# RUMBA32.net
KiCad netlist of a schematic drawn in Altium Designer
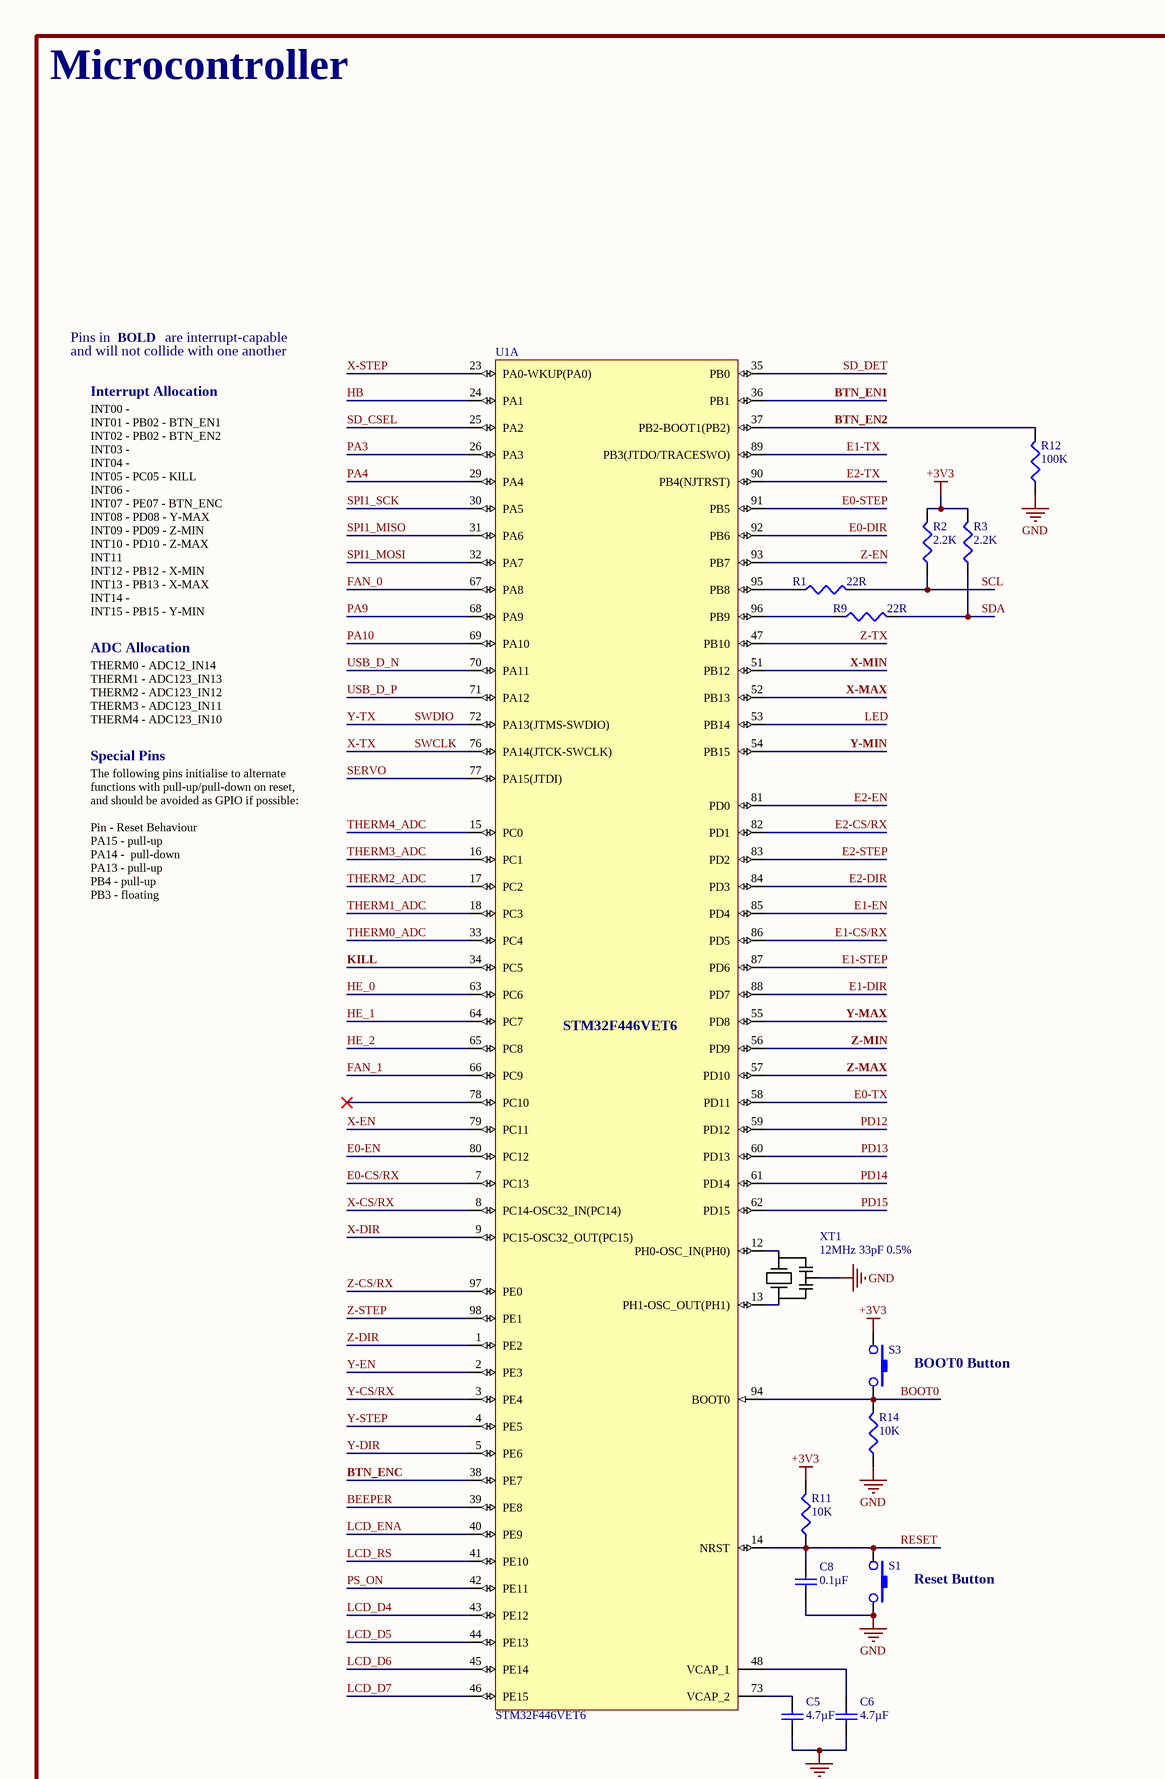
[diagram p0: RUMBA32.SchDoc, top left]
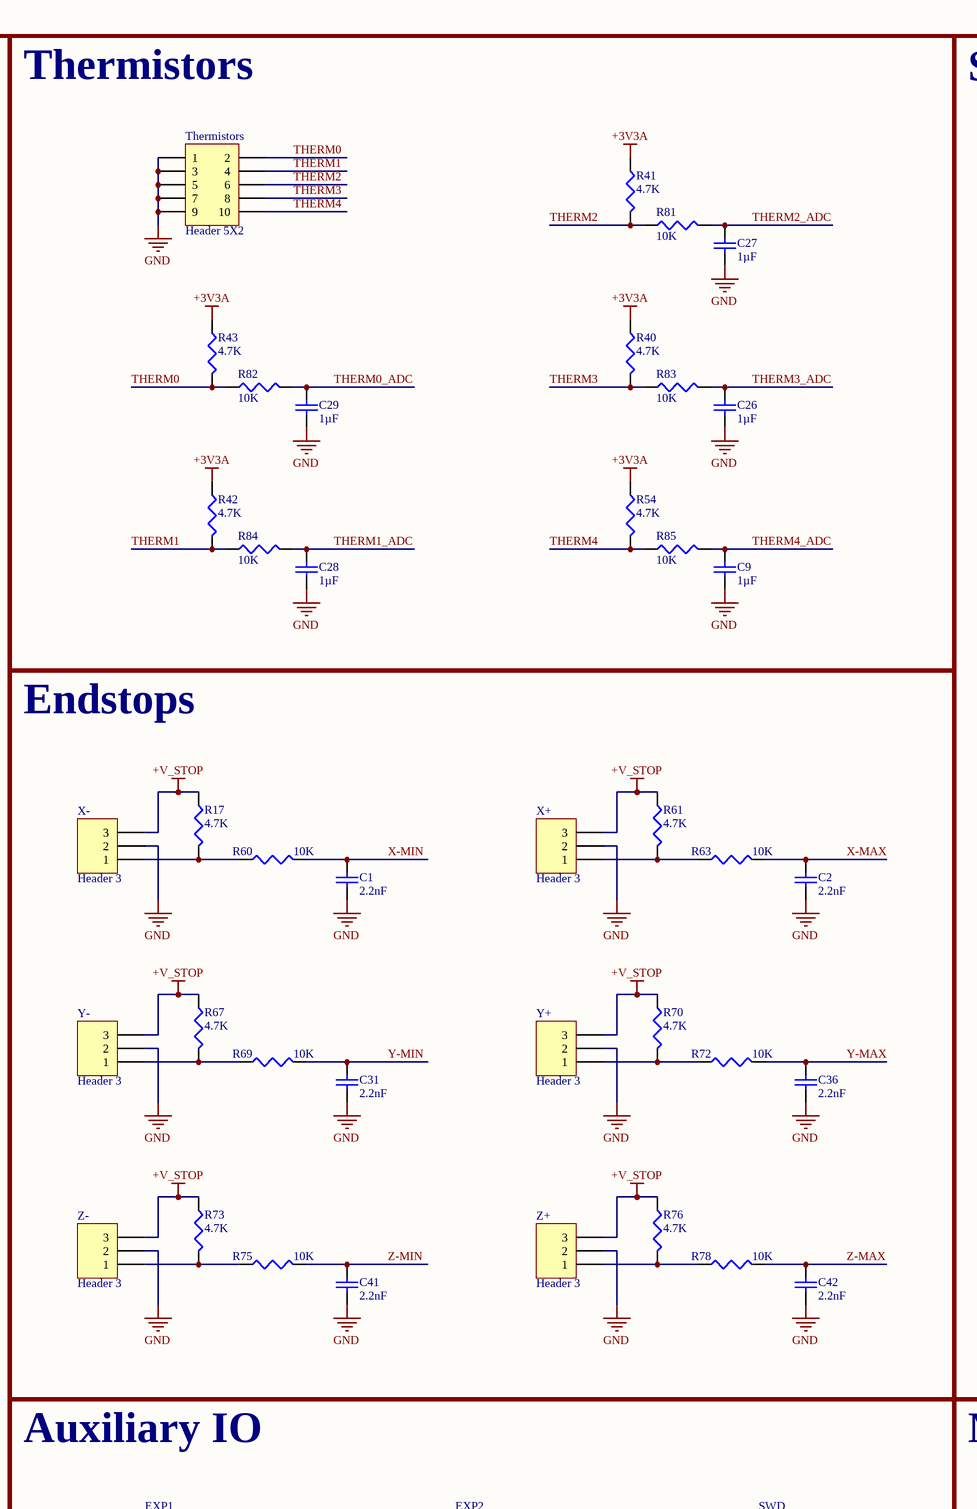
[diagram p1: RUMBA32.SchDoc, top middle]
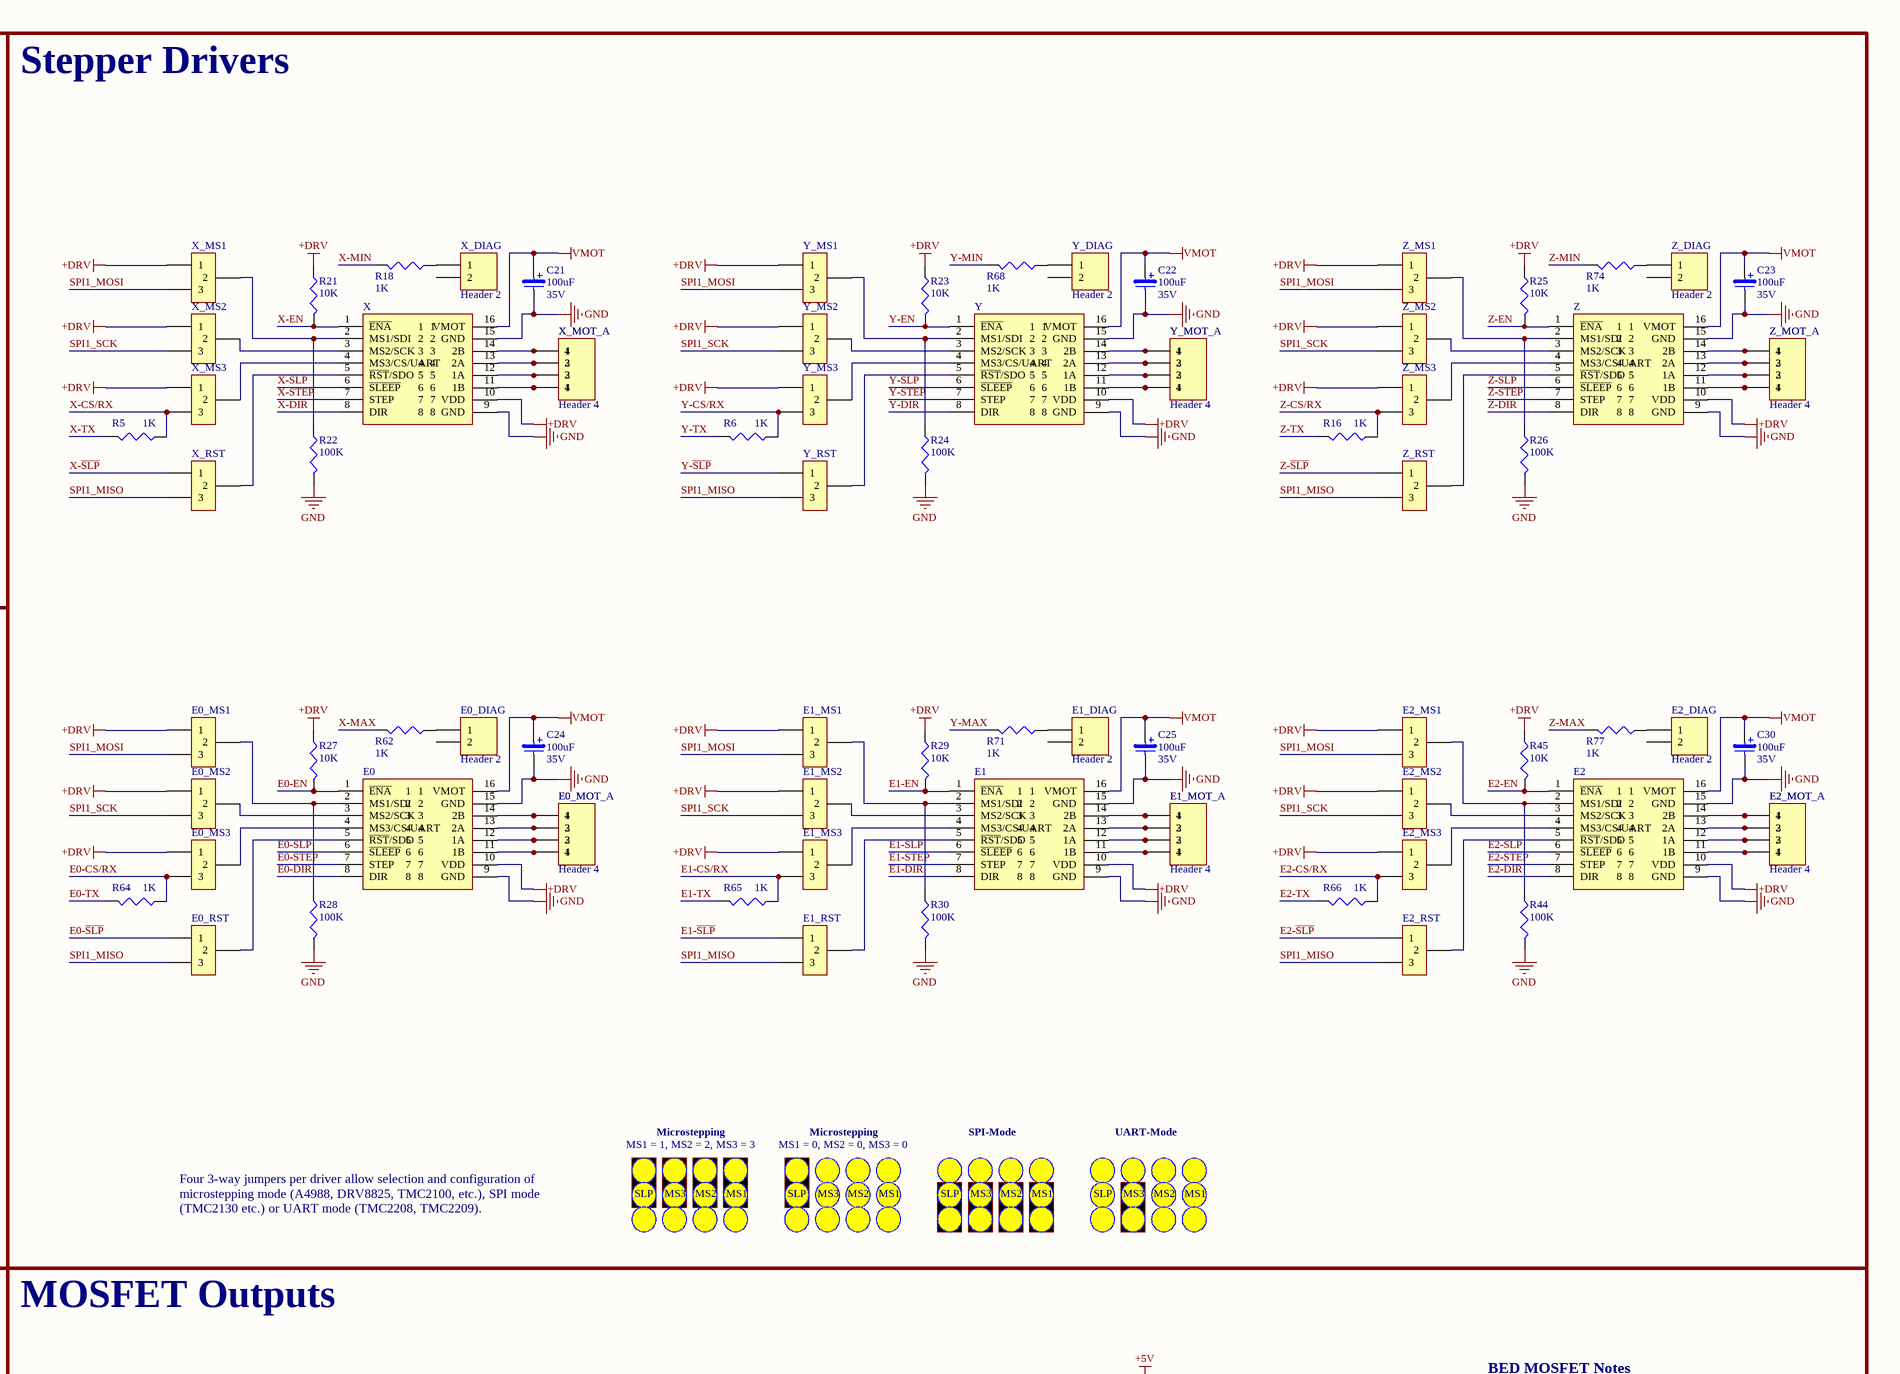
[diagram p2: RUMBA32.SchDoc, top right]
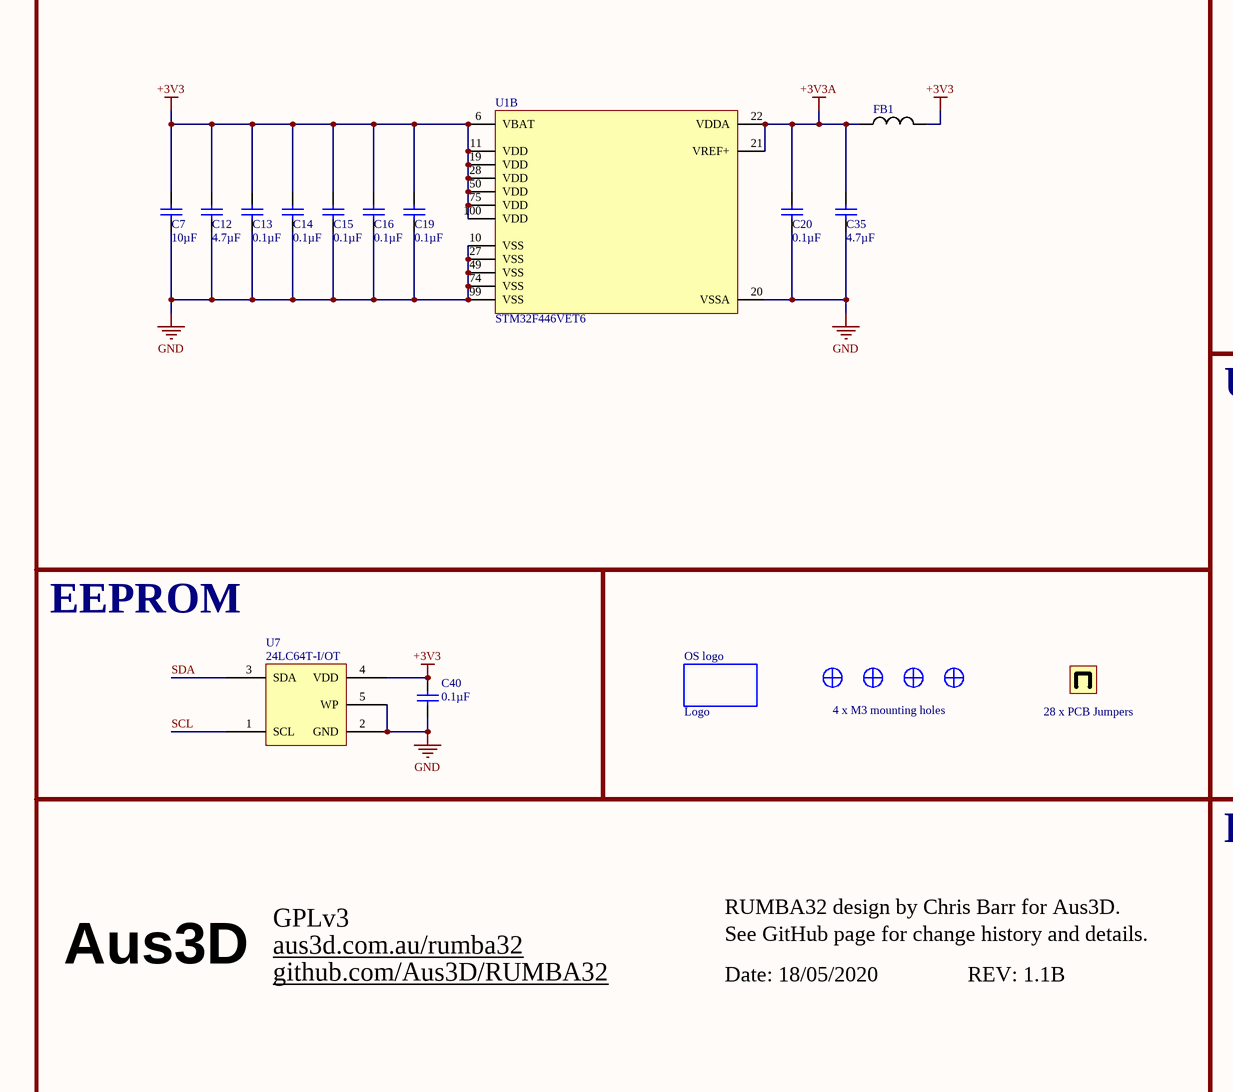
[diagram p3: RUMBA32.SchDoc, bottom left]
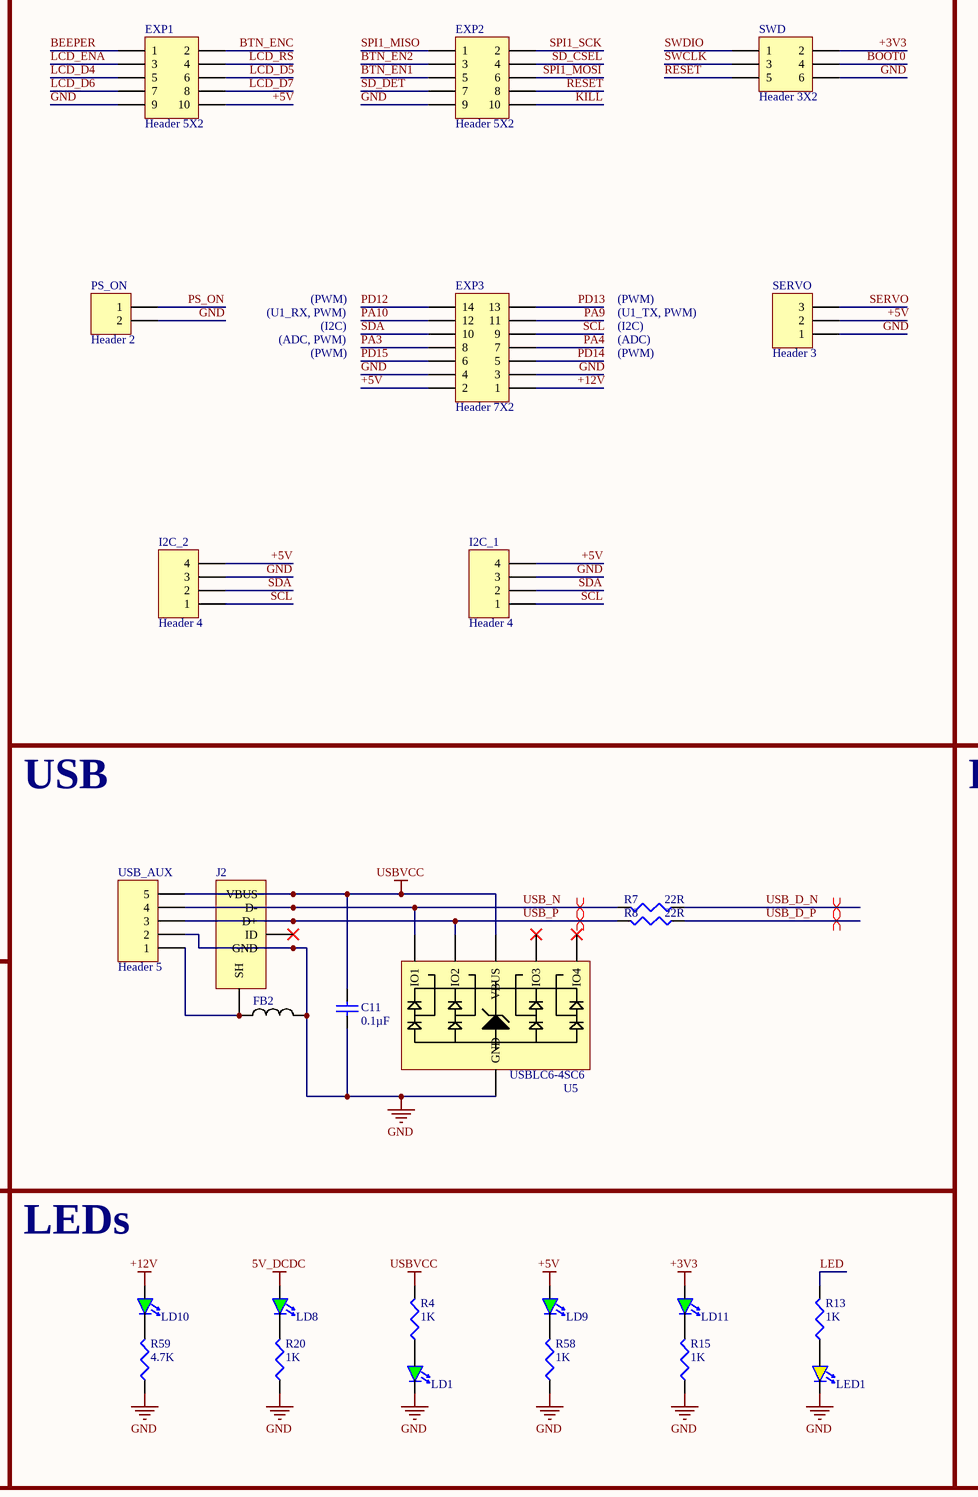
[diagram p4: RUMBA32.SchDoc, bottom middle]
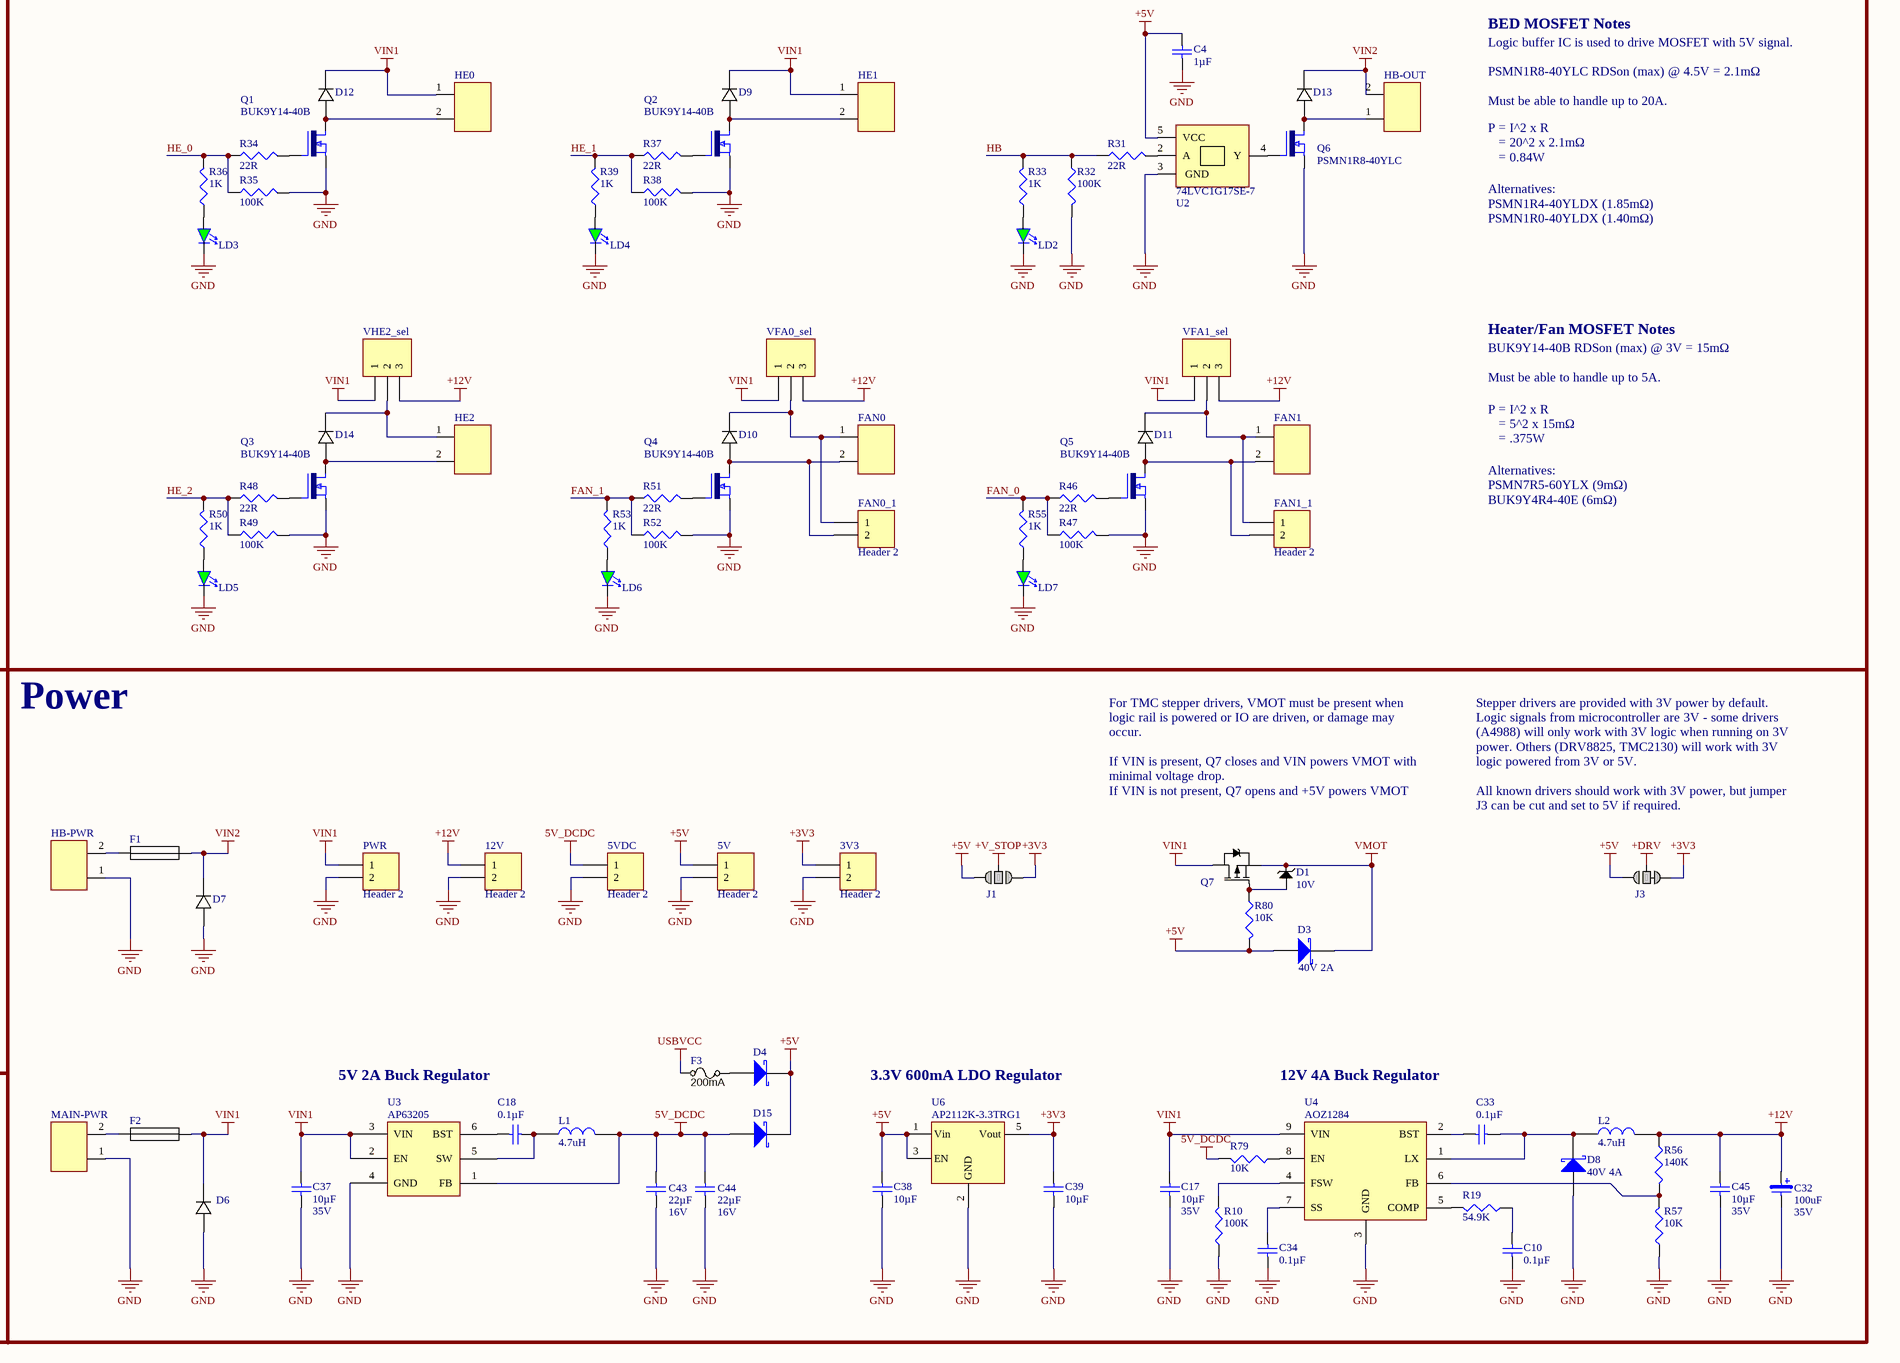
[diagram p5: RUMBA32.SchDoc, bottom right]

(export (version "E")
  (design (tool "Eeschema 10.0.6"))
  (components
    (comp (ref "3V3")
      (value "Header 2")
      (footprint "HDR1X2-HEADER")
      (description "Header, 2-Pin")
      (fields (field (name "PUBLISHER") "Altium Limited"))
      (libsource (lib "RUMBA_v2") (part "Header 2"))
    )
    (comp (ref "5V")
      (value "Header 2")
      (footprint "HDR1X2-HEADER")
      (description "Header, 2-Pin")
      (fields (field (name "PUBLISHER") "Altium Limited"))
      (libsource (lib "RUMBA_v2") (part "Header 2"))
    )
    (comp (ref "5VDC")
      (value "Header 2")
      (footprint "HDR1X2-HEADER")
      (description "Header, 2-Pin")
      (fields (field (name "PUBLISHER") "Altium Limited"))
      (libsource (lib "RUMBA_v2") (part "Header 2"))
    )
    (comp (ref "12V")
      (value "Header 2")
      (footprint "HDR1X2-HEADER")
      (description "Header, 2-Pin")
      (fields (field (name "PUBLISHER") "Altium Limited"))
      (libsource (lib "RUMBA_v2") (part "Header 2"))
    )
    (comp (ref "C1")
      (value "2.2nF")
      (footprint "CAPC1005X55N")
      (description "CAP CER 2.2NF 50V X7R 0402")
      (fields (field (name "VOLTAGE") "50V") (field (name "TOLERANCE") "±10%"))
      (libsource (lib "Ceramic Cap DBLIB") (part "Capacitor"))
    )
    (comp (ref "C2")
      (value "2.2nF")
      (footprint "CAPC1005X55N")
      (description "CAP CER 2.2NF 50V X7R 0402")
      (fields (field (name "VOLTAGE") "50V") (field (name "TOLERANCE") "±10%"))
      (libsource (lib "Ceramic Cap DBLIB") (part "Capacitor"))
    )
    (comp (ref "C4")
      (value "1µF")
      (footprint "CAP 1005-0402")
      (description "CAP CER 1UF 16V X5R 0402")
      (fields (field (name "TOLERANCE") "±10%") (field (name "VOLTAGE") "16V"))
      (libsource (lib "Ceramic Cap DBLIB") (part "Capacitor"))
    )
    (comp (ref "C5")
      (value "4.7µF")
      (footprint "CAP 1005-0402")
      (description "CAP CER 4.7UF 10V X5R 0402")
      (fields (field (name "TOLERANCE") "±20%") (field (name "VOLTAGE") "10V"))
      (libsource (lib "Ceramic Cap DBLIB") (part "Capacitor"))
    )
    (comp (ref "C6")
      (value "4.7µF")
      (footprint "CAP 1005-0402")
      (description "CAP CER 4.7UF 10V X5R 0402")
      (fields (field (name "TOLERANCE") "±20%") (field (name "VOLTAGE") "10V"))
      (libsource (lib "Ceramic Cap DBLIB") (part "Capacitor"))
    )
    (comp (ref "C7")
      (value "10µF")
      (footprint "CAPC1608X90N")
      (description "CAP CER 10UF 10V X5R 0603")
      (fields (field (name "VOLTAGE") "10V") (field (name "TOLERANCE") "±10%"))
      (libsource (lib "Ceramic Cap DBLIB") (part "Capacitor"))
    )
    (comp (ref "C8")
      (value "0.1µF")
      (footprint "CAP 1005-0402")
      (description "CAP CER 0.1UF 50V X7R 0402")
      (fields (field (name "VOLTAGE") "50V") (field (name "TOLERANCE") "±10%"))
      (libsource (lib "Ceramic Cap DBLIB") (part "Capacitor"))
    )
    (comp (ref "C9")
      (value "1µF")
      (footprint "CAPC1005X55N")
      (description "CAP CER 1UF 16V X5R 0402")
      (fields (field (name "TOLERANCE") "±10%") (field (name "VOLTAGE") "16V"))
      (libsource (lib "Ceramic Cap DBLIB") (part "Capacitor"))
    )
    (comp (ref "C10")
      (value "0.1µF")
      (footprint "CAP 1005-0402")
      (description "CAP CER 0.1UF 50V X7R 0402")
      (fields (field (name "VOLTAGE") "50V") (field (name "TOLERANCE") "±10%"))
      (libsource (lib "Ceramic Cap DBLIB") (part "Capacitor"))
    )
    (comp (ref "C11")
      (value "0.1µF")
      (footprint "CAP 1005-0402")
      (description "CAP CER 0.1UF 50V X7R 0402")
      (fields (field (name "VOLTAGE") "50V") (field (name "TOLERANCE") "±10%"))
      (libsource (lib "Ceramic Cap DBLIB") (part "Capacitor"))
    )
    (comp (ref "C12")
      (value "4.7µF")
      (footprint "CAPC1005X55N")
      (description "CAP CER 4.7UF 10V X5R 0402")
      (fields (field (name "TOLERANCE") "±20%") (field (name "VOLTAGE") "10V"))
      (libsource (lib "Ceramic Cap DBLIB") (part "Capacitor"))
    )
    (comp (ref "C13")
      (value "0.1µF")
      (footprint "CAP 1005-0402")
      (description "CAP CER 0.1UF 50V X7R 0402")
      (fields (field (name "VOLTAGE") "50V") (field (name "TOLERANCE") "±10%"))
      (libsource (lib "Ceramic Cap DBLIB") (part "Capacitor"))
    )
    (comp (ref "C14")
      (value "0.1µF")
      (footprint "CAP 1005-0402")
      (description "CAP CER 0.1UF 50V X7R 0402")
      (fields (field (name "VOLTAGE") "50V") (field (name "TOLERANCE") "±10%"))
      (libsource (lib "Ceramic Cap DBLIB") (part "Capacitor"))
    )
    (comp (ref "C15")
      (value "0.1µF")
      (footprint "CAP 1005-0402")
      (description "CAP CER 0.1UF 50V X7R 0402")
      (fields (field (name "VOLTAGE") "50V") (field (name "TOLERANCE") "±10%"))
      (libsource (lib "Ceramic Cap DBLIB") (part "Capacitor"))
    )
    (comp (ref "C16")
      (value "0.1µF")
      (footprint "CAP 1005-0402")
      (description "CAP CER 0.1UF 50V X7R 0402")
      (fields (field (name "VOLTAGE") "50V") (field (name "TOLERANCE") "±10%"))
      (libsource (lib "Ceramic Cap DBLIB") (part "Capacitor"))
    )
    (comp (ref "C17")
      (value "10µF")
      (footprint "CAPC3225X220N")
      (description "CAP CER 10UF 35V X7R 1210")
      (fields
        (field (name "TOLERANCE") "±10%")
        (field (name "VOLTAGE") "35V")
        (field (name "Comment") "Capacitor")
      )
      (libsource (lib "Ceramic Cap DBLIB") (part "Capacitor"))
    )
    (comp (ref "C18")
      (value "0.1µF")
      (footprint "CAP 1005-0402")
      (description "CAP CER 0.1UF 50V X7R 0402")
      (fields (field (name "VOLTAGE") "50V") (field (name "TOLERANCE") "±10%"))
      (libsource (lib "Ceramic Cap DBLIB") (part "Capacitor"))
    )
    (comp (ref "C19")
      (value "0.1µF")
      (footprint "CAP 1005-0402")
      (description "CAP CER 0.1UF 50V X7R 0402")
      (fields (field (name "VOLTAGE") "50V") (field (name "TOLERANCE") "±10%"))
      (libsource (lib "Ceramic Cap DBLIB") (part "Capacitor"))
    )
    (comp (ref "C20")
      (value "0.1µF")
      (footprint "CAP 1005-0402")
      (description "CAP CER 0.1UF 50V X7R 0402")
      (fields (field (name "VOLTAGE") "50V") (field (name "TOLERANCE") "±10%"))
      (libsource (lib "Ceramic Cap DBLIB") (part "Capacitor"))
    )
    (comp (ref "C21")
      (value "100uF")
      (footprint "CAP EL PANASONIC")
      (description "CAP ALUM 100UF 20% 35V SMD")
      (fields (field (name "VOLTAGE") "35V") (field (name "PUBLISHER") "Altium Limited"))
      (libsource (lib "RUMBA_v2") (part "CapE-6.3-100uF-35V"))
    )
    (comp (ref "C22")
      (value "100uF")
      (footprint "CAP EL PANASONIC")
      (description "CAP ALUM 100UF 20% 35V SMD")
      (fields (field (name "VOLTAGE") "35V") (field (name "PUBLISHER") "Altium Limited"))
      (libsource (lib "RUMBA_v2") (part "CapE-6.3-100uF-35V"))
    )
    (comp (ref "C23")
      (value "100uF")
      (footprint "CAP EL PANASONIC")
      (description "CAP ALUM 100UF 20% 35V SMD")
      (fields (field (name "VOLTAGE") "35V") (field (name "PUBLISHER") "Altium Limited"))
      (libsource (lib "RUMBA_v2") (part "CapE-6.3-100uF-35V"))
    )
    (comp (ref "C24")
      (value "100uF")
      (footprint "CAP EL PANASONIC")
      (description "CAP ALUM 100UF 20% 35V SMD")
      (fields (field (name "VOLTAGE") "35V") (field (name "PUBLISHER") "Altium Limited"))
      (libsource (lib "RUMBA_v2") (part "CapE-6.3-100uF-35V"))
    )
    (comp (ref "C25")
      (value "100uF")
      (footprint "CAP EL PANASONIC")
      (description "CAP ALUM 100UF 20% 35V SMD")
      (fields (field (name "VOLTAGE") "35V") (field (name "PUBLISHER") "Altium Limited"))
      (libsource (lib "RUMBA_v2") (part "CapE-6.3-100uF-35V"))
    )
    (comp (ref "C26")
      (value "1µF")
      (footprint "CAPC1005X55N")
      (description "CAP CER 1UF 16V X5R 0402")
      (fields (field (name "TOLERANCE") "±10%") (field (name "VOLTAGE") "16V"))
      (libsource (lib "Ceramic Cap DBLIB") (part "Capacitor"))
    )
    (comp (ref "C27")
      (value "1µF")
      (footprint "CAPC1005X55N")
      (description "CAP CER 1UF 16V X5R 0402")
      (fields (field (name "TOLERANCE") "±10%") (field (name "VOLTAGE") "16V"))
      (libsource (lib "Ceramic Cap DBLIB") (part "Capacitor"))
    )
    (comp (ref "C28")
      (value "1µF")
      (footprint "CAPC1005X55N")
      (description "CAP CER 1UF 16V X5R 0402")
      (fields (field (name "TOLERANCE") "±10%") (field (name "VOLTAGE") "16V"))
      (libsource (lib "Ceramic Cap DBLIB") (part "Capacitor"))
    )
    (comp (ref "C29")
      (value "1µF")
      (footprint "CAPC1005X55N")
      (description "CAP CER 1UF 16V X5R 0402")
      (fields (field (name "TOLERANCE") "±10%") (field (name "VOLTAGE") "16V"))
      (libsource (lib "Ceramic Cap DBLIB") (part "Capacitor"))
    )
    (comp (ref "C30")
      (value "100uF")
      (footprint "CAP EL PANASONIC")
      (description "CAP ALUM 100UF 20% 35V SMD")
      (fields (field (name "VOLTAGE") "35V") (field (name "PUBLISHER") "Altium Limited"))
      (libsource (lib "RUMBA_v2") (part "CapE-6.3-100uF-35V"))
    )
    (comp (ref "C31")
      (value "2.2nF")
      (footprint "CAPC1005X55N")
      (description "CAP CER 2.2NF 50V X7R 0402")
      (fields (field (name "VOLTAGE") "50V") (field (name "TOLERANCE") "±10%"))
      (libsource (lib "Ceramic Cap DBLIB") (part "Capacitor"))
    )
    (comp (ref "C32")
      (value "100uF")
      (footprint "CAP EL PANASONIC")
      (description "CAP ALUM 100UF 20% 35V SMD")
      (fields (field (name "VOLTAGE") "35V") (field (name "PUBLISHER") "Altium Limited"))
      (libsource (lib "RUMBA_v2") (part "CapE-6.3-100uF-35V"))
    )
    (comp (ref "C33")
      (value "0.1µF")
      (footprint "CAP 1005-0402")
      (description "CAP CER 0.1UF 50V X7R 0402")
      (fields (field (name "VOLTAGE") "50V") (field (name "TOLERANCE") "±10%"))
      (libsource (lib "Ceramic Cap DBLIB") (part "Capacitor"))
    )
    (comp (ref "C34")
      (value "0.1µF")
      (footprint "CAP 1005-0402")
      (description "CAP CER 0.1UF 50V X7R 0402")
      (fields (field (name "VOLTAGE") "50V") (field (name "TOLERANCE") "±10%"))
      (libsource (lib "Ceramic Cap DBLIB") (part "Capacitor"))
    )
    (comp (ref "C35")
      (value "4.7µF")
      (footprint "CAP 1005-0402")
      (description "CAP CER 4.7UF 10V X5R 0402")
      (fields (field (name "TOLERANCE") "±20%") (field (name "VOLTAGE") "10V"))
      (libsource (lib "Ceramic Cap DBLIB") (part "Capacitor"))
    )
    (comp (ref "C36")
      (value "2.2nF")
      (footprint "CAPC1005X55N")
      (description "CAP CER 2.2NF 50V X7R 0402")
      (fields (field (name "VOLTAGE") "50V") (field (name "TOLERANCE") "±10%"))
      (libsource (lib "Ceramic Cap DBLIB") (part "Capacitor"))
    )
    (comp (ref "C37")
      (value "10µF")
      (footprint "CAPC3225X220N")
      (description "CAP CER 10UF 35V X7R 1210")
      (fields
        (field (name "TOLERANCE") "±10%")
        (field (name "VOLTAGE") "35V")
        (field (name "Comment") "Capacitor")
      )
      (libsource (lib "Ceramic Cap DBLIB") (part "Capacitor"))
    )
    (comp (ref "C38")
      (value "10µF")
      (footprint "CAPC1608X90N")
      (description "CAP CER 10UF 10V X5R 0603")
      (fields (field (name "VOLTAGE") "10V") (field (name "TOLERANCE") "±10%"))
      (libsource (lib "Ceramic Cap DBLIB") (part "Capacitor"))
    )
    (comp (ref "C39")
      (value "10µF")
      (footprint "CAPC1608X90N")
      (description "CAP CER 10UF 10V X5R 0603")
      (fields (field (name "VOLTAGE") "10V") (field (name "TOLERANCE") "±10%"))
      (libsource (lib "Ceramic Cap DBLIB") (part "Capacitor"))
    )
    (comp (ref "C40")
      (value "0.1µF")
      (footprint "CAP 1005-0402")
      (description "CAP CER 0.1UF 50V X7R 0402")
      (fields (field (name "VOLTAGE") "50V") (field (name "TOLERANCE") "±10%"))
      (libsource (lib "Ceramic Cap DBLIB") (part "Capacitor"))
    )
    (comp (ref "C41")
      (value "2.2nF")
      (footprint "CAPC1005X55N")
      (description "CAP CER 2.2NF 50V X7R 0402")
      (fields (field (name "VOLTAGE") "50V") (field (name "TOLERANCE") "±10%"))
      (libsource (lib "Ceramic Cap DBLIB") (part "Capacitor"))
    )
    (comp (ref "C42")
      (value "2.2nF")
      (footprint "CAPC1005X55N")
      (description "CAP CER 2.2NF 50V X7R 0402")
      (fields (field (name "VOLTAGE") "50V") (field (name "TOLERANCE") "±10%"))
      (libsource (lib "Ceramic Cap DBLIB") (part "Capacitor"))
    )
    (comp (ref "C43")
      (value "22µF")
      (footprint "CAPC3225X220N")
      (description "CAP CER 22UF 16V X7R 1210")
      (fields
        (field (name "TOLERANCE") "±10%")
        (field (name "VOLTAGE") "16V")
        (field (name "Comment") "Capacitor")
      )
      (libsource (lib "Ceramic Cap DBLIB") (part "Capacitor"))
    )
    (comp (ref "C44")
      (value "22µF")
      (footprint "CAPC3225X220N")
      (description "CAP CER 22UF 16V X7R 1210")
      (fields
        (field (name "TOLERANCE") "±10%")
        (field (name "VOLTAGE") "16V")
        (field (name "Comment") "Capacitor")
      )
      (libsource (lib "Ceramic Cap DBLIB") (part "Capacitor"))
    )
    (comp (ref "C45")
      (value "10µF")
      (footprint "CAPC3225X220N")
      (description "CAP CER 10UF 35V X7R 1210")
      (fields
        (field (name "TOLERANCE") "±10%")
        (field (name "VOLTAGE") "35V")
        (field (name "Comment") "Capacitor")
      )
      (libsource (lib "Ceramic Cap DBLIB") (part "Capacitor"))
    )
    (comp (ref "D1")
      (value "Zener 10V 150mW SOD523")
      (footprint "SOD523")
      (description "DIODE ZENER 10V 500mW SOD523")
      (fields (field (name "VOLTAGE") "10V") (field (name "PUBLISHER") "Altium Limited"))
      (libsource (lib "picoprint_library") (part "Diode Zener 10V"))
    )
    (comp (ref "D3")
      (value "40V 2A")
      (footprint "DIOM2616X08N")
      (description "DIODE SCHOTTKY 40V 2A SOD123F")
      (fields (field (name "PUBLISHER") "Altium Limited"))
      (libsource (lib "picoprint_library") (part "Diode Schottky 2A 40V (SS24FL)"))
    )
    (comp (ref "D4")
      (value "~")
      (footprint "DIOM2616X08N")
      (description "DIODE SCHOTTKY 40V 2A SOD123F")
      (fields (field (name "PUBLISHER") "Altium Limited"))
      (libsource (lib "picoprint_library") (part "Diode Schottky 2A 40V (SS24FL)"))
    )
    (comp (ref "D6")
      (value "~")
      (footprint "DO-214AC")
      (description "DIODE GEN PURP 100V 1.5A SMA")
      (libsource (lib "PBL - Diodes") (part "DIODE_100V_1.5A_SMA"))
    )
    (comp (ref "D7")
      (value "~")
      (footprint "DO-214AC")
      (description "DIODE GEN PURP 100V 1.5A SMA")
      (libsource (lib "PBL - Diodes") (part "DIODE_100V_1.5A_SMA"))
    )
    (comp (ref "D8")
      (value "40V 4A")
      (footprint "DO-214AA")
      (description "DIODE SCHOTTKY 40V 4A DO214AA")
      (fields (field (name "PUBLISHER") "Altium Limited"))
      (libsource (lib "RUMBA_library") (part "Diode Schottky - 40V 4A - SSB44-E3"))
    )
    (comp (ref "D9")
      (value "~")
      (footprint "DO-214AC")
      (description "DIODE GEN PURP 100V 1.5A SMA")
      (libsource (lib "PBL - Diodes") (part "DIODE_100V_1.5A_SMA"))
    )
    (comp (ref "D10")
      (value "~")
      (footprint "DO-214AC")
      (description "DIODE GEN PURP 100V 1.5A SMA")
      (libsource (lib "PBL - Diodes") (part "DIODE_100V_1.5A_SMA"))
    )
    (comp (ref "D11")
      (value "~")
      (footprint "DO-214AC")
      (description "DIODE GEN PURP 100V 1.5A SMA")
      (libsource (lib "PBL - Diodes") (part "DIODE_100V_1.5A_SMA"))
    )
    (comp (ref "D12")
      (value "~")
      (footprint "DO-214AC")
      (description "DIODE GEN PURP 100V 1.5A SMA")
      (libsource (lib "PBL - Diodes") (part "DIODE_100V_1.5A_SMA"))
    )
    (comp (ref "D13")
      (value "~")
      (footprint "DO-214AC")
      (description "DIODE GEN PURP 100V 1.5A SMA")
      (libsource (lib "PBL - Diodes") (part "DIODE_100V_1.5A_SMA"))
    )
    (comp (ref "D14")
      (value "~")
      (footprint "DO-214AC")
      (description "DIODE GEN PURP 100V 1.5A SMA")
      (libsource (lib "PBL - Diodes") (part "DIODE_100V_1.5A_SMA"))
    )
    (comp (ref "D15")
      (value "~")
      (footprint "DIOM2616X08N")
      (description "DIODE SCHOTTKY 40V 2A SOD123F")
      (fields (field (name "PUBLISHER") "Altium Limited"))
      (libsource (lib "picoprint_library") (part "Diode Schottky 2A 40V (SS24FL)"))
    )
    (comp (ref "E0")
      (value "Header 8")
      (footprint "A4988BREAKOUT_2")
      (description "Header, 8-Pin, Female")
      (libsource (lib "main_library") (part "STEPSTICK_BREAKOUT"))
    )
    (comp (ref "E0_0")
      (value "Header 8")
      (footprint "HDR1X8-HEADER")
      (description "Header, 8-Pin, Female")
      (fields (field (name "PUBLISHER") "Altium Limited"))
      (libsource (lib "picoprint_library") (part "Header 8x1"))
    )
    (comp (ref "E0_1")
      (value "Header 8")
      (footprint "HDR1X8-HEADER")
      (description "Header, 8-Pin, Female")
      (fields (field (name "PUBLISHER") "Altium Limited"))
      (libsource (lib "picoprint_library") (part "Header 8x1"))
    )
    (comp (ref "E0_DIAG")
      (value "Header 2")
      (footprint "HDR1X2-HEADER Female")
      (description "Header, 2-Pin, Female")
      (libsource (lib "main_library") (part "Header 1X2 Female"))
    )
    (comp (ref "E0_MOT")
      (value "~")
      (footprint "TERM4 3.5mm")
      (description "TERM BLK 4POS SIDE ENT 3.5MM PCB")
      (fields (field (name "PUBLISHER") "Altium Limited"))
      (libsource (lib "RUMBA_v2") (part "ScrewTerminal-3.5mm-4Way"))
    )
    (comp (ref "E0_MOT_A")
      (value "Header 4")
      (footprint "HDR1X4")
      (description "Header, 4-Pin")
      (fields (field (name "PUBLISHER") "Altium Limited"))
      (libsource (lib "RUMBA_v2") (part "Header 4_1"))
    )
    (comp (ref "E0_MS1")
      (value "Header 3")
      (footprint "HDR1X3-HEADER")
      (description "Header, 3-Pin")
      (fields (field (name "PUBLISHER") "Altium Limited"))
      (libsource (lib "RUMBA_library") (part "Header 3"))
    )
    (comp (ref "E0_MS2")
      (value "Header 3")
      (footprint "HDR1X3-HEADER")
      (description "Header, 3-Pin")
      (fields (field (name "PUBLISHER") "Altium Limited"))
      (libsource (lib "RUMBA_library") (part "Header 3"))
    )
    (comp (ref "E0_MS3")
      (value "Header 3")
      (footprint "HDR1X3-HEADER")
      (description "Header, 3-Pin")
      (fields (field (name "PUBLISHER") "Altium Limited"))
      (libsource (lib "RUMBA_library") (part "Header 3"))
    )
    (comp (ref "E0_RST")
      (value "Header 3")
      (footprint "HDR1X3-HEADER")
      (description "Header, 3-Pin")
      (fields (field (name "PUBLISHER") "Altium Limited"))
      (libsource (lib "RUMBA_library") (part "Header 3"))
    )
    (comp (ref "E1")
      (value "Header 8")
      (footprint "A4988BREAKOUT_2")
      (description "Header, 8-Pin, Female")
      (libsource (lib "main_library") (part "STEPSTICK_BREAKOUT"))
    )
    (comp (ref "E1_0")
      (value "Header 8")
      (footprint "HDR1X8-HEADER")
      (description "Header, 8-Pin, Female")
      (fields (field (name "PUBLISHER") "Altium Limited"))
      (libsource (lib "picoprint_library") (part "Header 8x1"))
    )
    (comp (ref "E1_1")
      (value "Header 8")
      (footprint "HDR1X8-HEADER")
      (description "Header, 8-Pin, Female")
      (fields (field (name "PUBLISHER") "Altium Limited"))
      (libsource (lib "picoprint_library") (part "Header 8x1"))
    )
    (comp (ref "E1_DIAG")
      (value "Header 2")
      (footprint "HDR1X2-HEADER Female")
      (description "Header, 2-Pin, Female")
      (libsource (lib "main_library") (part "Header 1X2 Female"))
    )
    (comp (ref "E1_MOT")
      (value "~")
      (footprint "TERM4 3.5mm")
      (description "TERM BLK 4POS SIDE ENT 3.5MM PCB")
      (fields (field (name "PUBLISHER") "Altium Limited"))
      (libsource (lib "RUMBA_v2") (part "ScrewTerminal-3.5mm-4Way"))
    )
    (comp (ref "E1_MOT_A")
      (value "Header 4")
      (footprint "HDR1X4")
      (description "Header, 4-Pin")
      (fields (field (name "PUBLISHER") "Altium Limited"))
      (libsource (lib "RUMBA_v2") (part "Header 4_1"))
    )
    (comp (ref "E1_MS1")
      (value "Header 3")
      (footprint "HDR1X3-HEADER")
      (description "Header, 3-Pin")
      (fields (field (name "PUBLISHER") "Altium Limited"))
      (libsource (lib "RUMBA_library") (part "Header 3"))
    )
    (comp (ref "E1_MS2")
      (value "Header 3")
      (footprint "HDR1X3-HEADER")
      (description "Header, 3-Pin")
      (fields (field (name "PUBLISHER") "Altium Limited"))
      (libsource (lib "RUMBA_library") (part "Header 3"))
    )
    (comp (ref "E1_MS3")
      (value "Header 3")
      (footprint "HDR1X3-HEADER")
      (description "Header, 3-Pin")
      (fields (field (name "PUBLISHER") "Altium Limited"))
      (libsource (lib "RUMBA_library") (part "Header 3"))
    )
    (comp (ref "E1_RST")
      (value "Header 3")
      (footprint "HDR1X3-HEADER")
      (description "Header, 3-Pin")
      (fields (field (name "PUBLISHER") "Altium Limited"))
      (libsource (lib "RUMBA_library") (part "Header 3"))
    )
    (comp (ref "E2")
      (value "Header 8")
      (footprint "A4988BREAKOUT_2")
      (description "Header, 8-Pin, Female")
      (libsource (lib "main_library") (part "STEPSTICK_BREAKOUT"))
    )
    (comp (ref "E2_0")
      (value "Header 8")
      (footprint "HDR1X8-HEADER")
      (description "Header, 8-Pin, Female")
      (fields (field (name "PUBLISHER") "Altium Limited"))
      (libsource (lib "picoprint_library") (part "Header 8x1"))
    )
    (comp (ref "E2_1")
      (value "Header 8")
      (footprint "HDR1X8-HEADER")
      (description "Header, 8-Pin, Female")
      (fields (field (name "PUBLISHER") "Altium Limited"))
      (libsource (lib "picoprint_library") (part "Header 8x1"))
    )
    (comp (ref "E2_DIAG")
      (value "Header 2")
      (footprint "HDR1X2-HEADER Female")
      (description "Header, 2-Pin, Female")
      (libsource (lib "main_library") (part "Header 1X2 Female"))
    )
    (comp (ref "E2_MOT")
      (value "~")
      (footprint "TERM4 3.5mm")
      (description "TERM BLK 4POS SIDE ENT 3.5MM PCB")
      (fields (field (name "PUBLISHER") "Altium Limited"))
      (libsource (lib "RUMBA_v2") (part "ScrewTerminal-3.5mm-4Way"))
    )
    (comp (ref "E2_MOT_A")
      (value "Header 4")
      (footprint "HDR1X4")
      (description "Header, 4-Pin")
      (fields (field (name "PUBLISHER") "Altium Limited"))
      (libsource (lib "RUMBA_v2") (part "Header 4_1"))
    )
    (comp (ref "E2_MS1")
      (value "Header 3")
      (footprint "HDR1X3-HEADER")
      (description "Header, 3-Pin")
      (fields (field (name "PUBLISHER") "Altium Limited"))
      (libsource (lib "RUMBA_library") (part "Header 3"))
    )
    (comp (ref "E2_MS2")
      (value "Header 3")
      (footprint "HDR1X3-HEADER")
      (description "Header, 3-Pin")
      (fields (field (name "PUBLISHER") "Altium Limited"))
      (libsource (lib "RUMBA_library") (part "Header 3"))
    )
    (comp (ref "E2_MS3")
      (value "Header 3")
      (footprint "HDR1X3-HEADER")
      (description "Header, 3-Pin")
      (fields (field (name "PUBLISHER") "Altium Limited"))
      (libsource (lib "RUMBA_library") (part "Header 3"))
    )
    (comp (ref "E2_RST")
      (value "Header 3")
      (footprint "HDR1X3-HEADER")
      (description "Header, 3-Pin")
      (fields (field (name "PUBLISHER") "Altium Limited"))
      (libsource (lib "RUMBA_library") (part "Header 3"))
    )
    (comp (ref "EXP1")
      (value "Header 5X2")
      (footprint "HDR2X5_exp Iner only\\")
      (description "Header, 5-Pin, Dual row")
      (fields (field (name "PUBLISHER") "Altium Limited"))
      (libsource (lib "RUMBA_v2") (part "Header 5X2"))
    )
    (comp (ref "EXP2")
      (value "Header 5X2")
      (footprint "HDR2X5_exp Iner only\\")
      (description "Header, 5-Pin, Dual row")
      (fields (field (name "PUBLISHER") "Altium Limited"))
      (libsource (lib "RUMBA_v2") (part "Header 5X2"))
    )
    (comp (ref "EXP3")
      (value "Header 7X2")
      (footprint "HDR2X7")
      (description "Header, 7-Pin, Dual row")
      (fields (field (name "PUBLISHER") "Altium Limited"))
      (libsource (lib "RUMBA_v2") (part "Header 7X2"))
    )
    (comp (ref "F1")
      (value "~")
      (footprint "Fuseholder - BK-6013 - Mini ATC ATO Blade 15A")
      (description "FUSE HOLDER BLADE PCB")
      (libsource (lib "") (part "Fuseholder - Mini ATC ATO 15A_1"))
    )
    (comp (ref "F2")
      (value "~")
      (footprint "Fuseholder - BK-6013 - Mini ATC ATO Blade 15A")
      (description "FUSE HOLDER BLADE PCB")
      (libsource (lib "Schlib1") (part "Fuseholder - Mini ATC ATO 15A"))
    )
    (comp (ref "F3")
      (value "200mA")
      (footprint "FUSE 1608-0603")
      (description "PTC RESET FUSE 9V 200MA 0603")
      (libsource (lib "Schlib1") (part "Fuse - 15V 200mA Trip PTC SMD 0603"))
    )
    (comp (ref "FAN0")
      (value "~")
      (footprint "TERM2 3.5mm")
      (description "TERM BLK 2POS SIDE ENT 3.5MM PCB")
      (libsource (lib "RUMBA_v2") (part "ScrewTerminal-3.5mm-2Way"))
    )
    (comp (ref "FAN0_1")
      (value "Header 2")
      (footprint "HDR1X2")
      (description "Header, 2-Pin")
      (fields (field (name "PUBLISHER") "Altium Limited"))
      (libsource (lib "RUMBA_v2") (part "Header 2"))
    )
    (comp (ref "FAN1")
      (value "~")
      (footprint "TERM2 3.5mm")
      (description "TERM BLK 2POS SIDE ENT 3.5MM PCB")
      (libsource (lib "RUMBA_v2") (part "ScrewTerminal-3.5mm-2Way"))
    )
    (comp (ref "FAN1_1")
      (value "Header 2")
      (footprint "HDR1X2")
      (description "Header, 2-Pin")
      (fields (field (name "PUBLISHER") "Altium Limited"))
      (libsource (lib "RUMBA_v2") (part "Header 2"))
    )
    (comp (ref "FB1")
      (value "Ferrite Bead SMD 0402")
      (footprint "RESC1005X40N")
      (description "FERRITE BEAD 120R 300MA 0402")
      (fields (field (name "PUBLISHER") "Altium Limited"))
      (libsource (lib "main_library") (part "Ferrite Bead SMD 0402 - 120R"))
    )
    (comp (ref "FB2")
      (value "Ferrite Bead SMD 0402")
      (footprint "RESC1005X40N")
      (description "FERRITE BEAD 120R 300MA 0402")
      (fields (field (name "PUBLISHER") "Altium Limited"))
      (libsource (lib "main_library") (part "Ferrite Bead SMD 0402 - 120R"))
    )
    (comp (ref "HB-OUT")
      (value "~")
      (footprint "TERM2 5MM")
      (description "TERM BLK 2POS SIDE ENTRY 5MM PCB")
      (libsource (lib "RUMBA_v2") (part "ScrewTerminal-5mm-2Way"))
    )
    (comp (ref "HB-PWR")
      (value "~")
      (footprint "TERM2 5MM")
      (description "TERM BLK 2POS SIDE ENTRY 5MM PCB")
      (libsource (lib "") (part "ScrewTerminal-5mm-2Way_1"))
    )
    (comp (ref "HE0")
      (value "~")
      (footprint "TERM2 3.5mm")
      (description "TERM BLK 2POS SIDE ENT 3.5MM PCB")
      (libsource (lib "RUMBA_v2") (part "ScrewTerminal-3.5mm-2Way"))
    )
    (comp (ref "HE1")
      (value "~")
      (footprint "TERM2 3.5mm")
      (description "TERM BLK 2POS SIDE ENT 3.5MM PCB")
      (libsource (lib "RUMBA_v2") (part "ScrewTerminal-3.5mm-2Way"))
    )
    (comp (ref "HE2")
      (value "~")
      (footprint "TERM2 3.5mm")
      (description "TERM BLK 2POS SIDE ENT 3.5MM PCB")
      (libsource (lib "RUMBA_v2") (part "ScrewTerminal-3.5mm-2Way"))
    )
    (comp (ref "I2C_1")
      (value "Header 4")
      (footprint "HDR1X4-HEADER")
      (description "Header, 4-Pin")
      (fields (field (name "PUBLISHER") "Altium Limited"))
      (libsource (lib "Miscellaneous Connectors") (part "Header 4"))
    )
    (comp (ref "I2C_2")
      (value "Header 4")
      (footprint "HDR1X4-HEADER")
      (description "Header, 4-Pin")
      (fields (field (name "PUBLISHER") "Altium Limited"))
      (libsource (lib "Miscellaneous Connectors") (part "Header 4"))
    )
    (comp (ref "J1")
      (value "Jumper")
      (footprint "Jump_3Way - SMALL")
      (description "SMD jumper")
      (libsource (lib "PBL - Pads and Jumpers") (part "JUMP_3WAY"))
    )
    (comp (ref "J2")
      (value "~")
      (footprint "Micro-USB B Molex 105017-0001")
      (description "CONN RCPT USB2.0 MICRO B SMD R/A")
      (libsource (lib "picoprint_library") (part "Micro-USB B Socket"))
    )
    (comp (ref "J3")
      (value "Jumper")
      (footprint "Jump_3Way - SMALL")
      (description "SMD jumper")
      (libsource (lib "PBL - Pads and Jumpers") (part "JUMP_3WAY"))
    )
    (comp (ref "JMP1")
      (value "Green")
      (description "2.54mm .1\" PCB Jumper, Green")
      (libsource (lib "Schlib1") (part "PCB Jumper"))
    )
    (comp (ref "L1")
      (value "4.7uH")
      (footprint "SRN6045TA SMD Inductor")
      (description "FIXED IND 4.7UH 4.5A 26 MOHM SMD")
      (fields (field (name "PUBLISHER") "Altium Limited"))
      (libsource (lib "RUMBA_v2") (part "Inductor SMD 33uH 2.5A"))
    )
    (comp (ref "L2")
      (value "4.7uH")
      (footprint "SRN6045TA SMD Inductor")
      (description "FIXED IND 4.7UH 4.5A 26 MOHM SMD")
      (fields (field (name "PUBLISHER") "Altium Limited"))
      (libsource (lib "RUMBA_v2") (part "Inductor SMD 33uH 2.5A"))
    )
    (comp (ref "LD1")
      (value "~")
      (footprint "LED 1608-0603")
      (description "LED GREEN CLEAR CHIP SMD 0603")
      (libsource (lib "picoprint_library") (part "LEDG  0603"))
    )
    (comp (ref "LD2")
      (value "~")
      (footprint "LED 1608-0603")
      (description "LED GREEN CLEAR CHIP SMD 0603")
      (libsource (lib "picoprint_library") (part "LEDG  0603"))
    )
    (comp (ref "LD3")
      (value "~")
      (footprint "LED 1608-0603")
      (description "LED GREEN CLEAR CHIP SMD 0603")
      (libsource (lib "picoprint_library") (part "LEDG  0603"))
    )
    (comp (ref "LD4")
      (value "~")
      (footprint "LED 1608-0603")
      (description "LED GREEN CLEAR CHIP SMD 0603")
      (libsource (lib "picoprint_library") (part "LEDG  0603"))
    )
    (comp (ref "LD5")
      (value "~")
      (footprint "LED 1608-0603")
      (description "LED GREEN CLEAR CHIP SMD 0603")
      (libsource (lib "picoprint_library") (part "LEDG  0603"))
    )
    (comp (ref "LD6")
      (value "~")
      (footprint "LED 1608-0603")
      (description "LED GREEN CLEAR CHIP SMD 0603")
      (libsource (lib "picoprint_library") (part "LEDG  0603"))
    )
    (comp (ref "LD7")
      (value "~")
      (footprint "LED 1608-0603")
      (description "LED GREEN CLEAR CHIP SMD 0603")
      (libsource (lib "picoprint_library") (part "LEDG  0603"))
    )
    (comp (ref "LD8")
      (value "~")
      (footprint "LED 1608-0603")
      (description "LED GREEN CLEAR CHIP SMD 0603")
      (libsource (lib "picoprint_library") (part "LEDG  0603"))
    )
    (comp (ref "LD9")
      (value "~")
      (footprint "LED 1608-0603")
      (description "LED GREEN CLEAR CHIP SMD 0603")
      (libsource (lib "picoprint_library") (part "LEDG  0603"))
    )
    (comp (ref "LD10")
      (value "~")
      (footprint "LED 1608-0603")
      (description "LED GREEN CLEAR CHIP SMD 0603")
      (libsource (lib "picoprint_library") (part "LEDG  0603"))
    )
    (comp (ref "LD11")
      (value "~")
      (footprint "LED 1608-0603")
      (description "LED GREEN CLEAR CHIP SMD 0603")
      (libsource (lib "picoprint_library") (part "LEDG  0603"))
    )
    (comp (ref "LED1")
      (value "~")
      (footprint "LED 1608-0603")
      (description "LED YELLOW CLEAR CHIP SMD 0603")
      (libsource (lib "picoprint_library") (part "LEDY  0603"))
    )
    (comp (ref "MAIN-PWR")
      (value "~")
      (footprint "TERM2 5MM")
      (description "TERM BLK 2POS SIDE ENTRY 5MM PCB")
      (libsource (lib "") (part "ScrewTerminal-5mm-2Way_1"))
    )
    (comp (ref "OS logo") (value "Logo") (footprint "OS LOGO TOP") (libsource (lib "gc") (part "Logo")))
    (comp (ref "PS_ON")
      (value "Header 2")
      (footprint "HDR1X2-HEADER")
      (description "Header, 2-Pin")
      (fields (field (name "PUBLISHER") "Altium Limited"))
      (libsource (lib "") (part "Header 2_1"))
    )
    (comp (ref "PWR")
      (value "Header 2")
      (footprint "HDR1X2-HEADER")
      (description "Header, 2-Pin")
      (fields (field (name "PUBLISHER") "Altium Limited"))
      (libsource (lib "RUMBA_v2") (part "Header 2"))
    )
    (comp (ref "Q1")
      (value "BUK9Y14-40B")
      (footprint "LFPACK")
      (description "MOSFET N-CH 40V 56A LFPAK")
      (libsource (lib "RUMBA_library") (part "MOSFET - BUK9Y21-40E"))
    )
    (comp (ref "Q2")
      (value "BUK9Y14-40B")
      (footprint "LFPACK")
      (description "MOSFET N-CH 40V 56A LFPAK")
      (libsource (lib "RUMBA_library") (part "MOSFET - BUK9Y21-40E"))
    )
    (comp (ref "Q3")
      (value "BUK9Y14-40B")
      (footprint "LFPACK")
      (description "MOSFET N-CH 40V 56A LFPAK")
      (libsource (lib "RUMBA_library") (part "MOSFET - BUK9Y21-40E"))
    )
    (comp (ref "Q4")
      (value "BUK9Y14-40B")
      (footprint "LFPACK")
      (description "MOSFET N-CH 40V 56A LFPAK")
      (libsource (lib "RUMBA_library") (part "MOSFET - BUK9Y21-40E"))
    )
    (comp (ref "Q5")
      (value "BUK9Y14-40B")
      (footprint "LFPACK")
      (description "MOSFET N-CH 40V 56A LFPAK")
      (libsource (lib "RUMBA_library") (part "MOSFET - BUK9Y21-40E"))
    )
    (comp (ref "Q6")
      (value "PSMN1R8-40YLC")
      (footprint "LFPACK")
      (description "MOSFET N-CH 40V 100A LFPAK")
      (libsource (lib "RUMBA_library") (part "MOSFET - PSMN1R8-40YLC"))
    )
    (comp (ref "Q7")
      (value "Si2371EDS")
      (footprint "SOT23-3 New")
      (description "MOSFET SMD P-CH 30V 4.8A SOT-23-3")
      (libsource (lib "main_library") (part "MOSFET - Si2371EDS"))
    )
    (comp (ref "R1")
      (value "22R")
      (footprint "RESC1005X40N")
      (description "RES SMD 22 OHM 1% 1/16W 0402")
      (fields
        (field (name "TOLERANCE") "±1%")
        (field (name "Comment") "Resistor")
        (field (name "PUBLISHER") "Altium Limited")
      )
      (libsource (lib "Database_Libs1") (part "Resistor"))
    )
    (comp (ref "R2")
      (value "2.2K")
      (footprint "RESC1005X40N")
      (description "RES SMD 2.2K OHM 1% 1/16W 0402")
      (fields
        (field (name "TOLERANCE") "±1%")
        (field (name "Comment") "Resistor")
        (field (name "PUBLISHER") "Altium Limited")
      )
      (libsource (lib "Database_Libs1") (part "Resistor"))
    )
    (comp (ref "R3")
      (value "2.2K")
      (footprint "RESC1005X40N")
      (description "RES SMD 2.2K OHM 1% 1/16W 0402")
      (fields
        (field (name "TOLERANCE") "±1%")
        (field (name "Comment") "Resistor")
        (field (name "PUBLISHER") "Altium Limited")
      )
      (libsource (lib "Database_Libs1") (part "Resistor"))
    )
    (comp (ref "R4")
      (value "1K")
      (footprint "RESC1005X40N")
      (description "RES SMD 1K OHM 1% 1/16W 0402")
      (fields
        (field (name "TOLERANCE") "±1%")
        (field (name "Comment") "Resistor")
        (field (name "PUBLISHER") "Altium Limited")
      )
      (libsource (lib "Database_Libs1") (part "Resistor"))
    )
    (comp (ref "R5")
      (value "1K")
      (footprint "RESC1005X40N")
      (description "RES SMD 1K OHM 1% 1/16W 0402")
      (fields
        (field (name "TOLERANCE") "±1%")
        (field (name "Comment") "Resistor")
        (field (name "PUBLISHER") "Altium Limited")
      )
      (libsource (lib "Database_Libs1") (part "Resistor"))
    )
    (comp (ref "R6")
      (value "1K")
      (footprint "RESC1005X40N")
      (description "RES SMD 1K OHM 1% 1/16W 0402")
      (fields
        (field (name "TOLERANCE") "±1%")
        (field (name "Comment") "Resistor")
        (field (name "PUBLISHER") "Altium Limited")
      )
      (libsource (lib "Database_Libs1") (part "Resistor"))
    )
    (comp (ref "R7")
      (value "22R")
      (footprint "RESC1005X40N")
      (description "RES SMD 22 OHM 1% 1/16W 0402")
      (fields
        (field (name "TOLERANCE") "±1%")
        (field (name "Comment") "Resistor")
        (field (name "PUBLISHER") "Altium Limited")
      )
      (libsource (lib "Database_Libs1") (part "Resistor"))
    )
    (comp (ref "R8")
      (value "22R")
      (footprint "RESC1005X40N")
      (description "RES SMD 22 OHM 1% 1/16W 0402")
      (fields
        (field (name "TOLERANCE") "±1%")
        (field (name "Comment") "Resistor")
        (field (name "PUBLISHER") "Altium Limited")
      )
      (libsource (lib "Database_Libs1") (part "Resistor"))
    )
    (comp (ref "R9")
      (value "22R")
      (footprint "RESC1005X40N")
      (description "RES SMD 22 OHM 1% 1/16W 0402")
      (fields
        (field (name "TOLERANCE") "±1%")
        (field (name "Comment") "Resistor")
        (field (name "PUBLISHER") "Altium Limited")
      )
      (libsource (lib "Database_Libs1") (part "Resistor"))
    )
    (comp (ref "R10")
      (value "100K")
      (footprint "RESC1005X40N")
      (description "RES SMD 100K OHM 1% 1/16W 0402")
      (fields
        (field (name "TOLERANCE") "±1%")
        (field (name "Comment") "Resistor")
        (field (name "PUBLISHER") "Altium Limited")
      )
      (libsource (lib "Database_Libs1") (part "Resistor"))
    )
    (comp (ref "R11")
      (value "10K")
      (footprint "RESC1005X40N")
      (description "RES SMD 10K OHM 1% 1/16W 0402")
      (fields
        (field (name "TOLERANCE") "±1%")
        (field (name "Comment") "Resistor")
        (field (name "PUBLISHER") "Altium Limited")
      )
      (libsource (lib "Database_Libs1") (part "Resistor"))
    )
    (comp (ref "R12")
      (value "100K")
      (footprint "RESC1005X40N")
      (description "RES SMD 100K OHM 1% 1/16W 0402")
      (fields
        (field (name "TOLERANCE") "±1%")
        (field (name "Comment") "Resistor")
        (field (name "PUBLISHER") "Altium Limited")
      )
      (libsource (lib "Database_Libs1") (part "Resistor"))
    )
    (comp (ref "R13")
      (value "1K")
      (footprint "RESC1005X40N")
      (description "RES SMD 1K OHM 1% 1/16W 0402")
      (fields
        (field (name "TOLERANCE") "±1%")
        (field (name "Comment") "Resistor")
        (field (name "PUBLISHER") "Altium Limited")
      )
      (libsource (lib "Database_Libs1") (part "Resistor"))
    )
    (comp (ref "R14")
      (value "10K")
      (footprint "RESC1005X40N")
      (description "RES SMD 10K OHM 1% 1/16W 0402")
      (fields
        (field (name "TOLERANCE") "±1%")
        (field (name "Comment") "Resistor")
        (field (name "PUBLISHER") "Altium Limited")
      )
      (libsource (lib "Database_Libs1") (part "Resistor"))
    )
    (comp (ref "R15")
      (value "1K")
      (footprint "RESC1005X40N")
      (description "RES SMD 1K OHM 1% 1/16W 0402")
      (fields
        (field (name "TOLERANCE") "±1%")
        (field (name "Comment") "Resistor")
        (field (name "PUBLISHER") "Altium Limited")
      )
      (libsource (lib "Database_Libs1") (part "Resistor"))
    )
    (comp (ref "R16")
      (value "1K")
      (footprint "RESC1005X40N")
      (description "RES SMD 1K OHM 1% 1/16W 0402")
      (fields
        (field (name "TOLERANCE") "±1%")
        (field (name "Comment") "Resistor")
        (field (name "PUBLISHER") "Altium Limited")
      )
      (libsource (lib "Database_Libs1") (part "Resistor"))
    )
    (comp (ref "R17")
      (value "4.7K")
      (footprint "RESC1005X40N")
      (description "RES SMD 4.7K OHM 1% 1/16W 0402")
      (fields
        (field (name "TOLERANCE") "±1%")
        (field (name "Comment") "Resistor")
        (field (name "PUBLISHER") "Altium Limited")
      )
      (libsource (lib "Database_Libs1") (part "Resistor"))
    )
    (comp (ref "R18")
      (value "1K")
      (footprint "RESC1005X40N")
      (description "RES SMD 1K OHM 1% 1/16W 0402")
      (fields
        (field (name "TOLERANCE") "±1%")
        (field (name "Comment") "Resistor")
        (field (name "PUBLISHER") "Altium Limited")
      )
      (libsource (lib "Database_Libs1") (part "Resistor"))
    )
    (comp (ref "R19")
      (value "54.9K")
      (footprint "RESC1005X40N")
      (description "RES SMD 54.9K OHM 1% 1/16W 0402")
      (fields
        (field (name "TOLERANCE") "±1%")
        (field (name "Comment") "Resistor")
        (field (name "PUBLISHER") "Altium Limited")
      )
      (libsource (lib "Database_Libs1") (part "Resistor"))
    )
    (comp (ref "R20")
      (value "1K")
      (footprint "RESC1005X40N")
      (description "RES SMD 1K OHM 1% 1/16W 0402")
      (fields
        (field (name "TOLERANCE") "±1%")
        (field (name "Comment") "Resistor")
        (field (name "PUBLISHER") "Altium Limited")
      )
      (libsource (lib "Database_Libs1") (part "Resistor"))
    )
    (comp (ref "R21")
      (value "10K")
      (footprint "RESC1005X40N")
      (description "RES SMD 10K OHM 1% 1/16W 0402")
      (fields
        (field (name "TOLERANCE") "±1%")
        (field (name "Comment") "Resistor")
        (field (name "PUBLISHER") "Altium Limited")
      )
      (libsource (lib "Database_Libs1") (part "Resistor"))
    )
    (comp (ref "R22")
      (value "100K")
      (footprint "RESC1005X40N")
      (description "RES SMD 100K OHM 1% 1/16W 0402")
      (fields
        (field (name "TOLERANCE") "±1%")
        (field (name "Comment") "Resistor")
        (field (name "PUBLISHER") "Altium Limited")
      )
      (libsource (lib "Database_Libs1") (part "Resistor"))
    )
    (comp (ref "R23")
      (value "10K")
      (footprint "RESC1005X40N")
      (description "RES SMD 10K OHM 1% 1/16W 0402")
      (fields
        (field (name "TOLERANCE") "±1%")
        (field (name "Comment") "Resistor")
        (field (name "PUBLISHER") "Altium Limited")
      )
      (libsource (lib "Database_Libs1") (part "Resistor"))
    )
    (comp (ref "R24")
      (value "100K")
      (footprint "RESC1005X40N")
      (description "RES SMD 100K OHM 1% 1/16W 0402")
      (fields
        (field (name "TOLERANCE") "±1%")
        (field (name "Comment") "Resistor")
        (field (name "PUBLISHER") "Altium Limited")
      )
      (libsource (lib "Database_Libs1") (part "Resistor"))
    )
    (comp (ref "R25")
      (value "10K")
      (footprint "RESC1005X40N")
      (description "RES SMD 10K OHM 1% 1/16W 0402")
      (fields
        (field (name "TOLERANCE") "±1%")
        (field (name "Comment") "Resistor")
        (field (name "PUBLISHER") "Altium Limited")
      )
      (libsource (lib "Database_Libs1") (part "Resistor"))
    )
    (comp (ref "R26")
      (value "100K")
      (footprint "RESC1005X40N")
      (description "RES SMD 100K OHM 1% 1/16W 0402")
      (fields
        (field (name "TOLERANCE") "±1%")
        (field (name "Comment") "Resistor")
        (field (name "PUBLISHER") "Altium Limited")
      )
      (libsource (lib "Database_Libs1") (part "Resistor"))
    )
    (comp (ref "R27")
      (value "10K")
      (footprint "RESC1005X40N")
      (description "RES SMD 10K OHM 1% 1/16W 0402")
      (fields
        (field (name "TOLERANCE") "±1%")
        (field (name "Comment") "Resistor")
        (field (name "PUBLISHER") "Altium Limited")
      )
      (libsource (lib "Database_Libs1") (part "Resistor"))
    )
    (comp (ref "R28")
      (value "100K")
      (footprint "RESC1005X40N")
      (description "RES SMD 100K OHM 1% 1/16W 0402")
      (fields
        (field (name "TOLERANCE") "±1%")
        (field (name "Comment") "Resistor")
        (field (name "PUBLISHER") "Altium Limited")
      )
      (libsource (lib "Database_Libs1") (part "Resistor"))
    )
    (comp (ref "R29")
      (value "10K")
      (footprint "RESC1005X40N")
      (description "RES SMD 10K OHM 1% 1/16W 0402")
      (fields
        (field (name "TOLERANCE") "±1%")
        (field (name "Comment") "Resistor")
        (field (name "PUBLISHER") "Altium Limited")
      )
      (libsource (lib "Database_Libs1") (part "Resistor"))
    )
    (comp (ref "R30")
      (value "100K")
      (footprint "RESC1005X40N")
      (description "RES SMD 100K OHM 1% 1/16W 0402")
      (fields
        (field (name "TOLERANCE") "±1%")
        (field (name "Comment") "Resistor")
        (field (name "PUBLISHER") "Altium Limited")
      )
      (libsource (lib "Database_Libs1") (part "Resistor"))
    )
    (comp (ref "R31")
      (value "22R")
      (footprint "RESC1005X40N")
      (description "RES SMD 22 OHM 1% 1/16W 0402")
      (fields
        (field (name "TOLERANCE") "±1%")
        (field (name "Comment") "Resistor")
        (field (name "PUBLISHER") "Altium Limited")
      )
      (libsource (lib "Database_Libs1") (part "Resistor"))
    )
    (comp (ref "R32")
      (value "100K")
      (footprint "RESC1005X40N")
      (description "RES SMD 100K OHM 1% 1/16W 0402")
      (fields
        (field (name "TOLERANCE") "±1%")
        (field (name "Comment") "Resistor")
        (field (name "PUBLISHER") "Altium Limited")
      )
      (libsource (lib "Database_Libs1") (part "Resistor"))
    )
    (comp (ref "R33")
      (value "1K")
      (footprint "RESC1005X40N")
      (description "RES SMD 1K OHM 1% 1/16W 0402")
      (fields
        (field (name "TOLERANCE") "±1%")
        (field (name "Comment") "Resistor")
        (field (name "PUBLISHER") "Altium Limited")
      )
      (libsource (lib "Database_Libs1") (part "Resistor"))
    )
    (comp (ref "R34")
      (value "22R")
      (footprint "RESC1005X40N")
      (description "RES SMD 22 OHM 1% 1/16W 0402")
      (fields
        (field (name "TOLERANCE") "±1%")
        (field (name "Comment") "Resistor")
        (field (name "PUBLISHER") "Altium Limited")
      )
      (libsource (lib "Database_Libs1") (part "Resistor"))
    )
    (comp (ref "R35")
      (value "100K")
      (footprint "RESC1005X40N")
      (description "RES SMD 100K OHM 1% 1/16W 0402")
      (fields
        (field (name "TOLERANCE") "±1%")
        (field (name "Comment") "Resistor")
        (field (name "PUBLISHER") "Altium Limited")
      )
      (libsource (lib "Database_Libs1") (part "Resistor"))
    )
    (comp (ref "R36")
      (value "1K")
      (footprint "RESC1005X40N")
      (description "RES SMD 1K OHM 1% 1/16W 0402")
      (fields
        (field (name "TOLERANCE") "±1%")
        (field (name "Comment") "Resistor")
        (field (name "PUBLISHER") "Altium Limited")
      )
      (libsource (lib "Database_Libs1") (part "Resistor"))
    )
    (comp (ref "R37")
      (value "22R")
      (footprint "RESC1005X40N")
      (description "RES SMD 22 OHM 1% 1/16W 0402")
      (fields
        (field (name "TOLERANCE") "±1%")
        (field (name "Comment") "Resistor")
        (field (name "PUBLISHER") "Altium Limited")
      )
      (libsource (lib "Database_Libs1") (part "Resistor"))
    )
    (comp (ref "R38")
      (value "100K")
      (footprint "RESC1005X40N")
      (description "RES SMD 100K OHM 1% 1/16W 0402")
      (fields
        (field (name "TOLERANCE") "±1%")
        (field (name "Comment") "Resistor")
        (field (name "PUBLISHER") "Altium Limited")
      )
      (libsource (lib "Database_Libs1") (part "Resistor"))
    )
    (comp (ref "R39")
      (value "1K")
      (footprint "RESC1005X40N")
      (description "RES SMD 1K OHM 1% 1/16W 0402")
      (fields
        (field (name "TOLERANCE") "±1%")
        (field (name "Comment") "Resistor")
        (field (name "PUBLISHER") "Altium Limited")
      )
      (libsource (lib "Database_Libs1") (part "Resistor"))
    )
    (comp (ref "R40")
      (value "4.7K")
      (footprint "RESC1005X40N")
      (description "RES SMD 4.7K OHM 1% 1/16W 0402")
      (fields
        (field (name "TOLERANCE") "±1%")
        (field (name "Comment") "Resistor")
        (field (name "PUBLISHER") "Altium Limited")
      )
      (libsource (lib "Database_Libs1") (part "Resistor"))
    )
    (comp (ref "R41")
      (value "4.7K")
      (footprint "RESC1005X40N")
      (description "RES SMD 4.7K OHM 1% 1/16W 0402")
      (fields
        (field (name "TOLERANCE") "±1%")
        (field (name "Comment") "Resistor")
        (field (name "PUBLISHER") "Altium Limited")
      )
      (libsource (lib "Database_Libs1") (part "Resistor"))
    )
    (comp (ref "R42")
      (value "4.7K")
      (footprint "RESC1005X40N")
      (description "RES SMD 4.7K OHM 1% 1/16W 0402")
      (fields
        (field (name "TOLERANCE") "±1%")
        (field (name "Comment") "Resistor")
        (field (name "PUBLISHER") "Altium Limited")
      )
      (libsource (lib "Database_Libs1") (part "Resistor"))
    )
    (comp (ref "R43")
      (value "4.7K")
      (footprint "RESC1005X40N")
      (description "RES SMD 4.7K OHM 1% 1/16W 0402")
      (fields
        (field (name "TOLERANCE") "±1%")
        (field (name "Comment") "Resistor")
        (field (name "PUBLISHER") "Altium Limited")
      )
      (libsource (lib "Database_Libs1") (part "Resistor"))
    )
    (comp (ref "R44")
      (value "100K")
      (footprint "RESC1005X40N")
      (description "RES SMD 100K OHM 1% 1/16W 0402")
      (fields
        (field (name "TOLERANCE") "±1%")
        (field (name "Comment") "Resistor")
        (field (name "PUBLISHER") "Altium Limited")
      )
      (libsource (lib "Database_Libs1") (part "Resistor"))
    )
    (comp (ref "R45")
      (value "10K")
      (footprint "RESC1005X40N")
      (description "RES SMD 10K OHM 1% 1/16W 0402")
      (fields
        (field (name "TOLERANCE") "±1%")
        (field (name "Comment") "Resistor")
        (field (name "PUBLISHER") "Altium Limited")
      )
      (libsource (lib "Database_Libs1") (part "Resistor"))
    )
    (comp (ref "R46")
      (value "22R")
      (footprint "RESC1005X40N")
      (description "RES SMD 22 OHM 1% 1/16W 0402")
      (fields
        (field (name "TOLERANCE") "±1%")
        (field (name "Comment") "Resistor")
        (field (name "PUBLISHER") "Altium Limited")
      )
      (libsource (lib "Database_Libs1") (part "Resistor"))
    )
    (comp (ref "R47")
      (value "100K")
      (footprint "RESC1005X40N")
      (description "RES SMD 100K OHM 1% 1/16W 0402")
      (fields
        (field (name "TOLERANCE") "±1%")
        (field (name "Comment") "Resistor")
        (field (name "PUBLISHER") "Altium Limited")
      )
      (libsource (lib "Database_Libs1") (part "Resistor"))
    )
    (comp (ref "R48")
      (value "22R")
      (footprint "RESC1005X40N")
      (description "RES SMD 22 OHM 1% 1/16W 0402")
      (fields
        (field (name "TOLERANCE") "±1%")
        (field (name "Comment") "Resistor")
        (field (name "PUBLISHER") "Altium Limited")
      )
      (libsource (lib "Database_Libs1") (part "Resistor"))
    )
    (comp (ref "R49")
      (value "100K")
      (footprint "RESC1005X40N")
      (description "RES SMD 100K OHM 1% 1/16W 0402")
      (fields
        (field (name "TOLERANCE") "±1%")
        (field (name "Comment") "Resistor")
        (field (name "PUBLISHER") "Altium Limited")
      )
      (libsource (lib "Database_Libs1") (part "Resistor"))
    )
    (comp (ref "R50")
      (value "1K")
      (footprint "RESC1005X40N")
      (description "RES SMD 1K OHM 1% 1/16W 0402")
      (fields
        (field (name "TOLERANCE") "±1%")
        (field (name "Comment") "Resistor")
        (field (name "PUBLISHER") "Altium Limited")
      )
      (libsource (lib "Database_Libs1") (part "Resistor"))
    )
    (comp (ref "R51")
      (value "22R")
      (footprint "RESC1005X40N")
      (description "RES SMD 22 OHM 1% 1/16W 0402")
      (fields
        (field (name "TOLERANCE") "±1%")
        (field (name "Comment") "Resistor")
        (field (name "PUBLISHER") "Altium Limited")
      )
      (libsource (lib "Database_Libs1") (part "Resistor"))
    )
    (comp (ref "R52")
      (value "100K")
      (footprint "RESC1005X40N")
      (description "RES SMD 100K OHM 1% 1/16W 0402")
      (fields
        (field (name "TOLERANCE") "±1%")
        (field (name "Comment") "Resistor")
        (field (name "PUBLISHER") "Altium Limited")
      )
      (libsource (lib "Database_Libs1") (part "Resistor"))
    )
    (comp (ref "R53")
      (value "1K")
      (footprint "RESC1005X40N")
      (description "RES SMD 1K OHM 1% 1/16W 0402")
      (fields
        (field (name "TOLERANCE") "±1%")
        (field (name "Comment") "Resistor")
        (field (name "PUBLISHER") "Altium Limited")
      )
      (libsource (lib "Database_Libs1") (part "Resistor"))
    )
    (comp (ref "R54")
      (value "4.7K")
      (footprint "RESC1005X40N")
      (description "RES SMD 4.7K OHM 1% 1/16W 0402")
      (fields
        (field (name "TOLERANCE") "±1%")
        (field (name "Comment") "Resistor")
        (field (name "PUBLISHER") "Altium Limited")
      )
      (libsource (lib "Database_Libs1") (part "Resistor"))
    )
    (comp (ref "R55")
      (value "1K")
      (footprint "RESC1005X40N")
      (description "RES SMD 1K OHM 1% 1/16W 0402")
      (fields
        (field (name "TOLERANCE") "±1%")
        (field (name "Comment") "Resistor")
        (field (name "PUBLISHER") "Altium Limited")
      )
      (libsource (lib "Database_Libs1") (part "Resistor"))
    )
    (comp (ref "R56")
      (value "140K")
      (footprint "RESC1005X40N")
      (description "RES SMD 140K OHM 1% 1/16W 0402")
      (fields
        (field (name "TOLERANCE") "±1%")
        (field (name "Comment") "Resistor")
        (field (name "PUBLISHER") "Altium Limited")
      )
      (libsource (lib "Database_Libs1") (part "Resistor"))
    )
    (comp (ref "R57")
      (value "10K")
      (footprint "RESC1005X40N")
      (description "RES SMD 10K OHM 1% 1/16W 0402")
      (fields
        (field (name "TOLERANCE") "±1%")
        (field (name "Comment") "Resistor")
        (field (name "PUBLISHER") "Altium Limited")
      )
      (libsource (lib "Database_Libs1") (part "Resistor"))
    )
    (comp (ref "R58")
      (value "1K")
      (footprint "RESC1005X40N")
      (description "RES SMD 1K OHM 1% 1/16W 0402")
      (fields
        (field (name "TOLERANCE") "±1%")
        (field (name "Comment") "Resistor")
        (field (name "PUBLISHER") "Altium Limited")
      )
      (libsource (lib "Database_Libs1") (part "Resistor"))
    )
    (comp (ref "R59")
      (value "4.7K")
      (footprint "RESC1005X40N")
      (description "RES SMD 4.7K OHM 1% 1/16W 0402")
      (fields
        (field (name "TOLERANCE") "±1%")
        (field (name "Comment") "Resistor")
        (field (name "PUBLISHER") "Altium Limited")
      )
      (libsource (lib "Database_Libs1") (part "Resistor"))
    )
    (comp (ref "R60")
      (value "10K")
      (footprint "RESC1005X40N")
      (description "RES SMD 10K OHM 1% 1/16W 0402")
      (fields
        (field (name "TOLERANCE") "±1%")
        (field (name "Comment") "Resistor")
        (field (name "PUBLISHER") "Altium Limited")
      )
      (libsource (lib "Database_Libs1") (part "Resistor"))
    )
    (comp (ref "R61")
      (value "4.7K")
      (footprint "RESC1005X40N")
      (description "RES SMD 4.7K OHM 1% 1/16W 0402")
      (fields
        (field (name "TOLERANCE") "±1%")
        (field (name "Comment") "Resistor")
        (field (name "PUBLISHER") "Altium Limited")
      )
      (libsource (lib "Database_Libs1") (part "Resistor"))
    )
    (comp (ref "R62")
      (value "1K")
      (footprint "RESC1005X40N")
      (description "RES SMD 1K OHM 1% 1/16W 0402")
      (fields
        (field (name "TOLERANCE") "±1%")
        (field (name "Comment") "Resistor")
        (field (name "PUBLISHER") "Altium Limited")
      )
      (libsource (lib "Database_Libs1") (part "Resistor"))
    )
    (comp (ref "R63")
      (value "10K")
      (footprint "RESC1005X40N")
      (description "RES SMD 10K OHM 1% 1/16W 0402")
      (fields
        (field (name "TOLERANCE") "±1%")
        (field (name "Comment") "Resistor")
        (field (name "PUBLISHER") "Altium Limited")
      )
      (libsource (lib "Database_Libs1") (part "Resistor"))
    )
    (comp (ref "R64")
      (value "1K")
      (footprint "RESC1005X40N")
      (description "RES SMD 1K OHM 1% 1/16W 0402")
      (fields
        (field (name "TOLERANCE") "±1%")
        (field (name "Comment") "Resistor")
        (field (name "PUBLISHER") "Altium Limited")
      )
      (libsource (lib "Database_Libs1") (part "Resistor"))
    )
    (comp (ref "R65")
      (value "1K")
      (footprint "RESC1005X40N")
      (description "RES SMD 1K OHM 1% 1/16W 0402")
      (fields
        (field (name "TOLERANCE") "±1%")
        (field (name "Comment") "Resistor")
        (field (name "PUBLISHER") "Altium Limited")
      )
      (libsource (lib "Database_Libs1") (part "Resistor"))
    )
    (comp (ref "R66")
      (value "1K")
      (footprint "RESC1005X40N")
      (description "RES SMD 1K OHM 1% 1/16W 0402")
      (fields
        (field (name "TOLERANCE") "±1%")
        (field (name "Comment") "Resistor")
        (field (name "PUBLISHER") "Altium Limited")
      )
      (libsource (lib "Database_Libs1") (part "Resistor"))
    )
    (comp (ref "R67")
      (value "4.7K")
      (footprint "RESC1005X40N")
      (description "RES SMD 4.7K OHM 1% 1/16W 0402")
      (fields
        (field (name "TOLERANCE") "±1%")
        (field (name "Comment") "Resistor")
        (field (name "PUBLISHER") "Altium Limited")
      )
      (libsource (lib "Database_Libs1") (part "Resistor"))
    )
    (comp (ref "R68")
      (value "1K")
      (footprint "RESC1005X40N")
      (description "RES SMD 1K OHM 1% 1/16W 0402")
      (fields
        (field (name "TOLERANCE") "±1%")
        (field (name "Comment") "Resistor")
        (field (name "PUBLISHER") "Altium Limited")
      )
      (libsource (lib "Database_Libs1") (part "Resistor"))
    )
    (comp (ref "R69")
      (value "10K")
      (footprint "RESC1005X40N")
      (description "RES SMD 10K OHM 1% 1/16W 0402")
      (fields
        (field (name "TOLERANCE") "±1%")
        (field (name "Comment") "Resistor")
        (field (name "PUBLISHER") "Altium Limited")
      )
      (libsource (lib "Database_Libs1") (part "Resistor"))
    )
    (comp (ref "R70")
      (value "4.7K")
      (footprint "RESC1005X40N")
      (description "RES SMD 4.7K OHM 1% 1/16W 0402")
      (fields
        (field (name "TOLERANCE") "±1%")
        (field (name "Comment") "Resistor")
        (field (name "PUBLISHER") "Altium Limited")
      )
      (libsource (lib "Database_Libs1") (part "Resistor"))
    )
    (comp (ref "R71")
      (value "1K")
      (footprint "RESC1005X40N")
      (description "RES SMD 1K OHM 1% 1/16W 0402")
      (fields
        (field (name "TOLERANCE") "±1%")
        (field (name "Comment") "Resistor")
        (field (name "PUBLISHER") "Altium Limited")
      )
      (libsource (lib "Database_Libs1") (part "Resistor"))
    )
    (comp (ref "R72")
      (value "10K")
      (footprint "RESC1005X40N")
      (description "RES SMD 10K OHM 1% 1/16W 0402")
      (fields
        (field (name "TOLERANCE") "±1%")
        (field (name "Comment") "Resistor")
        (field (name "PUBLISHER") "Altium Limited")
      )
      (libsource (lib "Database_Libs1") (part "Resistor"))
    )
    (comp (ref "R73")
      (value "4.7K")
      (footprint "RESC1005X40N")
      (description "RES SMD 4.7K OHM 1% 1/16W 0402")
      (fields
        (field (name "TOLERANCE") "±1%")
        (field (name "Comment") "Resistor")
        (field (name "PUBLISHER") "Altium Limited")
      )
      (libsource (lib "Database_Libs1") (part "Resistor"))
    )
    (comp (ref "R74")
      (value "1K")
      (footprint "RESC1005X40N")
      (description "RES SMD 1K OHM 1% 1/16W 0402")
      (fields
        (field (name "TOLERANCE") "±1%")
        (field (name "Comment") "Resistor")
        (field (name "PUBLISHER") "Altium Limited")
      )
      (libsource (lib "Database_Libs1") (part "Resistor"))
    )
    (comp (ref "R75")
      (value "10K")
      (footprint "RESC1005X40N")
      (description "RES SMD 10K OHM 1% 1/16W 0402")
      (fields
        (field (name "TOLERANCE") "±1%")
        (field (name "Comment") "Resistor")
        (field (name "PUBLISHER") "Altium Limited")
      )
      (libsource (lib "Database_Libs1") (part "Resistor"))
    )
    (comp (ref "R76")
      (value "4.7K")
      (footprint "RESC1005X40N")
      (description "RES SMD 4.7K OHM 1% 1/16W 0402")
      (fields
        (field (name "TOLERANCE") "±1%")
        (field (name "Comment") "Resistor")
        (field (name "PUBLISHER") "Altium Limited")
      )
      (libsource (lib "Database_Libs1") (part "Resistor"))
    )
    (comp (ref "R77")
      (value "1K")
      (footprint "RESC1005X40N")
      (description "RES SMD 1K OHM 1% 1/16W 0402")
      (fields
        (field (name "TOLERANCE") "±1%")
        (field (name "Comment") "Resistor")
        (field (name "PUBLISHER") "Altium Limited")
      )
      (libsource (lib "Database_Libs1") (part "Resistor"))
    )
    (comp (ref "R78")
      (value "10K")
      (footprint "RESC1005X40N")
      (description "RES SMD 10K OHM 1% 1/16W 0402")
      (fields
        (field (name "TOLERANCE") "±1%")
        (field (name "Comment") "Resistor")
        (field (name "PUBLISHER") "Altium Limited")
      )
      (libsource (lib "Database_Libs1") (part "Resistor"))
    )
    (comp (ref "R79")
      (value "10K")
      (footprint "RESC1005X40N")
      (description "RES SMD 10K OHM 1% 1/16W 0402")
      (fields
        (field (name "TOLERANCE") "±1%")
        (field (name "Comment") "Resistor")
        (field (name "PUBLISHER") "Altium Limited")
      )
      (libsource (lib "Database_Libs1") (part "Resistor"))
    )
    (comp (ref "R80")
      (value "10K")
      (footprint "RESC1005X40N")
      (description "RES SMD 10K OHM 1% 1/16W 0402")
      (fields
        (field (name "TOLERANCE") "±1%")
        (field (name "Comment") "Resistor")
        (field (name "PUBLISHER") "Altium Limited")
      )
      (libsource (lib "Database_Libs1") (part "Resistor"))
    )
    (comp (ref "R81")
      (value "10K")
      (footprint "RESC1005X40N")
      (description "RES SMD 10K OHM 1% 1/16W 0402")
      (fields
        (field (name "TOLERANCE") "±1%")
        (field (name "Comment") "Resistor")
        (field (name "PUBLISHER") "Altium Limited")
      )
      (libsource (lib "Database_Libs1") (part "Resistor"))
    )
    (comp (ref "R82")
      (value "10K")
      (footprint "RESC1005X40N")
      (description "RES SMD 10K OHM 1% 1/16W 0402")
      (fields
        (field (name "TOLERANCE") "±1%")
        (field (name "Comment") "Resistor")
        (field (name "PUBLISHER") "Altium Limited")
      )
      (libsource (lib "Database_Libs1") (part "Resistor"))
    )
    (comp (ref "R83")
      (value "10K")
      (footprint "RESC1005X40N")
      (description "RES SMD 10K OHM 1% 1/16W 0402")
      (fields
        (field (name "TOLERANCE") "±1%")
        (field (name "Comment") "Resistor")
        (field (name "PUBLISHER") "Altium Limited")
      )
      (libsource (lib "Database_Libs1") (part "Resistor"))
    )
    (comp (ref "R84")
      (value "10K")
      (footprint "RESC1005X40N")
      (description "RES SMD 10K OHM 1% 1/16W 0402")
      (fields
        (field (name "TOLERANCE") "±1%")
        (field (name "Comment") "Resistor")
        (field (name "PUBLISHER") "Altium Limited")
      )
      (libsource (lib "Database_Libs1") (part "Resistor"))
    )
    (comp (ref "R85")
      (value "10K")
      (footprint "RESC1005X40N")
      (description "RES SMD 10K OHM 1% 1/16W 0402")
      (fields
        (field (name "TOLERANCE") "±1%")
        (field (name "Comment") "Resistor")
        (field (name "PUBLISHER") "Altium Limited")
      )
      (libsource (lib "Database_Libs1") (part "Resistor"))
    )
    (comp (ref "S1")
      (value "Momentary Tactile Button")
      (footprint "SW-PB SMD 2pin")
      (description "SWITCH TACTILE SPST-NO 0.05A 12V")
      (libsource (lib "picoprint_library") (part "SW-PB"))
    )
    (comp (ref "S3")
      (value "Momentary Tactile Button")
      (footprint "SW-PB SMD 2pin")
      (description "SWITCH TACTILE SPST-NO 0.05A 12V")
      (libsource (lib "picoprint_library") (part "SW-PB"))
    )
    (comp (ref "sc1") (value "Sraf") (footprint "Sraf 3mm - rupa 3.2") (libsource (lib "gc") (part "Sraf")))
    (comp (ref "sc2") (value "Sraf") (footprint "Sraf 3mm - rupa 3.2") (libsource (lib "gc") (part "Sraf")))
    (comp (ref "sc3") (value "Sraf") (footprint "Sraf 3mm - rupa 3.5") (libsource (lib "gc") (part "Sraf")))
    (comp (ref "sc4") (value "Sraf") (footprint "Sraf 3mm - rupa 3.5") (libsource (lib "gc") (part "Sraf")))
    (comp (ref "SERVO")
      (value "Header 3")
      (footprint "HDR1X3-HEADER")
      (description "Header, 3-Pin")
      (fields (field (name "PUBLISHER") "Altium Limited"))
      (libsource (lib "RUMBA_v2") (part "Header 3"))
    )
    (comp (ref "SWD")
      (value "Header 3X2")
      (footprint "HDR2X3")
      (description "Header, 3-Pin, Dual row")
      (fields (field (name "PUBLISHER") "Altium Limited"))
      (libsource (lib "RUMBA_v2") (part "Header 3X2"))
    )
    (comp (ref "Thermistors")
      (value "Header 5X2")
      (footprint "HDR2X5")
      (description "Header, 5-Pin, Dual row")
      (fields (field (name "PUBLISHER") "Altium Limited"))
      (libsource (lib "RUMBA_v2") (part "Header 5X2"))
    )
    (comp (ref "U1")
      (value "STM32F446VET6")
      (footprint "STM-LQFP100_N")
      (description "IC MCU 32BIT 512KB FLASH 100LQFP")
      (fields (field (name "MANUFACTURER") "STMicroelectronics") (field (name "PARTNUMBER") "STM32F407VGT7"))
      (libsource (lib "picoprint_library") (part "STM32F446VET6_Big"))
    )
    (comp (ref "U2")
      (value "74LVC1G17SE-7")
      (footprint "SOT353")
      (description "IC BUF NON-INVERT 5.5V SOT353")
      (libsource (lib "picoprint_library") (part "Buffer Non-Inverting Schmitt Trigger 74LVC1G17SE-7"))
    )
    (comp (ref "U3")
      (value "AP63205")
      (footprint "TSOT23-6")
      (description "IC REG BUCK 5V 2A SOT23-6")
      (libsource (lib "main_library") (part "Regulator - AP63205 Buck Regulator"))
    )
    (comp (ref "U4")
      (value "AOZ1284")
      (footprint "SOIC127P600X170_HS-9N")
      (description "IC REG BUCK ADJ 4A 8SO")
      (libsource (lib "picoprint_library") (part "Regulator - AOZ1284 4A Buck Regulator"))
    )
    (comp (ref "U5")
      (value "USBLC6-4SC6")
      (footprint "TSOT23-6")
      (description "DIODE TVS 5.25V 17V SOT23-6")
      (libsource (lib "main_library") (part "USBLC6-4SC6 USB ESD Protection"))
    )
    (comp (ref "U6")
      (value "AP2112K-3.3TRG1")
      (footprint "SOT23-5")
      (description "IC REG LINEAR 3.3V 600MA SOT25")
      (libsource (lib "picoprint_library") (part "Regulator - AP2112K 3.3V Linear Regulator"))
    )
    (comp (ref "U7")
      (value "24LC64T-I/OT")
      (footprint "SOT23-5")
      (description "IC EEPROM 64K I2C SOT23-5")
      (libsource (lib "picoprint_library") (part "EEPROM - Serial I2C"))
    )
    (comp (ref "USB_AUX")
      (value "Header 5")
      (footprint "HDR1X5-HEADER")
      (description "Header, 5-Pin")
      (fields (field (name "PUBLISHER") "Altium Limited"))
      (libsource (lib "picoprint_library") (part "Header 5x1"))
    )
    (comp (ref "VFA0_sel")
      (value "Header 3")
      (footprint "HDR1X3-HEADER")
      (description "Header, 3-Pin")
      (fields (field (name "PUBLISHER") "Altium Limited"))
      (libsource (lib "") (part "Header 3_1"))
    )
    (comp (ref "VFA1_sel")
      (value "Header 3")
      (footprint "HDR1X3-HEADER")
      (description "Header, 3-Pin")
      (fields (field (name "PUBLISHER") "Altium Limited"))
      (libsource (lib "") (part "Header 3_1"))
    )
    (comp (ref "VHE2_sel")
      (value "Header 3")
      (footprint "HDR1X3-HEADER")
      (description "Header, 3-Pin")
      (fields (field (name "PUBLISHER") "Altium Limited"))
      (libsource (lib "") (part "Header 3_1"))
    )
    (comp (ref "X")
      (value "Header 8")
      (footprint "A4988BREAKOUT_2")
      (description "Header, 8-Pin, Female")
      (libsource (lib "main_library") (part "STEPSTICK_BREAKOUT"))
    )
    (comp (ref "X+")
      (value "Header 3")
      (footprint "HDR1X3-HEADER")
      (description "Header, 3-Pin")
      (fields (field (name "PUBLISHER") "Altium Limited"))
      (libsource (lib "RUMBA_v2") (part "Header 3"))
    )
    (comp (ref "X-")
      (value "Header 3")
      (footprint "HDR1X3-HEADER")
      (description "Header, 3-Pin")
      (fields (field (name "PUBLISHER") "Altium Limited"))
      (libsource (lib "RUMBA_v2") (part "Header 3"))
    )
    (comp (ref "XT1")
      (value "12MHz 33pF 0.5%")
      (footprint "CERALOCK CSTCE_G")
      (description "CER RES 12.0000MHZ 33PF SMD")
      (libsource (lib "picoprint_library") (part "Ceramic Resonator CSTCE12M0G55-R0"))
    )
    (comp (ref "X_0")
      (value "Header 8")
      (footprint "HDR1X8-HEADER")
      (description "Header, 8-Pin, Female")
      (fields (field (name "PUBLISHER") "Altium Limited"))
      (libsource (lib "picoprint_library") (part "Header 8x1"))
    )
    (comp (ref "X_1")
      (value "Header 8")
      (footprint "HDR1X8-HEADER")
      (description "Header, 8-Pin, Female")
      (fields (field (name "PUBLISHER") "Altium Limited"))
      (libsource (lib "picoprint_library") (part "Header 8x1"))
    )
    (comp (ref "X_DIAG")
      (value "Header 2")
      (footprint "HDR1X2-HEADER Female")
      (description "Header, 2-Pin, Female")
      (libsource (lib "main_library") (part "Header 1X2 Female"))
    )
    (comp (ref "X_MOT")
      (value "~")
      (footprint "TERM4 3.5mm")
      (description "TERM BLK 4POS SIDE ENT 3.5MM PCB")
      (fields (field (name "PUBLISHER") "Altium Limited"))
      (libsource (lib "RUMBA_v2") (part "ScrewTerminal-3.5mm-4Way"))
    )
    (comp (ref "X_MOT_A")
      (value "Header 4")
      (footprint "HDR1X4")
      (description "Header, 4-Pin")
      (fields (field (name "PUBLISHER") "Altium Limited"))
      (libsource (lib "RUMBA_v2") (part "Header 4_1"))
    )
    (comp (ref "X_MS1")
      (value "Header 3")
      (footprint "HDR1X3-HEADER")
      (description "Header, 3-Pin")
      (fields (field (name "PUBLISHER") "Altium Limited"))
      (libsource (lib "RUMBA_library") (part "Header 3"))
    )
    (comp (ref "X_MS2")
      (value "Header 3")
      (footprint "HDR1X3-HEADER")
      (description "Header, 3-Pin")
      (fields (field (name "PUBLISHER") "Altium Limited"))
      (libsource (lib "RUMBA_library") (part "Header 3"))
    )
    (comp (ref "X_MS3")
      (value "Header 3")
      (footprint "HDR1X3-HEADER")
      (description "Header, 3-Pin")
      (fields (field (name "PUBLISHER") "Altium Limited"))
      (libsource (lib "RUMBA_library") (part "Header 3"))
    )
    (comp (ref "X_RST")
      (value "Header 3")
      (footprint "HDR1X3-HEADER")
      (description "Header, 3-Pin")
      (fields (field (name "PUBLISHER") "Altium Limited"))
      (libsource (lib "RUMBA_library") (part "Header 3"))
    )
    (comp (ref "Y")
      (value "Header 8")
      (footprint "A4988BREAKOUT_2")
      (description "Header, 8-Pin, Female")
      (libsource (lib "main_library") (part "STEPSTICK_BREAKOUT"))
    )
    (comp (ref "Y+")
      (value "Header 3")
      (footprint "HDR1X3-HEADER")
      (description "Header, 3-Pin")
      (fields (field (name "PUBLISHER") "Altium Limited"))
      (libsource (lib "RUMBA_v2") (part "Header 3"))
    )
    (comp (ref "Y-")
      (value "Header 3")
      (footprint "HDR1X3-HEADER")
      (description "Header, 3-Pin")
      (fields (field (name "PUBLISHER") "Altium Limited"))
      (libsource (lib "RUMBA_v2") (part "Header 3"))
    )
    (comp (ref "Y_0")
      (value "Header 8")
      (footprint "HDR1X8-HEADER")
      (description "Header, 8-Pin, Female")
      (fields (field (name "PUBLISHER") "Altium Limited"))
      (libsource (lib "picoprint_library") (part "Header 8x1"))
    )
    (comp (ref "Y_1")
      (value "Header 8")
      (footprint "HDR1X8-HEADER")
      (description "Header, 8-Pin, Female")
      (fields (field (name "PUBLISHER") "Altium Limited"))
      (libsource (lib "picoprint_library") (part "Header 8x1"))
    )
    (comp (ref "Y_DIAG")
      (value "Header 2")
      (footprint "HDR1X2-HEADER Female")
      (description "Header, 2-Pin, Female")
      (libsource (lib "main_library") (part "Header 1X2 Female"))
    )
    (comp (ref "Y_MOT")
      (value "~")
      (footprint "TERM4 3.5mm")
      (description "TERM BLK 4POS SIDE ENT 3.5MM PCB")
      (fields (field (name "PUBLISHER") "Altium Limited"))
      (libsource (lib "RUMBA_v2") (part "ScrewTerminal-3.5mm-4Way"))
    )
    (comp (ref "Y_MOT_A")
      (value "Header 4")
      (footprint "HDR1X4")
      (description "Header, 4-Pin")
      (fields (field (name "PUBLISHER") "Altium Limited"))
      (libsource (lib "RUMBA_v2") (part "Header 4_1"))
    )
    (comp (ref "Y_MS1")
      (value "Header 3")
      (footprint "HDR1X3-HEADER")
      (description "Header, 3-Pin")
      (fields (field (name "PUBLISHER") "Altium Limited"))
      (libsource (lib "RUMBA_library") (part "Header 3"))
    )
    (comp (ref "Y_MS2")
      (value "Header 3")
      (footprint "HDR1X3-HEADER")
      (description "Header, 3-Pin")
      (fields (field (name "PUBLISHER") "Altium Limited"))
      (libsource (lib "RUMBA_library") (part "Header 3"))
    )
    (comp (ref "Y_MS3")
      (value "Header 3")
      (footprint "HDR1X3-HEADER")
      (description "Header, 3-Pin")
      (fields (field (name "PUBLISHER") "Altium Limited"))
      (libsource (lib "RUMBA_library") (part "Header 3"))
    )
    (comp (ref "Y_RST")
      (value "Header 3")
      (footprint "HDR1X3-HEADER")
      (description "Header, 3-Pin")
      (fields (field (name "PUBLISHER") "Altium Limited"))
      (libsource (lib "RUMBA_library") (part "Header 3"))
    )
    (comp (ref "Z")
      (value "Header 8")
      (footprint "A4988BREAKOUT_2")
      (description "Header, 8-Pin, Female")
      (libsource (lib "main_library") (part "STEPSTICK_BREAKOUT"))
    )
    (comp (ref "Z+")
      (value "Header 3")
      (footprint "HDR1X3-HEADER")
      (description "Header, 3-Pin")
      (fields (field (name "PUBLISHER") "Altium Limited"))
      (libsource (lib "RUMBA_v2") (part "Header 3"))
    )
    (comp (ref "Z-")
      (value "Header 3")
      (footprint "HDR1X3-HEADER")
      (description "Header, 3-Pin")
      (fields (field (name "PUBLISHER") "Altium Limited"))
      (libsource (lib "RUMBA_v2") (part "Header 3"))
    )
    (comp (ref "Z_0")
      (value "Header 8")
      (footprint "HDR1X8-HEADER")
      (description "Header, 8-Pin, Female")
      (fields (field (name "PUBLISHER") "Altium Limited"))
      (libsource (lib "picoprint_library") (part "Header 8x1"))
    )
    (comp (ref "Z_1")
      (value "Header 8")
      (footprint "HDR1X8-HEADER")
      (description "Header, 8-Pin, Female")
      (fields (field (name "PUBLISHER") "Altium Limited"))
      (libsource (lib "picoprint_library") (part "Header 8x1"))
    )
    (comp (ref "Z_DIAG")
      (value "Header 2")
      (footprint "HDR1X2-HEADER Female")
      (description "Header, 2-Pin, Female")
      (libsource (lib "main_library") (part "Header 1X2 Female"))
    )
    (comp (ref "Z_MOT")
      (value "~")
      (footprint "TERM4 3.5mm")
      (description "TERM BLK 4POS SIDE ENT 3.5MM PCB")
      (fields (field (name "PUBLISHER") "Altium Limited"))
      (libsource (lib "RUMBA_v2") (part "ScrewTerminal-3.5mm-4Way"))
    )
    (comp (ref "Z_MOT_A")
      (value "Header 4")
      (footprint "HDR1X4")
      (description "Header, 4-Pin")
      (fields (field (name "PUBLISHER") "Altium Limited"))
      (libsource (lib "RUMBA_v2") (part "Header 4_1"))
    )
    (comp (ref "Z_MS1")
      (value "Header 3")
      (footprint "HDR1X3-HEADER")
      (description "Header, 3-Pin")
      (fields (field (name "PUBLISHER") "Altium Limited"))
      (libsource (lib "RUMBA_library") (part "Header 3"))
    )
    (comp (ref "Z_MS2")
      (value "Header 3")
      (footprint "HDR1X3-HEADER")
      (description "Header, 3-Pin")
      (fields (field (name "PUBLISHER") "Altium Limited"))
      (libsource (lib "RUMBA_library") (part "Header 3"))
    )
    (comp (ref "Z_MS3")
      (value "Header 3")
      (footprint "HDR1X3-HEADER")
      (description "Header, 3-Pin")
      (fields (field (name "PUBLISHER") "Altium Limited"))
      (libsource (lib "RUMBA_library") (part "Header 3"))
    )
    (comp (ref "Z_RST")
      (value "Header 3")
      (footprint "HDR1X3-HEADER")
      (description "Header, 3-Pin")
      (fields (field (name "PUBLISHER") "Altium Limited"))
      (libsource (lib "RUMBA_library") (part "Header 3"))
    )
  )
  (nets
    (net (code "1") (name "+3V3") (class "Default")
      (node (ref "3V3") (pin "1") (pinfunction "1_1") (pintype "passive"))
      (node (ref "C12") (pin "2") (pinfunction "2_2") (pintype "passive"))
      (node (ref "C13") (pin "2") (pinfunction "2_2") (pintype "passive"))
      (node (ref "C14") (pin "2") (pinfunction "2_2") (pintype "passive"))
      (node (ref "C15") (pin "2") (pinfunction "2_2") (pintype "passive"))
      (node (ref "C16") (pin "2") (pinfunction "2_2") (pintype "passive"))
      (node (ref "C19") (pin "2") (pinfunction "2_2") (pintype "passive"))
      (node (ref "C39") (pin "2") (pinfunction "2_2") (pintype "passive"))
      (node (ref "C40") (pin "2") (pinfunction "2_2") (pintype "passive"))
      (node (ref "C7") (pin "2") (pinfunction "2_2") (pintype "passive"))
      (node (ref "FB1") (pin "2") (pinfunction "2_2") (pintype "passive"))
      (node (ref "J1") (pin "1") (pinfunction "1_1") (pintype "passive"))
      (node (ref "J3") (pin "1") (pinfunction "1_1") (pintype "passive"))
      (node (ref "LD11") (pin "1") (pinfunction "A_1") (pintype "passive"))
      (node (ref "R11") (pin "2") (pinfunction "2_2") (pintype "passive"))
      (node (ref "R2") (pin "2") (pinfunction "2_2") (pintype "passive"))
      (node (ref "R3") (pin "2") (pinfunction "2_2") (pintype "passive"))
      (node (ref "S3") (pin "1") (pintype "passive"))
      (node (ref "SWD") (pin "2") (pinfunction "2_2") (pintype "passive"))
      (node (ref "U1") (pin "100") (pinfunction "VDD_100") (pintype "power_in"))
      (node (ref "U1") (pin "11") (pinfunction "VDD_11") (pintype "power_in"))
      (node (ref "U1") (pin "19") (pinfunction "VDD_19") (pintype "power_in"))
      (node (ref "U1") (pin "28") (pinfunction "VDD_28") (pintype "power_in"))
      (node (ref "U1") (pin "50") (pinfunction "VDD_50") (pintype "power_in"))
      (node (ref "U1") (pin "6") (pinfunction "VBAT_6") (pintype "power_in"))
      (node (ref "U1") (pin "75") (pinfunction "VDD_75") (pintype "power_in"))
      (node (ref "U6") (pin "5") (pinfunction "Vout_5") (pintype "passive"))
      (node (ref "U7") (pin "4") (pinfunction "VDD_4") (pintype "passive"))
    )
    (net (code "2") (name "+3V3A") (class "Default")
      (node (ref "C20") (pin "2") (pinfunction "2_2") (pintype "passive"))
      (node (ref "C35") (pin "2") (pinfunction "2_2") (pintype "passive"))
      (node (ref "FB1") (pin "1") (pinfunction "1_1") (pintype "passive"))
      (node (ref "R40") (pin "1") (pinfunction "1_1") (pintype "passive"))
      (node (ref "R41") (pin "1") (pinfunction "1_1") (pintype "passive"))
      (node (ref "R42") (pin "1") (pinfunction "1_1") (pintype "passive"))
      (node (ref "R43") (pin "1") (pinfunction "1_1") (pintype "passive"))
      (node (ref "R54") (pin "1") (pinfunction "1_1") (pintype "passive"))
      (node (ref "U1") (pin "21") (pinfunction "VREF+_21") (pintype "power_in"))
      (node (ref "U1") (pin "22") (pinfunction "VDDA_22") (pintype "power_in"))
    )
    (net (code "3") (name "+5V") (class "Default")
      (node (ref "5V") (pin "1") (pinfunction "1_1") (pintype "passive"))
      (node (ref "C38") (pin "2") (pinfunction "2_2") (pintype "passive"))
      (node (ref "C4") (pin "2") (pinfunction "2_2") (pintype "passive"))
      (node (ref "D15") (pin "K") (pinfunction "K_K") (pintype "passive"))
      (node (ref "D3") (pin "A") (pinfunction "A_A") (pintype "passive"))
      (node (ref "D4") (pin "K") (pinfunction "K_K") (pintype "passive"))
      (node (ref "EXP1") (pin "10") (pinfunction "10_10") (pintype "passive"))
      (node (ref "EXP3") (pin "2") (pinfunction "2_2") (pintype "passive"))
      (node (ref "I2C_1") (pin "4") (pinfunction "4_4") (pintype "passive"))
      (node (ref "I2C_2") (pin "4") (pinfunction "4_4") (pintype "passive"))
      (node (ref "J1") (pin "3") (pinfunction "3_3") (pintype "passive"))
      (node (ref "J3") (pin "3") (pinfunction "3_3") (pintype "passive"))
      (node (ref "LD9") (pin "1") (pinfunction "A_1") (pintype "passive"))
      (node (ref "R80") (pin "2") (pinfunction "2_2") (pintype "passive"))
      (node (ref "SERVO") (pin "2") (pinfunction "2_2") (pintype "passive"))
      (node (ref "U2") (pin "5") (pinfunction "VCC_5") (pintype "passive"))
      (node (ref "U6") (pin "1") (pinfunction "Vin_1") (pintype "passive"))
      (node (ref "U6") (pin "3") (pinfunction "EN_3") (pintype "passive"))
    )
    (net (code "4") (name "+12V") (class "Default")
      (node (ref "12V") (pin "1") (pinfunction "1_1") (pintype "passive"))
      (node (ref "C32") (pin "1") (pinfunction "1_1") (pintype "passive"))
      (node (ref "C45") (pin "2") (pinfunction "2_2") (pintype "passive"))
      (node (ref "EXP3") (pin "1") (pinfunction "1_1") (pintype "passive"))
      (node (ref "L2") (pin "2") (pinfunction "2_2") (pintype "passive"))
      (node (ref "LD10") (pin "1") (pinfunction "A_1") (pintype "passive"))
      (node (ref "R56") (pin "1") (pinfunction "1_1") (pintype "passive"))
      (node (ref "VFA0_sel") (pin "3") (pinfunction "3_3") (pintype "passive"))
      (node (ref "VFA1_sel") (pin "3") (pinfunction "3_3") (pintype "passive"))
      (node (ref "VHE2_sel") (pin "3") (pinfunction "3_3") (pintype "passive"))
    )
    (net (code "5") (name "+DRV") (class "Default")
      (node (ref "E0") (pin "10") (pinfunction "VDD_10") (pintype "passive"))
      (node (ref "E0_MS1") (pin "1") (pinfunction "1_1") (pintype "passive"))
      (node (ref "E0_MS2") (pin "1") (pinfunction "1_1") (pintype "passive"))
      (node (ref "E0_MS3") (pin "1") (pinfunction "1_1") (pintype "passive"))
      (node (ref "E1") (pin "10") (pinfunction "VDD_10") (pintype "passive"))
      (node (ref "E1_MS1") (pin "1") (pinfunction "1_1") (pintype "passive"))
      (node (ref "E1_MS2") (pin "1") (pinfunction "1_1") (pintype "passive"))
      (node (ref "E1_MS3") (pin "1") (pinfunction "1_1") (pintype "passive"))
      (node (ref "E2") (pin "10") (pinfunction "VDD_10") (pintype "passive"))
      (node (ref "E2_MS1") (pin "1") (pinfunction "1_1") (pintype "passive"))
      (node (ref "E2_MS2") (pin "1") (pinfunction "1_1") (pintype "passive"))
      (node (ref "E2_MS3") (pin "1") (pinfunction "1_1") (pintype "passive"))
      (node (ref "J3") (pin "2") (pinfunction "2_2") (pintype "passive"))
      (node (ref "R21") (pin "1") (pinfunction "1_1") (pintype "passive"))
      (node (ref "R23") (pin "1") (pinfunction "1_1") (pintype "passive"))
      (node (ref "R25") (pin "1") (pinfunction "1_1") (pintype "passive"))
      (node (ref "R27") (pin "1") (pinfunction "1_1") (pintype "passive"))
      (node (ref "R29") (pin "1") (pinfunction "1_1") (pintype "passive"))
      (node (ref "R45") (pin "1") (pinfunction "1_1") (pintype "passive"))
      (node (ref "X") (pin "10") (pinfunction "VDD_10") (pintype "passive"))
      (node (ref "X_MS1") (pin "1") (pinfunction "1_1") (pintype "passive"))
      (node (ref "X_MS2") (pin "1") (pinfunction "1_1") (pintype "passive"))
      (node (ref "X_MS3") (pin "1") (pinfunction "1_1") (pintype "passive"))
      (node (ref "Y") (pin "10") (pinfunction "VDD_10") (pintype "passive"))
      (node (ref "Y_MS1") (pin "1") (pinfunction "1_1") (pintype "passive"))
      (node (ref "Y_MS2") (pin "1") (pinfunction "1_1") (pintype "passive"))
      (node (ref "Y_MS3") (pin "1") (pinfunction "1_1") (pintype "passive"))
      (node (ref "Z") (pin "10") (pinfunction "VDD_10") (pintype "passive"))
      (node (ref "Z_MS1") (pin "1") (pinfunction "1_1") (pintype "passive"))
      (node (ref "Z_MS2") (pin "1") (pinfunction "1_1") (pintype "passive"))
      (node (ref "Z_MS3") (pin "1") (pinfunction "1_1") (pintype "passive"))
    )
    (net (code "6") (name "+V_STOP") (class "Default")
      (node (ref "J1") (pin "2") (pinfunction "2_2") (pintype "passive"))
      (node (ref "R17") (pin "1") (pinfunction "1_1") (pintype "passive"))
      (node (ref "R61") (pin "1") (pinfunction "1_1") (pintype "passive"))
      (node (ref "R67") (pin "1") (pinfunction "1_1") (pintype "passive"))
      (node (ref "R70") (pin "1") (pinfunction "1_1") (pintype "passive"))
      (node (ref "R73") (pin "1") (pinfunction "1_1") (pintype "passive"))
      (node (ref "R76") (pin "1") (pinfunction "1_1") (pintype "passive"))
      (node (ref "X+") (pin "3") (pinfunction "3_3") (pintype "passive"))
      (node (ref "X-") (pin "3") (pinfunction "3_3") (pintype "passive"))
      (node (ref "Y+") (pin "3") (pinfunction "3_3") (pintype "passive"))
      (node (ref "Y-") (pin "3") (pinfunction "3_3") (pintype "passive"))
      (node (ref "Z+") (pin "3") (pinfunction "3_3") (pintype "passive"))
      (node (ref "Z-") (pin "3") (pinfunction "3_3") (pintype "passive"))
    )
    (net (code "7") (name "/BEEPER") (class "Default")
      (node (ref "EXP1") (pin "1") (pinfunction "1_1") (pintype "passive"))
      (node (ref "U1") (pin "39") (pinfunction "PE8_39") (pintype "bidirectional"))
    )
    (net (code "8") (name "/BOOT0") (class "Default")
      (node (ref "R14") (pin "2") (pinfunction "2_2") (pintype "passive"))
      (node (ref "S3") (pin "2") (pintype "passive"))
      (node (ref "SWD") (pin "4") (pinfunction "4_4") (pintype "passive"))
      (node (ref "U1") (pin "94") (pinfunction "BOOT0_94") (pintype "input"))
    )
    (net (code "9") (name "/BTN_EN1") (class "Default")
      (node (ref "EXP2") (pin "5") (pinfunction "5_5") (pintype "passive"))
      (node (ref "U1") (pin "36") (pinfunction "PB1_36") (pintype "bidirectional"))
    )
    (net (code "10") (name "/BTN_EN2") (class "Default")
      (node (ref "EXP2") (pin "3") (pinfunction "3_3") (pintype "passive"))
      (node (ref "R12") (pin "2") (pinfunction "2_2") (pintype "passive"))
      (node (ref "U1") (pin "37") (pinfunction "PB2-BOOT1(PB2)_37") (pintype "bidirectional"))
    )
    (net (code "11") (name "/BTN_ENC") (class "Default")
      (node (ref "EXP1") (pin "2") (pinfunction "2_2") (pintype "passive"))
      (node (ref "U1") (pin "38") (pinfunction "PE7_38") (pintype "bidirectional"))
    )
    (net (code "12") (name "/E0-CS{slash}RX") (class "Default")
      (node (ref "E0_MS3") (pin "3") (pinfunction "3_3") (pintype "passive"))
      (node (ref "R64") (pin "1") (pinfunction "1_1") (pintype "passive"))
      (node (ref "U1") (pin "7") (pinfunction "PC13_7") (pintype "bidirectional"))
    )
    (net (code "13") (name "/E0-DIR") (class "Default")
      (node (ref "E0") (pin "8") (pinfunction "DIR_8") (pintype "passive"))
      (node (ref "U1") (pin "92") (pinfunction "PB6_92") (pintype "bidirectional"))
    )
    (net (code "14") (name "/E0-EN") (class "Default")
      (node (ref "E0") (pin "1") (pinfunction "~{ENA}_1") (pintype "passive"))
      (node (ref "R27") (pin "2") (pinfunction "2_2") (pintype "passive"))
      (node (ref "U1") (pin "80") (pinfunction "PC12_80") (pintype "bidirectional"))
    )
    (net (code "15") (name "/E0-STEP") (class "Default")
      (node (ref "E0") (pin "7") (pinfunction "STEP_7") (pintype "passive"))
      (node (ref "U1") (pin "91") (pinfunction "PB5_91") (pintype "bidirectional"))
    )
    (net (code "16") (name "/E0-TX") (class "Default")
      (node (ref "R64") (pin "2") (pinfunction "2_2") (pintype "passive"))
      (node (ref "U1") (pin "58") (pinfunction "PD11_58") (pintype "bidirectional"))
    )
    (net (code "17") (name "/E0-~{SLP}") (class "Default")
      (node (ref "E0") (pin "6") (pinfunction "~{SLEEP}_6") (pintype "passive"))
      (node (ref "E0_RST") (pin "1") (pinfunction "1_1") (pintype "passive"))
    )
    (net (code "18") (name "/E1-CS{slash}RX") (class "Default")
      (node (ref "E1_MS3") (pin "3") (pinfunction "3_3") (pintype "passive"))
      (node (ref "R65") (pin "1") (pinfunction "1_1") (pintype "passive"))
      (node (ref "U1") (pin "86") (pinfunction "PD5_86") (pintype "bidirectional"))
    )
    (net (code "19") (name "/E1-DIR") (class "Default")
      (node (ref "E1") (pin "8") (pinfunction "DIR_8") (pintype "passive"))
      (node (ref "U1") (pin "88") (pinfunction "PD7_88") (pintype "bidirectional"))
    )
    (net (code "20") (name "/E1-EN") (class "Default")
      (node (ref "E1") (pin "1") (pinfunction "~{ENA}_1") (pintype "passive"))
      (node (ref "R29") (pin "2") (pinfunction "2_2") (pintype "passive"))
      (node (ref "U1") (pin "85") (pinfunction "PD4_85") (pintype "bidirectional"))
    )
    (net (code "21") (name "/E1-STEP") (class "Default")
      (node (ref "E1") (pin "7") (pinfunction "STEP_7") (pintype "passive"))
      (node (ref "U1") (pin "87") (pinfunction "PD6_87") (pintype "bidirectional"))
    )
    (net (code "22") (name "/E1-TX") (class "Default")
      (node (ref "R65") (pin "2") (pinfunction "2_2") (pintype "passive"))
      (node (ref "U1") (pin "89") (pinfunction "PB3(JTDO/TRACESWO)_89") (pintype "bidirectional"))
    )
    (net (code "23") (name "/E1-~{SLP}") (class "Default")
      (node (ref "E1") (pin "6") (pinfunction "~{SLEEP}_6") (pintype "passive"))
      (node (ref "E1_RST") (pin "1") (pinfunction "1_1") (pintype "passive"))
    )
    (net (code "24") (name "/E2-CS{slash}RX") (class "Default")
      (node (ref "E2_MS3") (pin "3") (pinfunction "3_3") (pintype "passive"))
      (node (ref "R66") (pin "1") (pinfunction "1_1") (pintype "passive"))
      (node (ref "U1") (pin "82") (pinfunction "PD1_82") (pintype "bidirectional"))
    )
    (net (code "25") (name "/E2-DIR") (class "Default")
      (node (ref "E2") (pin "8") (pinfunction "DIR_8") (pintype "passive"))
      (node (ref "U1") (pin "84") (pinfunction "PD3_84") (pintype "bidirectional"))
    )
    (net (code "26") (name "/E2-EN") (class "Default")
      (node (ref "E2") (pin "1") (pinfunction "~{ENA}_1") (pintype "passive"))
      (node (ref "R45") (pin "2") (pinfunction "2_2") (pintype "passive"))
      (node (ref "U1") (pin "81") (pinfunction "PD0_81") (pintype "bidirectional"))
    )
    (net (code "27") (name "/E2-STEP") (class "Default")
      (node (ref "E2") (pin "7") (pinfunction "STEP_7") (pintype "passive"))
      (node (ref "U1") (pin "83") (pinfunction "PD2_83") (pintype "bidirectional"))
    )
    (net (code "28") (name "/E2-TX") (class "Default")
      (node (ref "R66") (pin "2") (pinfunction "2_2") (pintype "passive"))
      (node (ref "U1") (pin "90") (pinfunction "PB4(NJTRST)_90") (pintype "bidirectional"))
    )
    (net (code "29") (name "/E2-~{SLP}") (class "Default")
      (node (ref "E2") (pin "6") (pinfunction "~{SLEEP}_6") (pintype "passive"))
      (node (ref "E2_RST") (pin "1") (pinfunction "1_1") (pintype "passive"))
    )
    (net (code "30") (name "/FAN_0") (class "Default")
      (node (ref "R46") (pin "1") (pinfunction "1_1") (pintype "passive"))
      (node (ref "R47") (pin "1") (pinfunction "1_1") (pintype "passive"))
      (node (ref "R55") (pin "2") (pinfunction "2_2") (pintype "passive"))
      (node (ref "U1") (pin "67") (pinfunction "PA8_67") (pintype "bidirectional"))
    )
    (net (code "31") (name "/FAN_1") (class "Default")
      (node (ref "R51") (pin "1") (pinfunction "1_1") (pintype "passive"))
      (node (ref "R52") (pin "1") (pinfunction "1_1") (pintype "passive"))
      (node (ref "R53") (pin "2") (pinfunction "2_2") (pintype "passive"))
      (node (ref "U1") (pin "66") (pinfunction "PC9_66") (pintype "bidirectional"))
    )
    (net (code "32") (name "/HB") (class "Default")
      (node (ref "R31") (pin "1") (pinfunction "1_1") (pintype "passive"))
      (node (ref "R32") (pin "1") (pinfunction "1_1") (pintype "passive"))
      (node (ref "R33") (pin "2") (pinfunction "2_2") (pintype "passive"))
      (node (ref "U1") (pin "24") (pinfunction "PA1_24") (pintype "bidirectional"))
    )
    (net (code "33") (name "/HE_0") (class "Default")
      (node (ref "R34") (pin "1") (pinfunction "1_1") (pintype "passive"))
      (node (ref "R35") (pin "1") (pinfunction "1_1") (pintype "passive"))
      (node (ref "R36") (pin "2") (pinfunction "2_2") (pintype "passive"))
      (node (ref "U1") (pin "63") (pinfunction "PC6_63") (pintype "bidirectional"))
    )
    (net (code "34") (name "/HE_1") (class "Default")
      (node (ref "R37") (pin "1") (pinfunction "1_1") (pintype "passive"))
      (node (ref "R38") (pin "1") (pinfunction "1_1") (pintype "passive"))
      (node (ref "R39") (pin "2") (pinfunction "2_2") (pintype "passive"))
      (node (ref "U1") (pin "64") (pinfunction "PC7_64") (pintype "bidirectional"))
    )
    (net (code "35") (name "/HE_2") (class "Default")
      (node (ref "R48") (pin "1") (pinfunction "1_1") (pintype "passive"))
      (node (ref "R49") (pin "1") (pinfunction "1_1") (pintype "passive"))
      (node (ref "R50") (pin "2") (pinfunction "2_2") (pintype "passive"))
      (node (ref "U1") (pin "65") (pinfunction "PC8_65") (pintype "bidirectional"))
    )
    (net (code "36") (name "/KILL") (class "Default")
      (node (ref "EXP2") (pin "10") (pinfunction "10_10") (pintype "passive"))
      (node (ref "U1") (pin "34") (pinfunction "PC5_34") (pintype "bidirectional"))
    )
    (net (code "37") (name "/LCD_D4") (class "Default")
      (node (ref "EXP1") (pin "5") (pinfunction "5_5") (pintype "passive"))
      (node (ref "U1") (pin "43") (pinfunction "PE12_43") (pintype "bidirectional"))
    )
    (net (code "38") (name "/LCD_D5") (class "Default")
      (node (ref "EXP1") (pin "6") (pinfunction "6_6") (pintype "passive"))
      (node (ref "U1") (pin "44") (pinfunction "PE13_44") (pintype "bidirectional"))
    )
    (net (code "39") (name "/LCD_D6") (class "Default")
      (node (ref "EXP1") (pin "7") (pinfunction "7_7") (pintype "passive"))
      (node (ref "U1") (pin "45") (pinfunction "PE14_45") (pintype "bidirectional"))
    )
    (net (code "40") (name "/LCD_D7") (class "Default")
      (node (ref "EXP1") (pin "8") (pinfunction "8_8") (pintype "passive"))
      (node (ref "U1") (pin "46") (pinfunction "PE15_46") (pintype "bidirectional"))
    )
    (net (code "41") (name "/LCD_ENA") (class "Default")
      (node (ref "EXP1") (pin "3") (pinfunction "3_3") (pintype "passive"))
      (node (ref "U1") (pin "40") (pinfunction "PE9_40") (pintype "bidirectional"))
    )
    (net (code "42") (name "/LCD_RS") (class "Default")
      (node (ref "EXP1") (pin "4") (pinfunction "4_4") (pintype "passive"))
      (node (ref "U1") (pin "41") (pinfunction "PE10_41") (pintype "bidirectional"))
    )
    (net (code "43") (name "/LED") (class "Default")
      (node (ref "R13") (pin "2") (pinfunction "2_2") (pintype "passive"))
      (node (ref "U1") (pin "53") (pinfunction "PB14_53") (pintype "bidirectional"))
    )
    (net (code "44") (name "/PA3") (class "Default")
      (node (ref "EXP3") (pin "8") (pinfunction "8_8") (pintype "passive"))
      (node (ref "U1") (pin "26") (pinfunction "PA3_26") (pintype "bidirectional"))
    )
    (net (code "45") (name "/PA4") (class "Default")
      (node (ref "EXP3") (pin "7") (pinfunction "7_7") (pintype "passive"))
      (node (ref "U1") (pin "29") (pinfunction "PA4_29") (pintype "bidirectional"))
    )
    (net (code "46") (name "/PA9") (class "Default")
      (node (ref "EXP3") (pin "11") (pinfunction "11_11") (pintype "passive"))
      (node (ref "U1") (pin "68") (pinfunction "PA9_68") (pintype "bidirectional"))
    )
    (net (code "47") (name "/PA10") (class "Default")
      (node (ref "EXP3") (pin "12") (pinfunction "12_12") (pintype "passive"))
      (node (ref "U1") (pin "69") (pinfunction "PA10_69") (pintype "bidirectional"))
    )
    (net (code "48") (name "/PD12") (class "Default")
      (node (ref "EXP3") (pin "14") (pinfunction "14_14") (pintype "passive"))
      (node (ref "U1") (pin "59") (pinfunction "PD12_59") (pintype "bidirectional"))
    )
    (net (code "49") (name "/PD13") (class "Default")
      (node (ref "EXP3") (pin "13") (pinfunction "13_13") (pintype "passive"))
      (node (ref "U1") (pin "60") (pinfunction "PD13_60") (pintype "bidirectional"))
    )
    (net (code "50") (name "/PD14") (class "Default")
      (node (ref "EXP3") (pin "5") (pinfunction "5_5") (pintype "passive"))
      (node (ref "U1") (pin "61") (pinfunction "PD14_61") (pintype "bidirectional"))
    )
    (net (code "51") (name "/PD15") (class "Default")
      (node (ref "EXP3") (pin "6") (pinfunction "6_6") (pintype "passive"))
      (node (ref "U1") (pin "62") (pinfunction "PD15_62") (pintype "bidirectional"))
    )
    (net (code "52") (name "/PS_ON") (class "Default")
      (node (ref "PS_ON") (pin "1") (pinfunction "1_1") (pintype "passive"))
      (node (ref "U1") (pin "42") (pinfunction "PE11_42") (pintype "bidirectional"))
    )
    (net (code "53") (name "/RESET") (class "Default")
      (node (ref "C8") (pin "2") (pinfunction "2_2") (pintype "passive"))
      (node (ref "EXP2") (pin "8") (pinfunction "8_8") (pintype "passive"))
      (node (ref "R11") (pin "1") (pinfunction "1_1") (pintype "passive"))
      (node (ref "S1") (pin "1") (pintype "passive"))
      (node (ref "SWD") (pin "5") (pinfunction "5_5") (pintype "passive"))
      (node (ref "U1") (pin "14") (pinfunction "NRST_14") (pintype "bidirectional"))
    )
    (net (code "54") (name "/SCL") (class "Default")
      (node (ref "EXP3") (pin "9") (pinfunction "9_9") (pintype "passive"))
      (node (ref "I2C_1") (pin "1") (pinfunction "1_1") (pintype "passive"))
      (node (ref "I2C_2") (pin "1") (pinfunction "1_1") (pintype "passive"))
      (node (ref "R1") (pin "2") (pinfunction "2_2") (pintype "passive"))
      (node (ref "R2") (pin "1") (pinfunction "1_1") (pintype "passive"))
      (node (ref "U7") (pin "1") (pinfunction "SCL_1") (pintype "passive"))
    )
    (net (code "55") (name "/SDA") (class "Default")
      (node (ref "EXP3") (pin "10") (pinfunction "10_10") (pintype "passive"))
      (node (ref "I2C_1") (pin "2") (pinfunction "2_2") (pintype "passive"))
      (node (ref "I2C_2") (pin "2") (pinfunction "2_2") (pintype "passive"))
      (node (ref "R3") (pin "1") (pinfunction "1_1") (pintype "passive"))
      (node (ref "R9") (pin "2") (pinfunction "2_2") (pintype "passive"))
      (node (ref "U7") (pin "3") (pinfunction "SDA_3") (pintype "passive"))
    )
    (net (code "56") (name "/SD_CSEL") (class "Default")
      (node (ref "EXP2") (pin "4") (pinfunction "4_4") (pintype "passive"))
      (node (ref "U1") (pin "25") (pinfunction "PA2_25") (pintype "bidirectional"))
    )
    (net (code "57") (name "/SD_DET") (class "Default")
      (node (ref "EXP2") (pin "7") (pinfunction "7_7") (pintype "passive"))
      (node (ref "U1") (pin "35") (pinfunction "PB0_35") (pintype "bidirectional"))
    )
    (net (code "58") (name "/SERVO") (class "Default")
      (node (ref "SERVO") (pin "3") (pinfunction "3_3") (pintype "passive"))
      (node (ref "U1") (pin "77") (pinfunction "PA15(JTDI)_77") (pintype "bidirectional"))
    )
    (net (code "59") (name "/SPI1_MISO") (class "Default")
      (node (ref "E0_RST") (pin "3") (pinfunction "3_3") (pintype "passive"))
      (node (ref "E1_RST") (pin "3") (pinfunction "3_3") (pintype "passive"))
      (node (ref "E2_RST") (pin "3") (pinfunction "3_3") (pintype "passive"))
      (node (ref "EXP2") (pin "1") (pinfunction "1_1") (pintype "passive"))
      (node (ref "U1") (pin "31") (pinfunction "PA6_31") (pintype "bidirectional"))
      (node (ref "X_RST") (pin "3") (pinfunction "3_3") (pintype "passive"))
      (node (ref "Y_RST") (pin "3") (pinfunction "3_3") (pintype "passive"))
      (node (ref "Z_RST") (pin "3") (pinfunction "3_3") (pintype "passive"))
    )
    (net (code "60") (name "/SPI1_MOSI") (class "Default")
      (node (ref "E0_MS1") (pin "3") (pinfunction "3_3") (pintype "passive"))
      (node (ref "E1_MS1") (pin "3") (pinfunction "3_3") (pintype "passive"))
      (node (ref "E2_MS1") (pin "3") (pinfunction "3_3") (pintype "passive"))
      (node (ref "EXP2") (pin "6") (pinfunction "6_6") (pintype "passive"))
      (node (ref "U1") (pin "32") (pinfunction "PA7_32") (pintype "bidirectional"))
      (node (ref "X_MS1") (pin "3") (pinfunction "3_3") (pintype "passive"))
      (node (ref "Y_MS1") (pin "3") (pinfunction "3_3") (pintype "passive"))
      (node (ref "Z_MS1") (pin "3") (pinfunction "3_3") (pintype "passive"))
    )
    (net (code "61") (name "/SPI1_SCK") (class "Default")
      (node (ref "E0_MS2") (pin "3") (pinfunction "3_3") (pintype "passive"))
      (node (ref "E1_MS2") (pin "3") (pinfunction "3_3") (pintype "passive"))
      (node (ref "E2_MS2") (pin "3") (pinfunction "3_3") (pintype "passive"))
      (node (ref "EXP2") (pin "2") (pinfunction "2_2") (pintype "passive"))
      (node (ref "U1") (pin "30") (pinfunction "PA5_30") (pintype "bidirectional"))
      (node (ref "X_MS2") (pin "3") (pinfunction "3_3") (pintype "passive"))
      (node (ref "Y_MS2") (pin "3") (pinfunction "3_3") (pintype "passive"))
      (node (ref "Z_MS2") (pin "3") (pinfunction "3_3") (pintype "passive"))
    )
    (net (code "62") (name "/SWCLK") (class "Default")
      (node (ref "R5") (pin "2") (pinfunction "2_2") (pintype "passive"))
      (node (ref "SWD") (pin "3") (pinfunction "3_3") (pintype "passive"))
      (node (ref "U1") (pin "76") (pinfunction "PA14(JTCK-SWCLK)_76") (pintype "bidirectional"))
    )
    (net (code "63") (name "/SWDIO") (class "Default")
      (node (ref "R6") (pin "2") (pinfunction "2_2") (pintype "passive"))
      (node (ref "SWD") (pin "1") (pinfunction "1_1") (pintype "passive"))
      (node (ref "U1") (pin "72") (pinfunction "PA13(JTMS-SWDIO)_72") (pintype "bidirectional"))
    )
    (net (code "64") (name "/THERM0") (class "Default")
      (node (ref "R43") (pin "2") (pinfunction "2_2") (pintype "passive"))
      (node (ref "R82") (pin "1") (pinfunction "1_1") (pintype "passive"))
      (node (ref "Thermistors") (pin "2") (pinfunction "2_2") (pintype "passive"))
    )
    (net (code "65") (name "/THERM0_ADC") (class "Default")
      (node (ref "C29") (pin "2") (pinfunction "2_2") (pintype "passive"))
      (node (ref "R82") (pin "2") (pinfunction "2_2") (pintype "passive"))
      (node (ref "U1") (pin "33") (pinfunction "PC4_33") (pintype "bidirectional"))
    )
    (net (code "66") (name "/THERM1") (class "Default")
      (node (ref "R42") (pin "2") (pinfunction "2_2") (pintype "passive"))
      (node (ref "R84") (pin "1") (pinfunction "1_1") (pintype "passive"))
      (node (ref "Thermistors") (pin "4") (pinfunction "4_4") (pintype "passive"))
    )
    (net (code "67") (name "/THERM1_ADC") (class "Default")
      (node (ref "C28") (pin "2") (pinfunction "2_2") (pintype "passive"))
      (node (ref "R84") (pin "2") (pinfunction "2_2") (pintype "passive"))
      (node (ref "U1") (pin "18") (pinfunction "PC3_18") (pintype "bidirectional"))
    )
    (net (code "68") (name "/THERM2") (class "Default")
      (node (ref "R41") (pin "2") (pinfunction "2_2") (pintype "passive"))
      (node (ref "R81") (pin "1") (pinfunction "1_1") (pintype "passive"))
      (node (ref "Thermistors") (pin "6") (pinfunction "6_6") (pintype "passive"))
    )
    (net (code "69") (name "/THERM2_ADC") (class "Default")
      (node (ref "C27") (pin "2") (pinfunction "2_2") (pintype "passive"))
      (node (ref "R81") (pin "2") (pinfunction "2_2") (pintype "passive"))
      (node (ref "U1") (pin "17") (pinfunction "PC2_17") (pintype "bidirectional"))
    )
    (net (code "70") (name "/THERM3") (class "Default")
      (node (ref "R40") (pin "2") (pinfunction "2_2") (pintype "passive"))
      (node (ref "R83") (pin "1") (pinfunction "1_1") (pintype "passive"))
      (node (ref "Thermistors") (pin "8") (pinfunction "8_8") (pintype "passive"))
    )
    (net (code "71") (name "/THERM3_ADC") (class "Default")
      (node (ref "C26") (pin "2") (pinfunction "2_2") (pintype "passive"))
      (node (ref "R83") (pin "2") (pinfunction "2_2") (pintype "passive"))
      (node (ref "U1") (pin "16") (pinfunction "PC1_16") (pintype "bidirectional"))
    )
    (net (code "72") (name "/THERM4") (class "Default")
      (node (ref "R54") (pin "2") (pinfunction "2_2") (pintype "passive"))
      (node (ref "R85") (pin "1") (pinfunction "1_1") (pintype "passive"))
      (node (ref "Thermistors") (pin "10") (pinfunction "10_10") (pintype "passive"))
    )
    (net (code "73") (name "/THERM4_ADC") (class "Default")
      (node (ref "C9") (pin "2") (pinfunction "2_2") (pintype "passive"))
      (node (ref "R85") (pin "2") (pinfunction "2_2") (pintype "passive"))
      (node (ref "U1") (pin "15") (pinfunction "PC0_15") (pintype "bidirectional"))
    )
    (net (code "74") (name "/USB_D_N") (class "Default")
      (node (ref "R7") (pin "1") (pinfunction "1_1") (pintype "passive"))
      (node (ref "U1") (pin "70") (pinfunction "PA11_70") (pintype "bidirectional"))
    )
    (net (code "75") (name "/USB_D_P") (class "Default")
      (node (ref "R8") (pin "1") (pinfunction "1_1") (pintype "passive"))
      (node (ref "U1") (pin "71") (pinfunction "PA12_71") (pintype "bidirectional"))
    )
    (net (code "76") (name "/USB_N") (class "Default")
      (node (ref "J2") (pin "D-") (pinfunction "D-_D-") (pintype "passive"))
      (node (ref "R7") (pin "2") (pinfunction "2_2") (pintype "passive"))
      (node (ref "U5") (pin "1") (pinfunction "IO1_1") (pintype "passive"))
      (node (ref "USB_AUX") (pin "4") (pinfunction "4_4") (pintype "passive"))
    )
    (net (code "77") (name "/USB_P") (class "Default")
      (node (ref "J2") (pin "D+") (pinfunction "D+_D+") (pintype "passive"))
      (node (ref "R8") (pin "2") (pinfunction "2_2") (pintype "passive"))
      (node (ref "U5") (pin "3") (pinfunction "IO2_3") (pintype "passive"))
      (node (ref "USB_AUX") (pin "3") (pinfunction "3_3") (pintype "passive"))
    )
    (net (code "78") (name "/X-CS{slash}RX") (class "Default")
      (node (ref "R5") (pin "1") (pinfunction "1_1") (pintype "passive"))
      (node (ref "U1") (pin "8") (pinfunction "PC14-OSC32_IN(PC14)_8") (pintype "bidirectional"))
      (node (ref "X_MS3") (pin "3") (pinfunction "3_3") (pintype "passive"))
    )
    (net (code "79") (name "/X-DIR") (class "Default")
      (node (ref "U1") (pin "9") (pinfunction "PC15-OSC32_OUT(PC15)_9") (pintype "bidirectional"))
      (node (ref "X") (pin "8") (pinfunction "DIR_8") (pintype "passive"))
    )
    (net (code "80") (name "/X-EN") (class "Default")
      (node (ref "R21") (pin "2") (pinfunction "2_2") (pintype "passive"))
      (node (ref "U1") (pin "79") (pinfunction "PC11_79") (pintype "bidirectional"))
      (node (ref "X") (pin "1") (pinfunction "~{ENA}_1") (pintype "passive"))
    )
    (net (code "81") (name "/X-MAX") (class "Default")
      (node (ref "C2") (pin "2") (pinfunction "2_2") (pintype "passive"))
      (node (ref "R62") (pin "2") (pinfunction "2_2") (pintype "passive"))
      (node (ref "R63") (pin "2") (pinfunction "2_2") (pintype "passive"))
      (node (ref "U1") (pin "52") (pinfunction "PB13_52") (pintype "bidirectional"))
    )
    (net (code "82") (name "/X-MIN") (class "Default")
      (node (ref "C1") (pin "2") (pinfunction "2_2") (pintype "passive"))
      (node (ref "R18") (pin "2") (pinfunction "2_2") (pintype "passive"))
      (node (ref "R60") (pin "2") (pinfunction "2_2") (pintype "passive"))
      (node (ref "U1") (pin "51") (pinfunction "PB12_51") (pintype "bidirectional"))
    )
    (net (code "83") (name "/X-STEP") (class "Default")
      (node (ref "U1") (pin "23") (pinfunction "PA0-WKUP(PA0)_23") (pintype "bidirectional"))
      (node (ref "X") (pin "7") (pinfunction "STEP_7") (pintype "passive"))
    )
    (net (code "84") (name "/X-~{SLP}") (class "Default")
      (node (ref "X") (pin "6") (pinfunction "~{SLEEP}_6") (pintype "passive"))
      (node (ref "X_RST") (pin "1") (pinfunction "1_1") (pintype "passive"))
    )
    (net (code "85") (name "/Y-CS{slash}RX") (class "Default")
      (node (ref "R6") (pin "1") (pinfunction "1_1") (pintype "passive"))
      (node (ref "U1") (pin "3") (pinfunction "PE4_3") (pintype "bidirectional"))
      (node (ref "Y_MS3") (pin "3") (pinfunction "3_3") (pintype "passive"))
    )
    (net (code "86") (name "/Y-DIR") (class "Default")
      (node (ref "U1") (pin "5") (pinfunction "PE6_5") (pintype "bidirectional"))
      (node (ref "Y") (pin "8") (pinfunction "DIR_8") (pintype "passive"))
    )
    (net (code "87") (name "/Y-EN") (class "Default")
      (node (ref "R23") (pin "2") (pinfunction "2_2") (pintype "passive"))
      (node (ref "U1") (pin "2") (pinfunction "PE3_2") (pintype "bidirectional"))
      (node (ref "Y") (pin "1") (pinfunction "~{ENA}_1") (pintype "passive"))
    )
    (net (code "88") (name "/Y-MAX") (class "Default")
      (node (ref "C36") (pin "2") (pinfunction "2_2") (pintype "passive"))
      (node (ref "R71") (pin "2") (pinfunction "2_2") (pintype "passive"))
      (node (ref "R72") (pin "2") (pinfunction "2_2") (pintype "passive"))
      (node (ref "U1") (pin "55") (pinfunction "PD8_55") (pintype "bidirectional"))
    )
    (net (code "89") (name "/Y-MIN") (class "Default")
      (node (ref "C31") (pin "2") (pinfunction "2_2") (pintype "passive"))
      (node (ref "R68") (pin "2") (pinfunction "2_2") (pintype "passive"))
      (node (ref "R69") (pin "2") (pinfunction "2_2") (pintype "passive"))
      (node (ref "U1") (pin "54") (pinfunction "PB15_54") (pintype "bidirectional"))
    )
    (net (code "90") (name "/Y-STEP") (class "Default")
      (node (ref "U1") (pin "4") (pinfunction "PE5_4") (pintype "bidirectional"))
      (node (ref "Y") (pin "7") (pinfunction "STEP_7") (pintype "passive"))
    )
    (net (code "91") (name "/Y-~{SLP}") (class "Default")
      (node (ref "Y") (pin "6") (pinfunction "~{SLEEP}_6") (pintype "passive"))
      (node (ref "Y_RST") (pin "1") (pinfunction "1_1") (pintype "passive"))
    )
    (net (code "92") (name "/Z-CS{slash}RX") (class "Default")
      (node (ref "R16") (pin "1") (pinfunction "1_1") (pintype "passive"))
      (node (ref "U1") (pin "97") (pinfunction "PE0_97") (pintype "bidirectional"))
      (node (ref "Z_MS3") (pin "3") (pinfunction "3_3") (pintype "passive"))
    )
    (net (code "93") (name "/Z-DIR") (class "Default")
      (node (ref "U1") (pin "1") (pinfunction "PE2_1") (pintype "bidirectional"))
      (node (ref "Z") (pin "8") (pinfunction "DIR_8") (pintype "passive"))
    )
    (net (code "94") (name "/Z-EN") (class "Default")
      (node (ref "R25") (pin "2") (pinfunction "2_2") (pintype "passive"))
      (node (ref "U1") (pin "93") (pinfunction "PB7_93") (pintype "bidirectional"))
      (node (ref "Z") (pin "1") (pinfunction "~{ENA}_1") (pintype "passive"))
    )
    (net (code "95") (name "/Z-MAX") (class "Default")
      (node (ref "C42") (pin "2") (pinfunction "2_2") (pintype "passive"))
      (node (ref "R77") (pin "2") (pinfunction "2_2") (pintype "passive"))
      (node (ref "R78") (pin "2") (pinfunction "2_2") (pintype "passive"))
      (node (ref "U1") (pin "57") (pinfunction "PD10_57") (pintype "bidirectional"))
    )
    (net (code "96") (name "/Z-MIN") (class "Default")
      (node (ref "C41") (pin "2") (pinfunction "2_2") (pintype "passive"))
      (node (ref "R74") (pin "2") (pinfunction "2_2") (pintype "passive"))
      (node (ref "R75") (pin "2") (pinfunction "2_2") (pintype "passive"))
      (node (ref "U1") (pin "56") (pinfunction "PD9_56") (pintype "bidirectional"))
    )
    (net (code "97") (name "/Z-STEP") (class "Default")
      (node (ref "U1") (pin "98") (pinfunction "PE1_98") (pintype "bidirectional"))
      (node (ref "Z") (pin "7") (pinfunction "STEP_7") (pintype "passive"))
    )
    (net (code "98") (name "/Z-TX") (class "Default")
      (node (ref "R16") (pin "2") (pinfunction "2_2") (pintype "passive"))
      (node (ref "U1") (pin "47") (pinfunction "PB10_47") (pintype "bidirectional"))
    )
    (net (code "99") (name "/Z-~{SLP}") (class "Default")
      (node (ref "Z") (pin "6") (pinfunction "~{SLEEP}_6") (pintype "passive"))
      (node (ref "Z_RST") (pin "1") (pinfunction "1_1") (pintype "passive"))
    )
    (net (code "100") (name "5V_DCDC") (class "Default")
      (node (ref "5VDC") (pin "1") (pinfunction "1_1") (pintype "passive"))
      (node (ref "C43") (pin "2") (pinfunction "2_2") (pintype "passive"))
      (node (ref "C44") (pin "2") (pinfunction "2_2") (pintype "passive"))
      (node (ref "D15") (pin "A") (pinfunction "A_A") (pintype "passive"))
      (node (ref "L1") (pin "2") (pinfunction "2_2") (pintype "passive"))
      (node (ref "LD8") (pin "1") (pinfunction "A_1") (pintype "passive"))
      (node (ref "R79") (pin "2") (pinfunction "2_2") (pintype "passive"))
      (node (ref "U3") (pin "1") (pinfunction "FB_1") (pintype "passive"))
    )
    (net (code "101") (name "GND") (class "Default")
      (node (ref "12V") (pin "2") (pinfunction "2_2") (pintype "passive"))
      (node (ref "3V3") (pin "2") (pinfunction "2_2") (pintype "passive"))
      (node (ref "5V") (pin "2") (pinfunction "2_2") (pintype "passive"))
      (node (ref "5VDC") (pin "2") (pinfunction "2_2") (pintype "passive"))
      (node (ref "C1") (pin "1") (pinfunction "1_1") (pintype "passive"))
      (node (ref "C10") (pin "2") (pinfunction "2_2") (pintype "passive"))
      (node (ref "C11") (pin "1") (pinfunction "1_1") (pintype "passive"))
      (node (ref "C12") (pin "1") (pinfunction "1_1") (pintype "passive"))
      (node (ref "C13") (pin "1") (pinfunction "1_1") (pintype "passive"))
      (node (ref "C14") (pin "1") (pinfunction "1_1") (pintype "passive"))
      (node (ref "C15") (pin "1") (pinfunction "1_1") (pintype "passive"))
      (node (ref "C16") (pin "1") (pinfunction "1_1") (pintype "passive"))
      (node (ref "C17") (pin "1") (pinfunction "1_1") (pintype "passive"))
      (node (ref "C19") (pin "1") (pinfunction "1_1") (pintype "passive"))
      (node (ref "C2") (pin "1") (pinfunction "1_1") (pintype "passive"))
      (node (ref "C20") (pin "1") (pinfunction "1_1") (pintype "passive"))
      (node (ref "C21") (pin "2") (pinfunction "2_2") (pintype "passive"))
      (node (ref "C22") (pin "2") (pinfunction "2_2") (pintype "passive"))
      (node (ref "C23") (pin "2") (pinfunction "2_2") (pintype "passive"))
      (node (ref "C24") (pin "2") (pinfunction "2_2") (pintype "passive"))
      (node (ref "C25") (pin "2") (pinfunction "2_2") (pintype "passive"))
      (node (ref "C26") (pin "1") (pinfunction "1_1") (pintype "passive"))
      (node (ref "C27") (pin "1") (pinfunction "1_1") (pintype "passive"))
      (node (ref "C28") (pin "1") (pinfunction "1_1") (pintype "passive"))
      (node (ref "C29") (pin "1") (pinfunction "1_1") (pintype "passive"))
      (node (ref "C30") (pin "2") (pinfunction "2_2") (pintype "passive"))
      (node (ref "C31") (pin "1") (pinfunction "1_1") (pintype "passive"))
      (node (ref "C32") (pin "2") (pinfunction "2_2") (pintype "passive"))
      (node (ref "C34") (pin "1") (pinfunction "1_1") (pintype "passive"))
      (node (ref "C35") (pin "1") (pinfunction "1_1") (pintype "passive"))
      (node (ref "C36") (pin "1") (pinfunction "1_1") (pintype "passive"))
      (node (ref "C37") (pin "1") (pinfunction "1_1") (pintype "passive"))
      (node (ref "C38") (pin "1") (pinfunction "1_1") (pintype "passive"))
      (node (ref "C39") (pin "1") (pinfunction "1_1") (pintype "passive"))
      (node (ref "C4") (pin "1") (pinfunction "1_1") (pintype "passive"))
      (node (ref "C40") (pin "1") (pinfunction "1_1") (pintype "passive"))
      (node (ref "C41") (pin "1") (pinfunction "1_1") (pintype "passive"))
      (node (ref "C42") (pin "1") (pinfunction "1_1") (pintype "passive"))
      (node (ref "C43") (pin "1") (pinfunction "1_1") (pintype "passive"))
      (node (ref "C44") (pin "1") (pinfunction "1_1") (pintype "passive"))
      (node (ref "C45") (pin "1") (pinfunction "1_1") (pintype "passive"))
      (node (ref "C5") (pin "1") (pinfunction "1_1") (pintype "passive"))
      (node (ref "C6") (pin "1") (pinfunction "1_1") (pintype "passive"))
      (node (ref "C7") (pin "1") (pinfunction "1_1") (pintype "passive"))
      (node (ref "C8") (pin "1") (pinfunction "1_1") (pintype "passive"))
      (node (ref "C9") (pin "1") (pinfunction "1_1") (pintype "passive"))
      (node (ref "D6") (pin "A") (pinfunction "A_A") (pintype "passive"))
      (node (ref "D7") (pin "A") (pinfunction "A_A") (pintype "passive"))
      (node (ref "D8") (pin "A") (pinfunction "A_A") (pintype "passive"))
      (node (ref "E0") (pin "15") (pinfunction "GND_15") (pintype "passive"))
      (node (ref "E0") (pin "9") (pinfunction "GND_9") (pintype "passive"))
      (node (ref "E1") (pin "15") (pinfunction "GND_15") (pintype "passive"))
      (node (ref "E1") (pin "9") (pinfunction "GND_9") (pintype "passive"))
      (node (ref "E2") (pin "15") (pinfunction "GND_15") (pintype "passive"))
      (node (ref "E2") (pin "9") (pinfunction "GND_9") (pintype "passive"))
      (node (ref "EXP1") (pin "9") (pinfunction "9_9") (pintype "passive"))
      (node (ref "EXP2") (pin "9") (pinfunction "9_9") (pintype "passive"))
      (node (ref "EXP3") (pin "3") (pinfunction "3_3") (pintype "passive"))
      (node (ref "EXP3") (pin "4") (pinfunction "4_4") (pintype "passive"))
      (node (ref "FB2") (pin "2") (pinfunction "2_2") (pintype "passive"))
      (node (ref "HB-PWR") (pin "1") (pinfunction "4_1") (pintype "power_in"))
      (node (ref "I2C_1") (pin "3") (pinfunction "3_3") (pintype "passive"))
      (node (ref "I2C_2") (pin "3") (pinfunction "3_3") (pintype "passive"))
      (node (ref "J2") (pin "GND") (pinfunction "GND_GND") (pintype "passive"))
      (node (ref "LD1") (pin "2") (pinfunction "K_2") (pintype "passive"))
      (node (ref "LD2") (pin "2") (pinfunction "K_2") (pintype "passive"))
      (node (ref "LD3") (pin "2") (pinfunction "K_2") (pintype "passive"))
      (node (ref "LD4") (pin "2") (pinfunction "K_2") (pintype "passive"))
      (node (ref "LD5") (pin "2") (pinfunction "K_2") (pintype "passive"))
      (node (ref "LD6") (pin "2") (pinfunction "K_2") (pintype "passive"))
      (node (ref "LD7") (pin "2") (pinfunction "K_2") (pintype "passive"))
      (node (ref "LED1") (pin "2") (pinfunction "K_2") (pintype "passive"))
      (node (ref "MAIN-PWR") (pin "1") (pinfunction "4_1") (pintype "power_in"))
      (node (ref "PS_ON") (pin "2") (pinfunction "2_2") (pintype "passive"))
      (node (ref "PWR") (pin "2") (pinfunction "2_2") (pintype "passive"))
      (node (ref "Q1") (pin "3") (pinfunction "S_3") (pintype "passive"))
      (node (ref "Q2") (pin "3") (pinfunction "S_3") (pintype "passive"))
      (node (ref "Q3") (pin "3") (pinfunction "S_3") (pintype "passive"))
      (node (ref "Q4") (pin "3") (pinfunction "S_3") (pintype "passive"))
      (node (ref "Q5") (pin "3") (pinfunction "S_3") (pintype "passive"))
      (node (ref "Q6") (pin "3") (pinfunction "S_3") (pintype "passive"))
      (node (ref "R10") (pin "1") (pinfunction "1_1") (pintype "passive"))
      (node (ref "R12") (pin "1") (pinfunction "1_1") (pintype "passive"))
      (node (ref "R14") (pin "1") (pinfunction "1_1") (pintype "passive"))
      (node (ref "R15") (pin "1") (pinfunction "1_1") (pintype "passive"))
      (node (ref "R20") (pin "1") (pinfunction "1_1") (pintype "passive"))
      (node (ref "R22") (pin "2") (pinfunction "2_2") (pintype "passive"))
      (node (ref "R24") (pin "2") (pinfunction "2_2") (pintype "passive"))
      (node (ref "R26") (pin "2") (pinfunction "2_2") (pintype "passive"))
      (node (ref "R28") (pin "2") (pinfunction "2_2") (pintype "passive"))
      (node (ref "R30") (pin "2") (pinfunction "2_2") (pintype "passive"))
      (node (ref "R32") (pin "2") (pinfunction "2_2") (pintype "passive"))
      (node (ref "R35") (pin "2") (pinfunction "2_2") (pintype "passive"))
      (node (ref "R38") (pin "2") (pinfunction "2_2") (pintype "passive"))
      (node (ref "R44") (pin "2") (pinfunction "2_2") (pintype "passive"))
      (node (ref "R47") (pin "2") (pinfunction "2_2") (pintype "passive"))
      (node (ref "R49") (pin "2") (pinfunction "2_2") (pintype "passive"))
      (node (ref "R52") (pin "2") (pinfunction "2_2") (pintype "passive"))
      (node (ref "R57") (pin "1") (pinfunction "1_1") (pintype "passive"))
      (node (ref "R58") (pin "1") (pinfunction "1_1") (pintype "passive"))
      (node (ref "R59") (pin "1") (pinfunction "1_1") (pintype "passive"))
      (node (ref "S1") (pin "2") (pintype "passive"))
      (node (ref "SERVO") (pin "1") (pinfunction "1_1") (pintype "passive"))
      (node (ref "SWD") (pin "6") (pinfunction "6_6") (pintype "passive"))
      (node (ref "Thermistors") (pin "1") (pinfunction "1_1") (pintype "passive"))
      (node (ref "Thermistors") (pin "3") (pinfunction "3_3") (pintype "passive"))
      (node (ref "Thermistors") (pin "5") (pinfunction "5_5") (pintype "passive"))
      (node (ref "Thermistors") (pin "7") (pinfunction "7_7") (pintype "passive"))
      (node (ref "Thermistors") (pin "9") (pinfunction "9_9") (pintype "passive"))
      (node (ref "U1") (pin "10") (pinfunction "VSS_10") (pintype "power_in"))
      (node (ref "U1") (pin "20") (pinfunction "VSSA_20") (pintype "power_in"))
      (node (ref "U1") (pin "27") (pinfunction "VSS_27") (pintype "power_in"))
      (node (ref "U1") (pin "49") (pinfunction "VSS_49") (pintype "power_in"))
      (node (ref "U1") (pin "74") (pinfunction "VSS_74") (pintype "power_in"))
      (node (ref "U1") (pin "99") (pinfunction "VSS_99") (pintype "power_in"))
      (node (ref "U2") (pin "3") (pinfunction "GND_3") (pintype "passive"))
      (node (ref "U3") (pin "4") (pinfunction "GND_4") (pintype "passive"))
      (node (ref "U4") (pin "3") (pinfunction "GND_3") (pintype "passive"))
      (node (ref "U5") (pin "2") (pinfunction "GND_2") (pintype "passive"))
      (node (ref "U6") (pin "2") (pinfunction "GND_2") (pintype "passive"))
      (node (ref "U7") (pin "2") (pinfunction "GND_2") (pintype "passive"))
      (node (ref "U7") (pin "5") (pinfunction "WP_5") (pintype "passive"))
      (node (ref "USB_AUX") (pin "2") (pinfunction "2_2") (pintype "passive"))
      (node (ref "X") (pin "15") (pinfunction "GND_15") (pintype "passive"))
      (node (ref "X") (pin "9") (pinfunction "GND_9") (pintype "passive"))
      (node (ref "X+") (pin "2") (pinfunction "2_2") (pintype "passive"))
      (node (ref "X-") (pin "2") (pinfunction "2_2") (pintype "passive"))
      (node (ref "XT1") (pin "2") (pinfunction "GND_2") (pintype "passive"))
      (node (ref "Y") (pin "15") (pinfunction "GND_15") (pintype "passive"))
      (node (ref "Y") (pin "9") (pinfunction "GND_9") (pintype "passive"))
      (node (ref "Y+") (pin "2") (pinfunction "2_2") (pintype "passive"))
      (node (ref "Y-") (pin "2") (pinfunction "2_2") (pintype "passive"))
      (node (ref "Z") (pin "15") (pinfunction "GND_15") (pintype "passive"))
      (node (ref "Z") (pin "9") (pinfunction "GND_9") (pintype "passive"))
      (node (ref "Z+") (pin "2") (pinfunction "2_2") (pintype "passive"))
      (node (ref "Z-") (pin "2") (pinfunction "2_2") (pintype "passive"))
    )
    (net (code "102") (name "Net-(C10-Pad1)") (class "Default")
      (node (ref "C10") (pin "1") (pinfunction "1_1") (pintype "passive"))
      (node (ref "R19") (pin "1") (pinfunction "1_1") (pintype "passive"))
    )
    (net (code "103") (name "Net-(D4-PadA)") (class "Default")
      (node (ref "D4") (pin "A") (pinfunction "A_A") (pintype "passive"))
      (node (ref "F3") (pin "2") (pinfunction "2_2") (pintype "passive"))
    )
    (net (code "104") (name "Net-(E0-1A)") (class "Default")
      (node (ref "E0") (pin "12") (pinfunction "1A_12") (pintype "passive"))
      (node (ref "E0_MOT") (pin "2") (pinfunction "2_2") (pintype "passive"))
      (node (ref "E0_MOT_A") (pin "3") (pinfunction "3_3") (pintype "passive"))
    )
    (net (code "105") (name "Net-(E0-1B)") (class "Default")
      (node (ref "E0") (pin "11") (pinfunction "1B_11") (pintype "passive"))
      (node (ref "E0_MOT") (pin "1") (pinfunction "1_1") (pintype "passive"))
      (node (ref "E0_MOT_A") (pin "4") (pinfunction "4_4") (pintype "passive"))
    )
    (net (code "106") (name "Net-(E0-2A)") (class "Default")
      (node (ref "E0") (pin "13") (pinfunction "2A_13") (pintype "passive"))
      (node (ref "E0_MOT") (pin "3") (pinfunction "3_3") (pintype "passive"))
      (node (ref "E0_MOT_A") (pin "2") (pinfunction "2_2") (pintype "passive"))
    )
    (net (code "107") (name "Net-(E0-2B)") (class "Default")
      (node (ref "E0") (pin "14") (pinfunction "2B_14") (pintype "passive"))
      (node (ref "E0_MOT") (pin "4") (pinfunction "4_4") (pintype "passive"))
      (node (ref "E0_MOT_A") (pin "1") (pinfunction "1_1") (pintype "passive"))
    )
    (net (code "108") (name "Net-(E0-MS1{slash}SDI)") (class "Default")
      (node (ref "E0") (pin "2") (pinfunction "MS1/SDI_2") (pintype "passive"))
      (node (ref "E0_MS1") (pin "2") (pinfunction "2_2") (pintype "passive"))
      (node (ref "R28") (pin "1") (pinfunction "1_1") (pintype "passive"))
    )
    (net (code "109") (name "Net-(E0-MS2{slash}SCK)") (class "Default")
      (node (ref "E0") (pin "3") (pinfunction "MS2/SCK_3") (pintype "passive"))
      (node (ref "E0_MS2") (pin "2") (pinfunction "2_2") (pintype "passive"))
    )
    (net (code "110") (name "Net-(E0-MS3{slash}CS{slash}UART)") (class "Default")
      (node (ref "E0") (pin "4") (pinfunction "MS3/CS/UART_4") (pintype "passive"))
      (node (ref "E0_MS3") (pin "2") (pinfunction "2_2") (pintype "passive"))
    )
    (net (code "111") (name "Net-(E0-~{RST}{slash}SDO)") (class "Default")
      (node (ref "E0") (pin "5") (pinfunction "~{RST}/SDO_5") (pintype "passive"))
      (node (ref "E0_RST") (pin "2") (pinfunction "2_2") (pintype "passive"))
    )
    (net (code "112") (name "Net-(E0_DIAG-Pad1)") (class "Default")
      (node (ref "E0_DIAG") (pin "1") (pinfunction "1_1") (pintype "passive"))
      (node (ref "R62") (pin "1") (pinfunction "1_1") (pintype "passive"))
    )
    (net (code "113") (name "Net-(E1-1A)") (class "Default")
      (node (ref "E1") (pin "12") (pinfunction "1A_12") (pintype "passive"))
      (node (ref "E1_MOT") (pin "2") (pinfunction "2_2") (pintype "passive"))
      (node (ref "E1_MOT_A") (pin "3") (pinfunction "3_3") (pintype "passive"))
    )
    (net (code "114") (name "Net-(E1-1B)") (class "Default")
      (node (ref "E1") (pin "11") (pinfunction "1B_11") (pintype "passive"))
      (node (ref "E1_MOT") (pin "1") (pinfunction "1_1") (pintype "passive"))
      (node (ref "E1_MOT_A") (pin "4") (pinfunction "4_4") (pintype "passive"))
    )
    (net (code "115") (name "Net-(E1-2A)") (class "Default")
      (node (ref "E1") (pin "13") (pinfunction "2A_13") (pintype "passive"))
      (node (ref "E1_MOT") (pin "3") (pinfunction "3_3") (pintype "passive"))
      (node (ref "E1_MOT_A") (pin "2") (pinfunction "2_2") (pintype "passive"))
    )
    (net (code "116") (name "Net-(E1-2B)") (class "Default")
      (node (ref "E1") (pin "14") (pinfunction "2B_14") (pintype "passive"))
      (node (ref "E1_MOT") (pin "4") (pinfunction "4_4") (pintype "passive"))
      (node (ref "E1_MOT_A") (pin "1") (pinfunction "1_1") (pintype "passive"))
    )
    (net (code "117") (name "Net-(E1-MS1{slash}SDI)") (class "Default")
      (node (ref "E1") (pin "2") (pinfunction "MS1/SDI_2") (pintype "passive"))
      (node (ref "E1_MS1") (pin "2") (pinfunction "2_2") (pintype "passive"))
      (node (ref "R30") (pin "1") (pinfunction "1_1") (pintype "passive"))
    )
    (net (code "118") (name "Net-(E1-MS2{slash}SCK)") (class "Default")
      (node (ref "E1") (pin "3") (pinfunction "MS2/SCK_3") (pintype "passive"))
      (node (ref "E1_MS2") (pin "2") (pinfunction "2_2") (pintype "passive"))
    )
    (net (code "119") (name "Net-(E1-MS3{slash}CS{slash}UART)") (class "Default")
      (node (ref "E1") (pin "4") (pinfunction "MS3/CS/UART_4") (pintype "passive"))
      (node (ref "E1_MS3") (pin "2") (pinfunction "2_2") (pintype "passive"))
    )
    (net (code "120") (name "Net-(E1-~{RST}{slash}SDO)") (class "Default")
      (node (ref "E1") (pin "5") (pinfunction "~{RST}/SDO_5") (pintype "passive"))
      (node (ref "E1_RST") (pin "2") (pinfunction "2_2") (pintype "passive"))
    )
    (net (code "121") (name "Net-(E1_DIAG-Pad1)") (class "Default")
      (node (ref "E1_DIAG") (pin "1") (pinfunction "1_1") (pintype "passive"))
      (node (ref "R71") (pin "1") (pinfunction "1_1") (pintype "passive"))
    )
    (net (code "122") (name "Net-(E2-1A)") (class "Default")
      (node (ref "E2") (pin "12") (pinfunction "1A_12") (pintype "passive"))
      (node (ref "E2_MOT") (pin "2") (pinfunction "2_2") (pintype "passive"))
      (node (ref "E2_MOT_A") (pin "3") (pinfunction "3_3") (pintype "passive"))
    )
    (net (code "123") (name "Net-(E2-1B)") (class "Default")
      (node (ref "E2") (pin "11") (pinfunction "1B_11") (pintype "passive"))
      (node (ref "E2_MOT") (pin "1") (pinfunction "1_1") (pintype "passive"))
      (node (ref "E2_MOT_A") (pin "4") (pinfunction "4_4") (pintype "passive"))
    )
    (net (code "124") (name "Net-(E2-2A)") (class "Default")
      (node (ref "E2") (pin "13") (pinfunction "2A_13") (pintype "passive"))
      (node (ref "E2_MOT") (pin "3") (pinfunction "3_3") (pintype "passive"))
      (node (ref "E2_MOT_A") (pin "2") (pinfunction "2_2") (pintype "passive"))
    )
    (net (code "125") (name "Net-(E2-2B)") (class "Default")
      (node (ref "E2") (pin "14") (pinfunction "2B_14") (pintype "passive"))
      (node (ref "E2_MOT") (pin "4") (pinfunction "4_4") (pintype "passive"))
      (node (ref "E2_MOT_A") (pin "1") (pinfunction "1_1") (pintype "passive"))
    )
    (net (code "126") (name "Net-(E2-MS1{slash}SDI)") (class "Default")
      (node (ref "E2") (pin "2") (pinfunction "MS1/SDI_2") (pintype "passive"))
      (node (ref "E2_MS1") (pin "2") (pinfunction "2_2") (pintype "passive"))
      (node (ref "R44") (pin "1") (pinfunction "1_1") (pintype "passive"))
    )
    (net (code "127") (name "Net-(E2-MS2{slash}SCK)") (class "Default")
      (node (ref "E2") (pin "3") (pinfunction "MS2/SCK_3") (pintype "passive"))
      (node (ref "E2_MS2") (pin "2") (pinfunction "2_2") (pintype "passive"))
    )
    (net (code "128") (name "Net-(E2-MS3{slash}CS{slash}UART)") (class "Default")
      (node (ref "E2") (pin "4") (pinfunction "MS3/CS/UART_4") (pintype "passive"))
      (node (ref "E2_MS3") (pin "2") (pinfunction "2_2") (pintype "passive"))
    )
    (net (code "129") (name "Net-(E2-~{RST}{slash}SDO)") (class "Default")
      (node (ref "E2") (pin "5") (pinfunction "~{RST}/SDO_5") (pintype "passive"))
      (node (ref "E2_RST") (pin "2") (pinfunction "2_2") (pintype "passive"))
    )
    (net (code "130") (name "Net-(E2_DIAG-Pad1)") (class "Default")
      (node (ref "E2_DIAG") (pin "1") (pinfunction "1_1") (pintype "passive"))
      (node (ref "R77") (pin "1") (pinfunction "1_1") (pintype "passive"))
    )
    (net (code "131") (name "Net-(F1-Pad0)") (class "Default")
      (node (ref "F1") (pin "0") (pinfunction "0_0") (pintype "passive"))
      (node (ref "HB-PWR") (pin "2") (pinfunction "2_2") (pintype "power_in"))
    )
    (net (code "132") (name "Net-(F2-Pad1)") (class "Default")
      (node (ref "F2") (pin "1") (pinfunction "1_1") (pintype "passive"))
      (node (ref "MAIN-PWR") (pin "2") (pinfunction "2_2") (pintype "power_in"))
    )
    (net (code "133") (name "Net-(FAN0-4)") (class "Default")
      (node (ref "D10") (pin "K") (pinfunction "K_K") (pintype "passive"))
      (node (ref "FAN0") (pin "1") (pinfunction "4_1") (pintype "power_in"))
      (node (ref "FAN0_1") (pin "1") (pinfunction "1_1") (pintype "passive"))
      (node (ref "VFA0_sel") (pin "2") (pinfunction "2_2") (pintype "passive"))
    )
    (net (code "134") (name "Net-(FAN1-4)") (class "Default")
      (node (ref "D11") (pin "K") (pinfunction "K_K") (pintype "passive"))
      (node (ref "FAN1") (pin "1") (pinfunction "4_1") (pintype "power_in"))
      (node (ref "FAN1_1") (pin "1") (pinfunction "1_1") (pintype "passive"))
      (node (ref "VFA1_sel") (pin "2") (pinfunction "2_2") (pintype "passive"))
    )
    (net (code "135") (name "Net-(HB-OUT-4)") (class "Default")
      (node (ref "D13") (pin "A") (pinfunction "A_A") (pintype "passive"))
      (node (ref "HB-OUT") (pin "1") (pinfunction "4_1") (pintype "power_in"))
      (node (ref "Q6") (pin "2") (pinfunction "D_2") (pintype "passive"))
    )
    (net (code "136") (name "Net-(HE2-4)") (class "Default")
      (node (ref "D14") (pin "K") (pinfunction "K_K") (pintype "passive"))
      (node (ref "HE2") (pin "1") (pinfunction "4_1") (pintype "power_in"))
      (node (ref "VHE2_sel") (pin "2") (pinfunction "2_2") (pintype "passive"))
    )
    (net (code "137") (name "Net-(J2-SH)") (class "Default")
      (node (ref "FB2") (pin "1") (pinfunction "1_1") (pintype "passive"))
      (node (ref "J2") (pin "SHIELD") (pinfunction "SH_SHIELD") (pintype "passive"))
      (node (ref "USB_AUX") (pin "1") (pinfunction "1_1") (pintype "passive"))
    )
    (net (code "138") (name "Net-(LD1-A)") (class "Default")
      (node (ref "LD1") (pin "1") (pinfunction "A_1") (pintype "passive"))
      (node (ref "R4") (pin "1") (pinfunction "1_1") (pintype "passive"))
    )
    (net (code "139") (name "Net-(LD2-A)") (class "Default")
      (node (ref "LD2") (pin "1") (pinfunction "A_1") (pintype "passive"))
      (node (ref "R33") (pin "1") (pinfunction "1_1") (pintype "passive"))
    )
    (net (code "140") (name "Net-(LD3-A)") (class "Default")
      (node (ref "LD3") (pin "1") (pinfunction "A_1") (pintype "passive"))
      (node (ref "R36") (pin "1") (pinfunction "1_1") (pintype "passive"))
    )
    (net (code "141") (name "Net-(LD4-A)") (class "Default")
      (node (ref "LD4") (pin "1") (pinfunction "A_1") (pintype "passive"))
      (node (ref "R39") (pin "1") (pinfunction "1_1") (pintype "passive"))
    )
    (net (code "142") (name "Net-(LD5-A)") (class "Default")
      (node (ref "LD5") (pin "1") (pinfunction "A_1") (pintype "passive"))
      (node (ref "R50") (pin "1") (pinfunction "1_1") (pintype "passive"))
    )
    (net (code "143") (name "Net-(LD6-A)") (class "Default")
      (node (ref "LD6") (pin "1") (pinfunction "A_1") (pintype "passive"))
      (node (ref "R53") (pin "1") (pinfunction "1_1") (pintype "passive"))
    )
    (net (code "144") (name "Net-(LD7-A)") (class "Default")
      (node (ref "LD7") (pin "1") (pinfunction "A_1") (pintype "passive"))
      (node (ref "R55") (pin "1") (pinfunction "1_1") (pintype "passive"))
    )
    (net (code "145") (name "Net-(LD8-K)") (class "Default")
      (node (ref "LD8") (pin "2") (pinfunction "K_2") (pintype "passive"))
      (node (ref "R20") (pin "2") (pinfunction "2_2") (pintype "passive"))
    )
    (net (code "146") (name "Net-(LD9-K)") (class "Default")
      (node (ref "LD9") (pin "2") (pinfunction "K_2") (pintype "passive"))
      (node (ref "R58") (pin "2") (pinfunction "2_2") (pintype "passive"))
    )
    (net (code "147") (name "Net-(LD10-K)") (class "Default")
      (node (ref "LD10") (pin "2") (pinfunction "K_2") (pintype "passive"))
      (node (ref "R59") (pin "2") (pinfunction "2_2") (pintype "passive"))
    )
    (net (code "148") (name "Net-(LD11-K)") (class "Default")
      (node (ref "LD11") (pin "2") (pinfunction "K_2") (pintype "passive"))
      (node (ref "R15") (pin "2") (pinfunction "2_2") (pintype "passive"))
    )
    (net (code "149") (name "Net-(LED1-A)") (class "Default")
      (node (ref "LED1") (pin "1") (pinfunction "A_1") (pintype "passive"))
      (node (ref "R13") (pin "1") (pinfunction "1_1") (pintype "passive"))
    )
    (net (code "150") (name "Net-(Q1-D)") (class "Default")
      (node (ref "D12") (pin "A") (pinfunction "A_A") (pintype "passive"))
      (node (ref "HE0") (pin "2") (pinfunction "2_2") (pintype "power_in"))
      (node (ref "Q1") (pin "2") (pinfunction "D_2") (pintype "passive"))
    )
    (net (code "151") (name "Net-(Q1-G)") (class "Default")
      (node (ref "Q1") (pin "1") (pinfunction "G_1") (pintype "passive"))
      (node (ref "R34") (pin "2") (pinfunction "2_2") (pintype "passive"))
    )
    (net (code "152") (name "Net-(Q2-D)") (class "Default")
      (node (ref "D9") (pin "A") (pinfunction "A_A") (pintype "passive"))
      (node (ref "HE1") (pin "2") (pinfunction "2_2") (pintype "power_in"))
      (node (ref "Q2") (pin "2") (pinfunction "D_2") (pintype "passive"))
    )
    (net (code "153") (name "Net-(Q2-G)") (class "Default")
      (node (ref "Q2") (pin "1") (pinfunction "G_1") (pintype "passive"))
      (node (ref "R37") (pin "2") (pinfunction "2_2") (pintype "passive"))
    )
    (net (code "154") (name "Net-(Q3-D)") (class "Default")
      (node (ref "D14") (pin "A") (pinfunction "A_A") (pintype "passive"))
      (node (ref "HE2") (pin "2") (pinfunction "2_2") (pintype "power_in"))
      (node (ref "Q3") (pin "2") (pinfunction "D_2") (pintype "passive"))
    )
    (net (code "155") (name "Net-(Q3-G)") (class "Default")
      (node (ref "Q3") (pin "1") (pinfunction "G_1") (pintype "passive"))
      (node (ref "R48") (pin "2") (pinfunction "2_2") (pintype "passive"))
    )
    (net (code "156") (name "Net-(Q4-D)") (class "Default")
      (node (ref "D10") (pin "A") (pinfunction "A_A") (pintype "passive"))
      (node (ref "FAN0") (pin "2") (pinfunction "2_2") (pintype "power_in"))
      (node (ref "FAN0_1") (pin "2") (pinfunction "2_2") (pintype "passive"))
      (node (ref "Q4") (pin "2") (pinfunction "D_2") (pintype "passive"))
    )
    (net (code "157") (name "Net-(Q4-G)") (class "Default")
      (node (ref "Q4") (pin "1") (pinfunction "G_1") (pintype "passive"))
      (node (ref "R51") (pin "2") (pinfunction "2_2") (pintype "passive"))
    )
    (net (code "158") (name "Net-(Q5-D)") (class "Default")
      (node (ref "D11") (pin "A") (pinfunction "A_A") (pintype "passive"))
      (node (ref "FAN1") (pin "2") (pinfunction "2_2") (pintype "power_in"))
      (node (ref "FAN1_1") (pin "2") (pinfunction "2_2") (pintype "passive"))
      (node (ref "Q5") (pin "2") (pinfunction "D_2") (pintype "passive"))
    )
    (net (code "159") (name "Net-(Q5-G)") (class "Default")
      (node (ref "Q5") (pin "1") (pinfunction "G_1") (pintype "passive"))
      (node (ref "R46") (pin "2") (pinfunction "2_2") (pintype "passive"))
    )
    (net (code "160") (name "Net-(Q6-G)") (class "Default")
      (node (ref "Q6") (pin "1") (pinfunction "G_1") (pintype "passive"))
      (node (ref "U2") (pin "4") (pinfunction "Y_4") (pintype "passive"))
    )
    (net (code "161") (name "Net-(Q7-G)") (class "Default")
      (node (ref "D1") (pin "A") (pinfunction "A_A") (pintype "passive"))
      (node (ref "Q7") (pin "1") (pinfunction "G_1") (pintype "passive"))
      (node (ref "R80") (pin "1") (pinfunction "1_1") (pintype "passive"))
    )
    (net (code "162") (name "Net-(R17-Pad2)") (class "Default")
      (node (ref "R17") (pin "2") (pinfunction "2_2") (pintype "passive"))
      (node (ref "R60") (pin "1") (pinfunction "1_1") (pintype "passive"))
      (node (ref "X-") (pin "1") (pinfunction "1_1") (pintype "passive"))
    )
    (net (code "163") (name "Net-(R18-Pad1)") (class "Default")
      (node (ref "R18") (pin "1") (pinfunction "1_1") (pintype "passive"))
      (node (ref "X_DIAG") (pin "1") (pinfunction "1_1") (pintype "passive"))
    )
    (net (code "164") (name "Net-(R61-Pad2)") (class "Default")
      (node (ref "R61") (pin "2") (pinfunction "2_2") (pintype "passive"))
      (node (ref "R63") (pin "1") (pinfunction "1_1") (pintype "passive"))
      (node (ref "X+") (pin "1") (pinfunction "1_1") (pintype "passive"))
    )
    (net (code "165") (name "Net-(R67-Pad2)") (class "Default")
      (node (ref "R67") (pin "2") (pinfunction "2_2") (pintype "passive"))
      (node (ref "R69") (pin "1") (pinfunction "1_1") (pintype "passive"))
      (node (ref "Y-") (pin "1") (pinfunction "1_1") (pintype "passive"))
    )
    (net (code "166") (name "Net-(R68-Pad1)") (class "Default")
      (node (ref "R68") (pin "1") (pinfunction "1_1") (pintype "passive"))
      (node (ref "Y_DIAG") (pin "1") (pinfunction "1_1") (pintype "passive"))
    )
    (net (code "167") (name "Net-(R70-Pad2)") (class "Default")
      (node (ref "R70") (pin "2") (pinfunction "2_2") (pintype "passive"))
      (node (ref "R72") (pin "1") (pinfunction "1_1") (pintype "passive"))
      (node (ref "Y+") (pin "1") (pinfunction "1_1") (pintype "passive"))
    )
    (net (code "168") (name "Net-(R73-Pad2)") (class "Default")
      (node (ref "R73") (pin "2") (pinfunction "2_2") (pintype "passive"))
      (node (ref "R75") (pin "1") (pinfunction "1_1") (pintype "passive"))
      (node (ref "Z-") (pin "1") (pinfunction "1_1") (pintype "passive"))
    )
    (net (code "169") (name "Net-(R74-Pad1)") (class "Default")
      (node (ref "R74") (pin "1") (pinfunction "1_1") (pintype "passive"))
      (node (ref "Z_DIAG") (pin "1") (pinfunction "1_1") (pintype "passive"))
    )
    (net (code "170") (name "Net-(R76-Pad2)") (class "Default")
      (node (ref "R76") (pin "2") (pinfunction "2_2") (pintype "passive"))
      (node (ref "R78") (pin "1") (pinfunction "1_1") (pintype "passive"))
      (node (ref "Z+") (pin "1") (pinfunction "1_1") (pintype "passive"))
    )
    (net (code "171") (name "Net-(U1A-PB8)") (class "Default")
      (node (ref "R1") (pin "1") (pinfunction "1_1") (pintype "passive"))
      (node (ref "U1") (pin "95") (pinfunction "PB8_95") (pintype "bidirectional"))
    )
    (net (code "172") (name "Net-(U1A-PB9)") (class "Default")
      (node (ref "R9") (pin "1") (pinfunction "1_1") (pintype "passive"))
      (node (ref "U1") (pin "96") (pinfunction "PB9_96") (pintype "bidirectional"))
    )
    (net (code "173") (name "Net-(U1A-PH0-OSC_IN(PH0))") (class "Default")
      (node (ref "U1") (pin "12") (pinfunction "PH0-OSC_IN(PH0)_12") (pintype "bidirectional"))
      (node (ref "XT1") (pin "3") (pinfunction "OUT_3") (pintype "passive"))
    )
    (net (code "174") (name "Net-(U1A-PH1-OSC_OUT(PH1))") (class "Default")
      (node (ref "U1") (pin "13") (pinfunction "PH1-OSC_OUT(PH1)_13") (pintype "bidirectional"))
      (node (ref "XT1") (pin "1") (pinfunction "IN_1") (pintype "passive"))
    )
    (net (code "175") (name "Net-(U1A-VCAP_1)") (class "Default")
      (node (ref "C6") (pin "2") (pinfunction "2_2") (pintype "passive"))
      (node (ref "U1") (pin "48") (pinfunction "VCAP_1_48") (pintype "power_in"))
    )
    (net (code "176") (name "Net-(U1A-VCAP_2)") (class "Default")
      (node (ref "C5") (pin "2") (pinfunction "2_2") (pintype "passive"))
      (node (ref "U1") (pin "73") (pinfunction "VCAP_2_73") (pintype "power_in"))
    )
    (net (code "177") (name "Net-(U2-A)") (class "Default")
      (node (ref "R31") (pin "2") (pinfunction "2_2") (pintype "passive"))
      (node (ref "U2") (pin "2") (pinfunction "A_2") (pintype "passive"))
    )
    (net (code "178") (name "Net-(U3-BST)") (class "Default")
      (node (ref "C18") (pin "2") (pinfunction "2_2") (pintype "passive"))
      (node (ref "U3") (pin "6") (pinfunction "BST_6") (pintype "passive"))
    )
    (net (code "179") (name "Net-(U3-SW)") (class "Default")
      (node (ref "C18") (pin "1") (pinfunction "1_1") (pintype "passive"))
      (node (ref "L1") (pin "1") (pinfunction "1_1") (pintype "passive"))
      (node (ref "U3") (pin "5") (pinfunction "SW_5") (pintype "passive"))
    )
    (net (code "180") (name "Net-(U4-BST)") (class "Default")
      (node (ref "C33") (pin "1") (pinfunction "1_1") (pintype "passive"))
      (node (ref "U4") (pin "2") (pinfunction "BST_2") (pintype "passive"))
    )
    (net (code "181") (name "Net-(U4-COMP)") (class "Default")
      (node (ref "R19") (pin "2") (pinfunction "2_2") (pintype "passive"))
      (node (ref "U4") (pin "5") (pinfunction "COMP_5") (pintype "passive"))
    )
    (net (code "182") (name "Net-(U4-EN)") (class "Default")
      (node (ref "R79") (pin "1") (pinfunction "1_1") (pintype "passive"))
      (node (ref "U4") (pin "8") (pinfunction "EN_8") (pintype "passive"))
    )
    (net (code "183") (name "Net-(U4-FB)") (class "Default")
      (node (ref "R56") (pin "2") (pinfunction "2_2") (pintype "passive"))
      (node (ref "R57") (pin "2") (pinfunction "2_2") (pintype "passive"))
      (node (ref "U4") (pin "6") (pinfunction "FB_6") (pintype "passive"))
    )
    (net (code "184") (name "Net-(U4-FSW)") (class "Default")
      (node (ref "R10") (pin "2") (pinfunction "2_2") (pintype "passive"))
      (node (ref "U4") (pin "4") (pinfunction "FSW_4") (pintype "passive"))
    )
    (net (code "185") (name "Net-(U4-LX)") (class "Default")
      (node (ref "C33") (pin "2") (pinfunction "2_2") (pintype "passive"))
      (node (ref "D8") (pin "K") (pinfunction "K_K") (pintype "passive"))
      (node (ref "L2") (pin "1") (pinfunction "1_1") (pintype "passive"))
      (node (ref "U4") (pin "1") (pinfunction "LX_1") (pintype "passive"))
    )
    (net (code "186") (name "Net-(U4-SS)") (class "Default")
      (node (ref "C34") (pin "2") (pinfunction "2_2") (pintype "passive"))
      (node (ref "U4") (pin "7") (pinfunction "SS_7") (pintype "passive"))
    )
    (net (code "187") (name "Net-(X-1A)") (class "Default")
      (node (ref "X") (pin "12") (pinfunction "1A_12") (pintype "passive"))
      (node (ref "X_MOT") (pin "2") (pinfunction "2_2") (pintype "passive"))
      (node (ref "X_MOT_A") (pin "3") (pinfunction "3_3") (pintype "passive"))
    )
    (net (code "188") (name "Net-(X-1B)") (class "Default")
      (node (ref "X") (pin "11") (pinfunction "1B_11") (pintype "passive"))
      (node (ref "X_MOT") (pin "1") (pinfunction "1_1") (pintype "passive"))
      (node (ref "X_MOT_A") (pin "4") (pinfunction "4_4") (pintype "passive"))
    )
    (net (code "189") (name "Net-(X-2A)") (class "Default")
      (node (ref "X") (pin "13") (pinfunction "2A_13") (pintype "passive"))
      (node (ref "X_MOT") (pin "3") (pinfunction "3_3") (pintype "passive"))
      (node (ref "X_MOT_A") (pin "2") (pinfunction "2_2") (pintype "passive"))
    )
    (net (code "190") (name "Net-(X-2B)") (class "Default")
      (node (ref "X") (pin "14") (pinfunction "2B_14") (pintype "passive"))
      (node (ref "X_MOT") (pin "4") (pinfunction "4_4") (pintype "passive"))
      (node (ref "X_MOT_A") (pin "1") (pinfunction "1_1") (pintype "passive"))
    )
    (net (code "191") (name "Net-(X-MS1{slash}SDI)") (class "Default")
      (node (ref "R22") (pin "1") (pinfunction "1_1") (pintype "passive"))
      (node (ref "X") (pin "2") (pinfunction "MS1/SDI_2") (pintype "passive"))
      (node (ref "X_MS1") (pin "2") (pinfunction "2_2") (pintype "passive"))
    )
    (net (code "192") (name "Net-(X-MS2{slash}SCK)") (class "Default")
      (node (ref "X") (pin "3") (pinfunction "MS2/SCK_3") (pintype "passive"))
      (node (ref "X_MS2") (pin "2") (pinfunction "2_2") (pintype "passive"))
    )
    (net (code "193") (name "Net-(X-MS3{slash}CS{slash}UART)") (class "Default")
      (node (ref "X") (pin "4") (pinfunction "MS3/CS/UART_4") (pintype "passive"))
      (node (ref "X_MS3") (pin "2") (pinfunction "2_2") (pintype "passive"))
    )
    (net (code "194") (name "Net-(X-~{RST}{slash}SDO)") (class "Default")
      (node (ref "X") (pin "5") (pinfunction "~{RST}/SDO_5") (pintype "passive"))
      (node (ref "X_RST") (pin "2") (pinfunction "2_2") (pintype "passive"))
    )
    (net (code "195") (name "Net-(Y-1A)") (class "Default")
      (node (ref "Y") (pin "12") (pinfunction "1A_12") (pintype "passive"))
      (node (ref "Y_MOT") (pin "2") (pinfunction "2_2") (pintype "passive"))
      (node (ref "Y_MOT_A") (pin "3") (pinfunction "3_3") (pintype "passive"))
    )
    (net (code "196") (name "Net-(Y-1B)") (class "Default")
      (node (ref "Y") (pin "11") (pinfunction "1B_11") (pintype "passive"))
      (node (ref "Y_MOT") (pin "1") (pinfunction "1_1") (pintype "passive"))
      (node (ref "Y_MOT_A") (pin "4") (pinfunction "4_4") (pintype "passive"))
    )
    (net (code "197") (name "Net-(Y-2A)") (class "Default")
      (node (ref "Y") (pin "13") (pinfunction "2A_13") (pintype "passive"))
      (node (ref "Y_MOT") (pin "3") (pinfunction "3_3") (pintype "passive"))
      (node (ref "Y_MOT_A") (pin "2") (pinfunction "2_2") (pintype "passive"))
    )
    (net (code "198") (name "Net-(Y-2B)") (class "Default")
      (node (ref "Y") (pin "14") (pinfunction "2B_14") (pintype "passive"))
      (node (ref "Y_MOT") (pin "4") (pinfunction "4_4") (pintype "passive"))
      (node (ref "Y_MOT_A") (pin "1") (pinfunction "1_1") (pintype "passive"))
    )
    (net (code "199") (name "Net-(Y-MS1{slash}SDI)") (class "Default")
      (node (ref "R24") (pin "1") (pinfunction "1_1") (pintype "passive"))
      (node (ref "Y") (pin "2") (pinfunction "MS1/SDI_2") (pintype "passive"))
      (node (ref "Y_MS1") (pin "2") (pinfunction "2_2") (pintype "passive"))
    )
    (net (code "200") (name "Net-(Y-MS2{slash}SCK)") (class "Default")
      (node (ref "Y") (pin "3") (pinfunction "MS2/SCK_3") (pintype "passive"))
      (node (ref "Y_MS2") (pin "2") (pinfunction "2_2") (pintype "passive"))
    )
    (net (code "201") (name "Net-(Y-MS3{slash}CS{slash}UART)") (class "Default")
      (node (ref "Y") (pin "4") (pinfunction "MS3/CS/UART_4") (pintype "passive"))
      (node (ref "Y_MS3") (pin "2") (pinfunction "2_2") (pintype "passive"))
    )
    (net (code "202") (name "Net-(Y-~{RST}{slash}SDO)") (class "Default")
      (node (ref "Y") (pin "5") (pinfunction "~{RST}/SDO_5") (pintype "passive"))
      (node (ref "Y_RST") (pin "2") (pinfunction "2_2") (pintype "passive"))
    )
    (net (code "203") (name "Net-(Z-1A)") (class "Default")
      (node (ref "Z") (pin "12") (pinfunction "1A_12") (pintype "passive"))
      (node (ref "Z_MOT") (pin "2") (pinfunction "2_2") (pintype "passive"))
      (node (ref "Z_MOT_A") (pin "3") (pinfunction "3_3") (pintype "passive"))
    )
    (net (code "204") (name "Net-(Z-1B)") (class "Default")
      (node (ref "Z") (pin "11") (pinfunction "1B_11") (pintype "passive"))
      (node (ref "Z_MOT") (pin "1") (pinfunction "1_1") (pintype "passive"))
      (node (ref "Z_MOT_A") (pin "4") (pinfunction "4_4") (pintype "passive"))
    )
    (net (code "205") (name "Net-(Z-2A)") (class "Default")
      (node (ref "Z") (pin "13") (pinfunction "2A_13") (pintype "passive"))
      (node (ref "Z_MOT") (pin "3") (pinfunction "3_3") (pintype "passive"))
      (node (ref "Z_MOT_A") (pin "2") (pinfunction "2_2") (pintype "passive"))
    )
    (net (code "206") (name "Net-(Z-2B)") (class "Default")
      (node (ref "Z") (pin "14") (pinfunction "2B_14") (pintype "passive"))
      (node (ref "Z_MOT") (pin "4") (pinfunction "4_4") (pintype "passive"))
      (node (ref "Z_MOT_A") (pin "1") (pinfunction "1_1") (pintype "passive"))
    )
    (net (code "207") (name "Net-(Z-MS1{slash}SDI)") (class "Default")
      (node (ref "R26") (pin "1") (pinfunction "1_1") (pintype "passive"))
      (node (ref "Z") (pin "2") (pinfunction "MS1/SDI_2") (pintype "passive"))
      (node (ref "Z_MS1") (pin "2") (pinfunction "2_2") (pintype "passive"))
    )
    (net (code "208") (name "Net-(Z-MS2{slash}SCK)") (class "Default")
      (node (ref "Z") (pin "3") (pinfunction "MS2/SCK_3") (pintype "passive"))
      (node (ref "Z_MS2") (pin "2") (pinfunction "2_2") (pintype "passive"))
    )
    (net (code "209") (name "Net-(Z-MS3{slash}CS{slash}UART)") (class "Default")
      (node (ref "Z") (pin "4") (pinfunction "MS3/CS/UART_4") (pintype "passive"))
      (node (ref "Z_MS3") (pin "2") (pinfunction "2_2") (pintype "passive"))
    )
    (net (code "210") (name "Net-(Z-~{RST}{slash}SDO)") (class "Default")
      (node (ref "Z") (pin "5") (pinfunction "~{RST}/SDO_5") (pintype "passive"))
      (node (ref "Z_RST") (pin "2") (pinfunction "2_2") (pintype "passive"))
    )
    (net (code "211") (name "USBVCC") (class "Default")
      (node (ref "C11") (pin "2") (pinfunction "2_2") (pintype "passive"))
      (node (ref "F3") (pin "1") (pinfunction "1_1") (pintype "passive"))
      (node (ref "J2") (pin "VBUS") (pinfunction "VBUS_VBUS") (pintype "passive"))
      (node (ref "R4") (pin "2") (pinfunction "2_2") (pintype "passive"))
      (node (ref "U5") (pin "5") (pinfunction "VBUS_5") (pintype "passive"))
      (node (ref "USB_AUX") (pin "5") (pinfunction "5_5") (pintype "passive"))
    )
    (net (code "212") (name "VIN1") (class "Default")
      (node (ref "C17") (pin "2") (pinfunction "2_2") (pintype "passive"))
      (node (ref "C37") (pin "2") (pinfunction "2_2") (pintype "passive"))
      (node (ref "D12") (pin "K") (pinfunction "K_K") (pintype "passive"))
      (node (ref "D6") (pin "K") (pinfunction "K_K") (pintype "passive"))
      (node (ref "D9") (pin "K") (pinfunction "K_K") (pintype "passive"))
      (node (ref "F2") (pin "0") (pinfunction "0_0") (pintype "passive"))
      (node (ref "HE0") (pin "1") (pinfunction "4_1") (pintype "power_in"))
      (node (ref "HE1") (pin "1") (pinfunction "4_1") (pintype "power_in"))
      (node (ref "PWR") (pin "1") (pinfunction "1_1") (pintype "passive"))
      (node (ref "Q7") (pin "3") (pinfunction "D_3") (pintype "passive"))
      (node (ref "U3") (pin "2") (pinfunction "EN_2") (pintype "passive"))
      (node (ref "U3") (pin "3") (pinfunction "VIN_3") (pintype "passive"))
      (node (ref "U4") (pin "9") (pinfunction "VIN_9") (pintype "passive"))
      (node (ref "VFA0_sel") (pin "1") (pinfunction "1_1") (pintype "passive"))
      (node (ref "VFA1_sel") (pin "1") (pinfunction "1_1") (pintype "passive"))
      (node (ref "VHE2_sel") (pin "1") (pinfunction "1_1") (pintype "passive"))
    )
    (net (code "213") (name "VIN2") (class "Default")
      (node (ref "D13") (pin "K") (pinfunction "K_K") (pintype "passive"))
      (node (ref "D7") (pin "K") (pinfunction "K_K") (pintype "passive"))
      (node (ref "F1") (pin "1") (pinfunction "1_1") (pintype "passive"))
      (node (ref "HB-OUT") (pin "2") (pinfunction "2_2") (pintype "power_in"))
    )
    (net (code "214") (name "VMOT") (class "Default")
      (node (ref "C21") (pin "1") (pinfunction "1_1") (pintype "passive"))
      (node (ref "C22") (pin "1") (pinfunction "1_1") (pintype "passive"))
      (node (ref "C23") (pin "1") (pinfunction "1_1") (pintype "passive"))
      (node (ref "C24") (pin "1") (pinfunction "1_1") (pintype "passive"))
      (node (ref "C25") (pin "1") (pinfunction "1_1") (pintype "passive"))
      (node (ref "C30") (pin "1") (pinfunction "1_1") (pintype "passive"))
      (node (ref "D1") (pin "K") (pinfunction "K_K") (pintype "passive"))
      (node (ref "D3") (pin "K") (pinfunction "K_K") (pintype "passive"))
      (node (ref "E0") (pin "16") (pinfunction "VMOT_16") (pintype "passive"))
      (node (ref "E1") (pin "16") (pinfunction "VMOT_16") (pintype "passive"))
      (node (ref "E2") (pin "16") (pinfunction "VMOT_16") (pintype "passive"))
      (node (ref "Q7") (pin "2") (pinfunction "S_2") (pintype "passive"))
      (node (ref "X") (pin "16") (pinfunction "VMOT_16") (pintype "passive"))
      (node (ref "Y") (pin "16") (pinfunction "VMOT_16") (pintype "passive"))
      (node (ref "Z") (pin "16") (pinfunction "VMOT_16") (pintype "passive"))
    )
    (net (code "215") (name "unconnected-(E0_0-Pad1)") (class "Default")
      (node (ref "E0_0") (pin "1") (pinfunction "1_1") (pintype "passive"))
    )
    (net (code "216") (name "unconnected-(E0_0-Pad2)") (class "Default")
      (node (ref "E0_0") (pin "2") (pinfunction "2_2") (pintype "passive"))
    )
    (net (code "217") (name "unconnected-(E0_0-Pad3)") (class "Default")
      (node (ref "E0_0") (pin "3") (pinfunction "3_3") (pintype "passive"))
    )
    (net (code "218") (name "unconnected-(E0_0-Pad4)") (class "Default")
      (node (ref "E0_0") (pin "4") (pinfunction "4_4") (pintype "passive"))
    )
    (net (code "219") (name "unconnected-(E0_0-Pad5)") (class "Default")
      (node (ref "E0_0") (pin "5") (pinfunction "5_5") (pintype "passive"))
    )
    (net (code "220") (name "unconnected-(E0_0-Pad6)") (class "Default")
      (node (ref "E0_0") (pin "6") (pinfunction "6_6") (pintype "passive"))
    )
    (net (code "221") (name "unconnected-(E0_0-Pad7)") (class "Default")
      (node (ref "E0_0") (pin "7") (pinfunction "7_7") (pintype "passive"))
    )
    (net (code "222") (name "unconnected-(E0_0-Pad8)") (class "Default")
      (node (ref "E0_0") (pin "8") (pinfunction "8_8") (pintype "passive"))
    )
    (net (code "223") (name "unconnected-(E0_1-Pad1)") (class "Default")
      (node (ref "E0_1") (pin "1") (pinfunction "1_1") (pintype "passive"))
    )
    (net (code "224") (name "unconnected-(E0_1-Pad2)") (class "Default")
      (node (ref "E0_1") (pin "2") (pinfunction "2_2") (pintype "passive"))
    )
    (net (code "225") (name "unconnected-(E0_1-Pad3)") (class "Default")
      (node (ref "E0_1") (pin "3") (pinfunction "3_3") (pintype "passive"))
    )
    (net (code "226") (name "unconnected-(E0_1-Pad4)") (class "Default")
      (node (ref "E0_1") (pin "4") (pinfunction "4_4") (pintype "passive"))
    )
    (net (code "227") (name "unconnected-(E0_1-Pad5)") (class "Default")
      (node (ref "E0_1") (pin "5") (pinfunction "5_5") (pintype "passive"))
    )
    (net (code "228") (name "unconnected-(E0_1-Pad6)") (class "Default")
      (node (ref "E0_1") (pin "6") (pinfunction "6_6") (pintype "passive"))
    )
    (net (code "229") (name "unconnected-(E0_1-Pad7)") (class "Default")
      (node (ref "E0_1") (pin "7") (pinfunction "7_7") (pintype "passive"))
    )
    (net (code "230") (name "unconnected-(E0_1-Pad8)") (class "Default")
      (node (ref "E0_1") (pin "8") (pinfunction "8_8") (pintype "passive"))
    )
    (net (code "231") (name "unconnected-(E0_DIAG-Pad2)") (class "Default")
      (node (ref "E0_DIAG") (pin "2") (pinfunction "2_2") (pintype "passive"))
    )
    (net (code "232") (name "unconnected-(E1_0-Pad1)") (class "Default")
      (node (ref "E1_0") (pin "1") (pinfunction "1_1") (pintype "passive"))
    )
    (net (code "233") (name "unconnected-(E1_0-Pad2)") (class "Default")
      (node (ref "E1_0") (pin "2") (pinfunction "2_2") (pintype "passive"))
    )
    (net (code "234") (name "unconnected-(E1_0-Pad3)") (class "Default")
      (node (ref "E1_0") (pin "3") (pinfunction "3_3") (pintype "passive"))
    )
    (net (code "235") (name "unconnected-(E1_0-Pad4)") (class "Default")
      (node (ref "E1_0") (pin "4") (pinfunction "4_4") (pintype "passive"))
    )
    (net (code "236") (name "unconnected-(E1_0-Pad5)") (class "Default")
      (node (ref "E1_0") (pin "5") (pinfunction "5_5") (pintype "passive"))
    )
    (net (code "237") (name "unconnected-(E1_0-Pad6)") (class "Default")
      (node (ref "E1_0") (pin "6") (pinfunction "6_6") (pintype "passive"))
    )
    (net (code "238") (name "unconnected-(E1_0-Pad7)") (class "Default")
      (node (ref "E1_0") (pin "7") (pinfunction "7_7") (pintype "passive"))
    )
    (net (code "239") (name "unconnected-(E1_0-Pad8)") (class "Default")
      (node (ref "E1_0") (pin "8") (pinfunction "8_8") (pintype "passive"))
    )
    (net (code "240") (name "unconnected-(E1_1-Pad1)") (class "Default")
      (node (ref "E1_1") (pin "1") (pinfunction "1_1") (pintype "passive"))
    )
    (net (code "241") (name "unconnected-(E1_1-Pad2)") (class "Default")
      (node (ref "E1_1") (pin "2") (pinfunction "2_2") (pintype "passive"))
    )
    (net (code "242") (name "unconnected-(E1_1-Pad3)") (class "Default")
      (node (ref "E1_1") (pin "3") (pinfunction "3_3") (pintype "passive"))
    )
    (net (code "243") (name "unconnected-(E1_1-Pad4)") (class "Default")
      (node (ref "E1_1") (pin "4") (pinfunction "4_4") (pintype "passive"))
    )
    (net (code "244") (name "unconnected-(E1_1-Pad5)") (class "Default")
      (node (ref "E1_1") (pin "5") (pinfunction "5_5") (pintype "passive"))
    )
    (net (code "245") (name "unconnected-(E1_1-Pad6)") (class "Default")
      (node (ref "E1_1") (pin "6") (pinfunction "6_6") (pintype "passive"))
    )
    (net (code "246") (name "unconnected-(E1_1-Pad7)") (class "Default")
      (node (ref "E1_1") (pin "7") (pinfunction "7_7") (pintype "passive"))
    )
    (net (code "247") (name "unconnected-(E1_1-Pad8)") (class "Default")
      (node (ref "E1_1") (pin "8") (pinfunction "8_8") (pintype "passive"))
    )
    (net (code "248") (name "unconnected-(E1_DIAG-Pad2)") (class "Default")
      (node (ref "E1_DIAG") (pin "2") (pinfunction "2_2") (pintype "passive"))
    )
    (net (code "249") (name "unconnected-(E2_0-Pad1)") (class "Default")
      (node (ref "E2_0") (pin "1") (pinfunction "1_1") (pintype "passive"))
    )
    (net (code "250") (name "unconnected-(E2_0-Pad2)") (class "Default")
      (node (ref "E2_0") (pin "2") (pinfunction "2_2") (pintype "passive"))
    )
    (net (code "251") (name "unconnected-(E2_0-Pad3)") (class "Default")
      (node (ref "E2_0") (pin "3") (pinfunction "3_3") (pintype "passive"))
    )
    (net (code "252") (name "unconnected-(E2_0-Pad4)") (class "Default")
      (node (ref "E2_0") (pin "4") (pinfunction "4_4") (pintype "passive"))
    )
    (net (code "253") (name "unconnected-(E2_0-Pad5)") (class "Default")
      (node (ref "E2_0") (pin "5") (pinfunction "5_5") (pintype "passive"))
    )
    (net (code "254") (name "unconnected-(E2_0-Pad6)") (class "Default")
      (node (ref "E2_0") (pin "6") (pinfunction "6_6") (pintype "passive"))
    )
    (net (code "255") (name "unconnected-(E2_0-Pad7)") (class "Default")
      (node (ref "E2_0") (pin "7") (pinfunction "7_7") (pintype "passive"))
    )
    (net (code "256") (name "unconnected-(E2_0-Pad8)") (class "Default")
      (node (ref "E2_0") (pin "8") (pinfunction "8_8") (pintype "passive"))
    )
    (net (code "257") (name "unconnected-(E2_1-Pad1)") (class "Default")
      (node (ref "E2_1") (pin "1") (pinfunction "1_1") (pintype "passive"))
    )
    (net (code "258") (name "unconnected-(E2_1-Pad2)") (class "Default")
      (node (ref "E2_1") (pin "2") (pinfunction "2_2") (pintype "passive"))
    )
    (net (code "259") (name "unconnected-(E2_1-Pad3)") (class "Default")
      (node (ref "E2_1") (pin "3") (pinfunction "3_3") (pintype "passive"))
    )
    (net (code "260") (name "unconnected-(E2_1-Pad4)") (class "Default")
      (node (ref "E2_1") (pin "4") (pinfunction "4_4") (pintype "passive"))
    )
    (net (code "261") (name "unconnected-(E2_1-Pad5)") (class "Default")
      (node (ref "E2_1") (pin "5") (pinfunction "5_5") (pintype "passive"))
    )
    (net (code "262") (name "unconnected-(E2_1-Pad6)") (class "Default")
      (node (ref "E2_1") (pin "6") (pinfunction "6_6") (pintype "passive"))
    )
    (net (code "263") (name "unconnected-(E2_1-Pad7)") (class "Default")
      (node (ref "E2_1") (pin "7") (pinfunction "7_7") (pintype "passive"))
    )
    (net (code "264") (name "unconnected-(E2_1-Pad8)") (class "Default")
      (node (ref "E2_1") (pin "8") (pinfunction "8_8") (pintype "passive"))
    )
    (net (code "265") (name "unconnected-(E2_DIAG-Pad2)") (class "Default")
      (node (ref "E2_DIAG") (pin "2") (pinfunction "2_2") (pintype "passive"))
    )
    (net (code "266") (name "unconnected-(J2-PadID)") (class "Default")
      (node (ref "J2") (pin "ID") (pinfunction "ID_ID") (pintype "passive+no_connect"))
    )
    (net (code "267") (name "unconnected-(U1A-PC10-Pad78)") (class "Default")
      (node (ref "U1") (pin "78") (pinfunction "PC10_78") (pintype "bidirectional+no_connect"))
    )
    (net (code "268") (name "unconnected-(U5-IO3-Pad4)") (class "Default")
      (node (ref "U5") (pin "4") (pinfunction "IO3_4") (pintype "passive+no_connect"))
    )
    (net (code "269") (name "unconnected-(U5-IO4-Pad6)") (class "Default")
      (node (ref "U5") (pin "6") (pinfunction "IO4_6") (pintype "passive+no_connect"))
    )
    (net (code "270") (name "unconnected-(X_0-Pad1)") (class "Default")
      (node (ref "X_0") (pin "1") (pinfunction "1_1") (pintype "passive"))
    )
    (net (code "271") (name "unconnected-(X_0-Pad2)") (class "Default")
      (node (ref "X_0") (pin "2") (pinfunction "2_2") (pintype "passive"))
    )
    (net (code "272") (name "unconnected-(X_0-Pad3)") (class "Default")
      (node (ref "X_0") (pin "3") (pinfunction "3_3") (pintype "passive"))
    )
    (net (code "273") (name "unconnected-(X_0-Pad4)") (class "Default")
      (node (ref "X_0") (pin "4") (pinfunction "4_4") (pintype "passive"))
    )
    (net (code "274") (name "unconnected-(X_0-Pad5)") (class "Default")
      (node (ref "X_0") (pin "5") (pinfunction "5_5") (pintype "passive"))
    )
    (net (code "275") (name "unconnected-(X_0-Pad6)") (class "Default")
      (node (ref "X_0") (pin "6") (pinfunction "6_6") (pintype "passive"))
    )
    (net (code "276") (name "unconnected-(X_0-Pad7)") (class "Default")
      (node (ref "X_0") (pin "7") (pinfunction "7_7") (pintype "passive"))
    )
    (net (code "277") (name "unconnected-(X_0-Pad8)") (class "Default")
      (node (ref "X_0") (pin "8") (pinfunction "8_8") (pintype "passive"))
    )
    (net (code "278") (name "unconnected-(X_1-Pad1)") (class "Default")
      (node (ref "X_1") (pin "1") (pinfunction "1_1") (pintype "passive"))
    )
    (net (code "279") (name "unconnected-(X_1-Pad2)") (class "Default")
      (node (ref "X_1") (pin "2") (pinfunction "2_2") (pintype "passive"))
    )
    (net (code "280") (name "unconnected-(X_1-Pad3)") (class "Default")
      (node (ref "X_1") (pin "3") (pinfunction "3_3") (pintype "passive"))
    )
    (net (code "281") (name "unconnected-(X_1-Pad4)") (class "Default")
      (node (ref "X_1") (pin "4") (pinfunction "4_4") (pintype "passive"))
    )
    (net (code "282") (name "unconnected-(X_1-Pad5)") (class "Default")
      (node (ref "X_1") (pin "5") (pinfunction "5_5") (pintype "passive"))
    )
    (net (code "283") (name "unconnected-(X_1-Pad6)") (class "Default")
      (node (ref "X_1") (pin "6") (pinfunction "6_6") (pintype "passive"))
    )
    (net (code "284") (name "unconnected-(X_1-Pad7)") (class "Default")
      (node (ref "X_1") (pin "7") (pinfunction "7_7") (pintype "passive"))
    )
    (net (code "285") (name "unconnected-(X_1-Pad8)") (class "Default")
      (node (ref "X_1") (pin "8") (pinfunction "8_8") (pintype "passive"))
    )
    (net (code "286") (name "unconnected-(X_DIAG-Pad2)") (class "Default")
      (node (ref "X_DIAG") (pin "2") (pinfunction "2_2") (pintype "passive"))
    )
    (net (code "287") (name "unconnected-(Y_0-Pad1)") (class "Default")
      (node (ref "Y_0") (pin "1") (pinfunction "1_1") (pintype "passive"))
    )
    (net (code "288") (name "unconnected-(Y_0-Pad2)") (class "Default")
      (node (ref "Y_0") (pin "2") (pinfunction "2_2") (pintype "passive"))
    )
    (net (code "289") (name "unconnected-(Y_0-Pad3)") (class "Default")
      (node (ref "Y_0") (pin "3") (pinfunction "3_3") (pintype "passive"))
    )
    (net (code "290") (name "unconnected-(Y_0-Pad4)") (class "Default")
      (node (ref "Y_0") (pin "4") (pinfunction "4_4") (pintype "passive"))
    )
    (net (code "291") (name "unconnected-(Y_0-Pad5)") (class "Default")
      (node (ref "Y_0") (pin "5") (pinfunction "5_5") (pintype "passive"))
    )
    (net (code "292") (name "unconnected-(Y_0-Pad6)") (class "Default")
      (node (ref "Y_0") (pin "6") (pinfunction "6_6") (pintype "passive"))
    )
    (net (code "293") (name "unconnected-(Y_0-Pad7)") (class "Default")
      (node (ref "Y_0") (pin "7") (pinfunction "7_7") (pintype "passive"))
    )
    (net (code "294") (name "unconnected-(Y_0-Pad8)") (class "Default")
      (node (ref "Y_0") (pin "8") (pinfunction "8_8") (pintype "passive"))
    )
    (net (code "295") (name "unconnected-(Y_1-Pad1)") (class "Default")
      (node (ref "Y_1") (pin "1") (pinfunction "1_1") (pintype "passive"))
    )
    (net (code "296") (name "unconnected-(Y_1-Pad2)") (class "Default")
      (node (ref "Y_1") (pin "2") (pinfunction "2_2") (pintype "passive"))
    )
    (net (code "297") (name "unconnected-(Y_1-Pad3)") (class "Default")
      (node (ref "Y_1") (pin "3") (pinfunction "3_3") (pintype "passive"))
    )
    (net (code "298") (name "unconnected-(Y_1-Pad4)") (class "Default")
      (node (ref "Y_1") (pin "4") (pinfunction "4_4") (pintype "passive"))
    )
    (net (code "299") (name "unconnected-(Y_1-Pad5)") (class "Default")
      (node (ref "Y_1") (pin "5") (pinfunction "5_5") (pintype "passive"))
    )
    (net (code "300") (name "unconnected-(Y_1-Pad6)") (class "Default")
      (node (ref "Y_1") (pin "6") (pinfunction "6_6") (pintype "passive"))
    )
    (net (code "301") (name "unconnected-(Y_1-Pad7)") (class "Default")
      (node (ref "Y_1") (pin "7") (pinfunction "7_7") (pintype "passive"))
    )
    (net (code "302") (name "unconnected-(Y_1-Pad8)") (class "Default")
      (node (ref "Y_1") (pin "8") (pinfunction "8_8") (pintype "passive"))
    )
    (net (code "303") (name "unconnected-(Y_DIAG-Pad2)") (class "Default")
      (node (ref "Y_DIAG") (pin "2") (pinfunction "2_2") (pintype "passive"))
    )
    (net (code "304") (name "unconnected-(Z_0-Pad1)") (class "Default")
      (node (ref "Z_0") (pin "1") (pinfunction "1_1") (pintype "passive"))
    )
    (net (code "305") (name "unconnected-(Z_0-Pad2)") (class "Default")
      (node (ref "Z_0") (pin "2") (pinfunction "2_2") (pintype "passive"))
    )
    (net (code "306") (name "unconnected-(Z_0-Pad3)") (class "Default")
      (node (ref "Z_0") (pin "3") (pinfunction "3_3") (pintype "passive"))
    )
    (net (code "307") (name "unconnected-(Z_0-Pad4)") (class "Default")
      (node (ref "Z_0") (pin "4") (pinfunction "4_4") (pintype "passive"))
    )
    (net (code "308") (name "unconnected-(Z_0-Pad5)") (class "Default")
      (node (ref "Z_0") (pin "5") (pinfunction "5_5") (pintype "passive"))
    )
    (net (code "309") (name "unconnected-(Z_0-Pad6)") (class "Default")
      (node (ref "Z_0") (pin "6") (pinfunction "6_6") (pintype "passive"))
    )
    (net (code "310") (name "unconnected-(Z_0-Pad7)") (class "Default")
      (node (ref "Z_0") (pin "7") (pinfunction "7_7") (pintype "passive"))
    )
    (net (code "311") (name "unconnected-(Z_0-Pad8)") (class "Default")
      (node (ref "Z_0") (pin "8") (pinfunction "8_8") (pintype "passive"))
    )
    (net (code "312") (name "unconnected-(Z_1-Pad1)") (class "Default")
      (node (ref "Z_1") (pin "1") (pinfunction "1_1") (pintype "passive"))
    )
    (net (code "313") (name "unconnected-(Z_1-Pad2)") (class "Default")
      (node (ref "Z_1") (pin "2") (pinfunction "2_2") (pintype "passive"))
    )
    (net (code "314") (name "unconnected-(Z_1-Pad3)") (class "Default")
      (node (ref "Z_1") (pin "3") (pinfunction "3_3") (pintype "passive"))
    )
    (net (code "315") (name "unconnected-(Z_1-Pad4)") (class "Default")
      (node (ref "Z_1") (pin "4") (pinfunction "4_4") (pintype "passive"))
    )
    (net (code "316") (name "unconnected-(Z_1-Pad5)") (class "Default")
      (node (ref "Z_1") (pin "5") (pinfunction "5_5") (pintype "passive"))
    )
    (net (code "317") (name "unconnected-(Z_1-Pad6)") (class "Default")
      (node (ref "Z_1") (pin "6") (pinfunction "6_6") (pintype "passive"))
    )
    (net (code "318") (name "unconnected-(Z_1-Pad7)") (class "Default")
      (node (ref "Z_1") (pin "7") (pinfunction "7_7") (pintype "passive"))
    )
    (net (code "319") (name "unconnected-(Z_1-Pad8)") (class "Default")
      (node (ref "Z_1") (pin "8") (pinfunction "8_8") (pintype "passive"))
    )
    (net (code "320") (name "unconnected-(Z_DIAG-Pad2)") (class "Default")
      (node (ref "Z_DIAG") (pin "2") (pinfunction "2_2") (pintype "passive"))
    )
  )
)
